# PinHeck.net
KiCad netlist of a schematic drawn in EAGLE
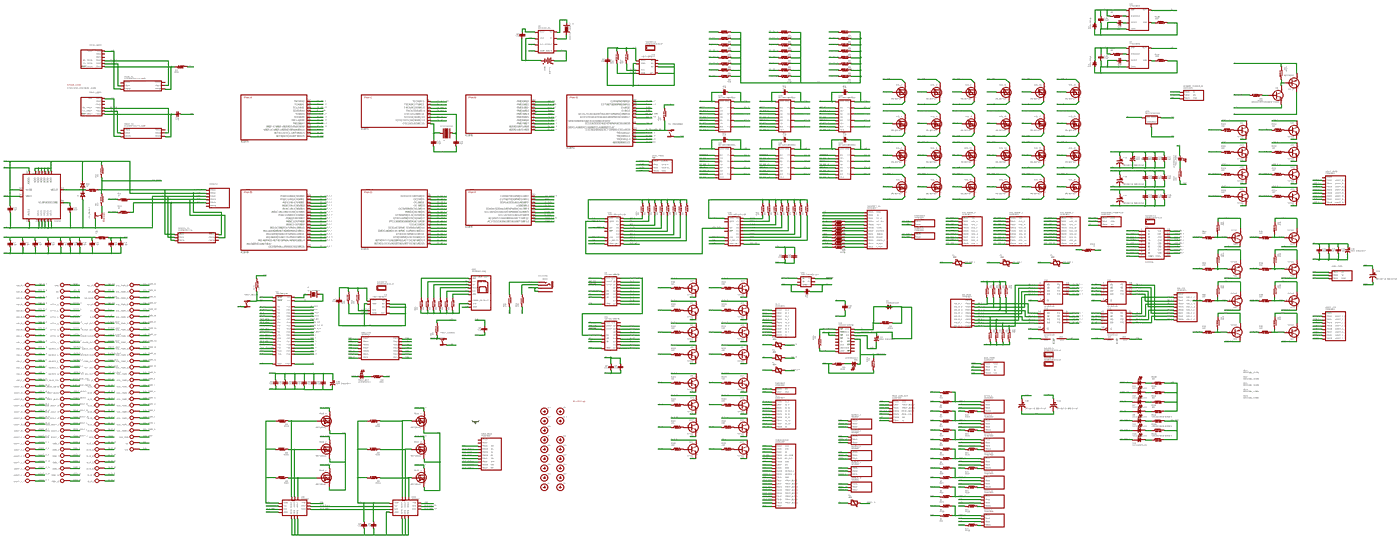
[diagram p0: schematic, sheet 1, overview]
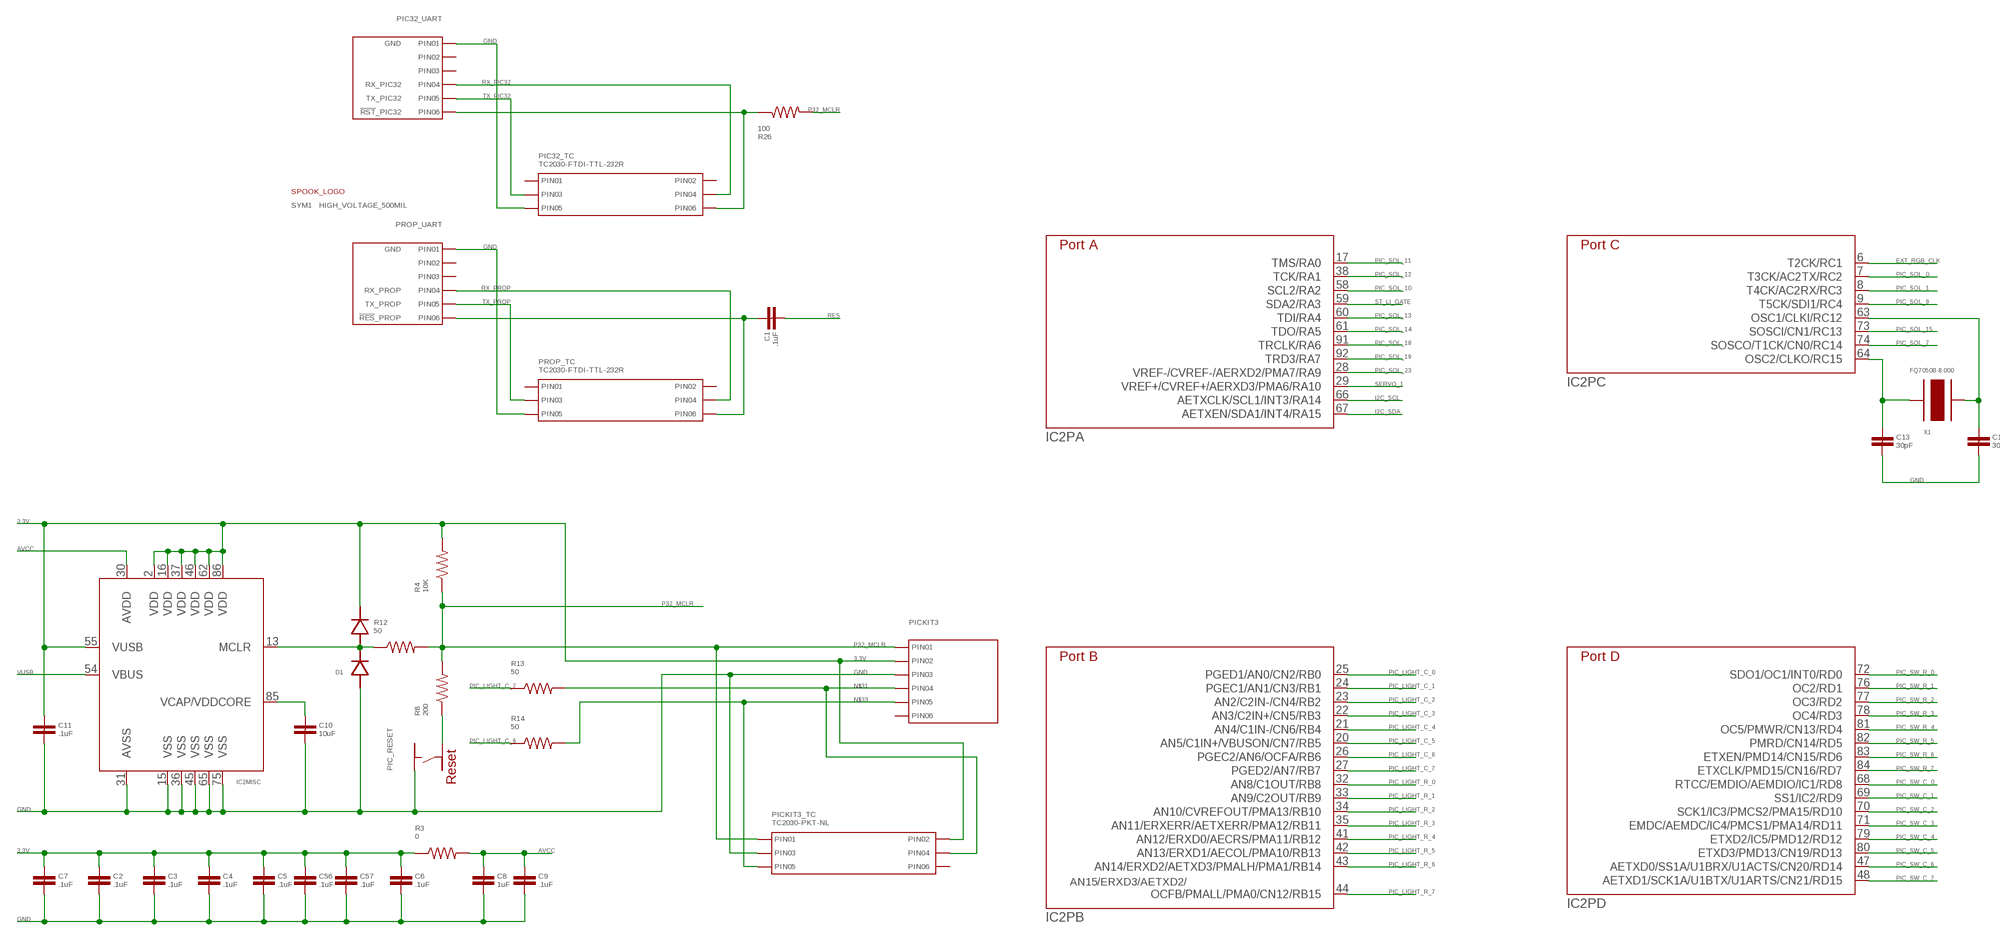
[diagram p1: schematic, sheet 1, part 1 of 7]
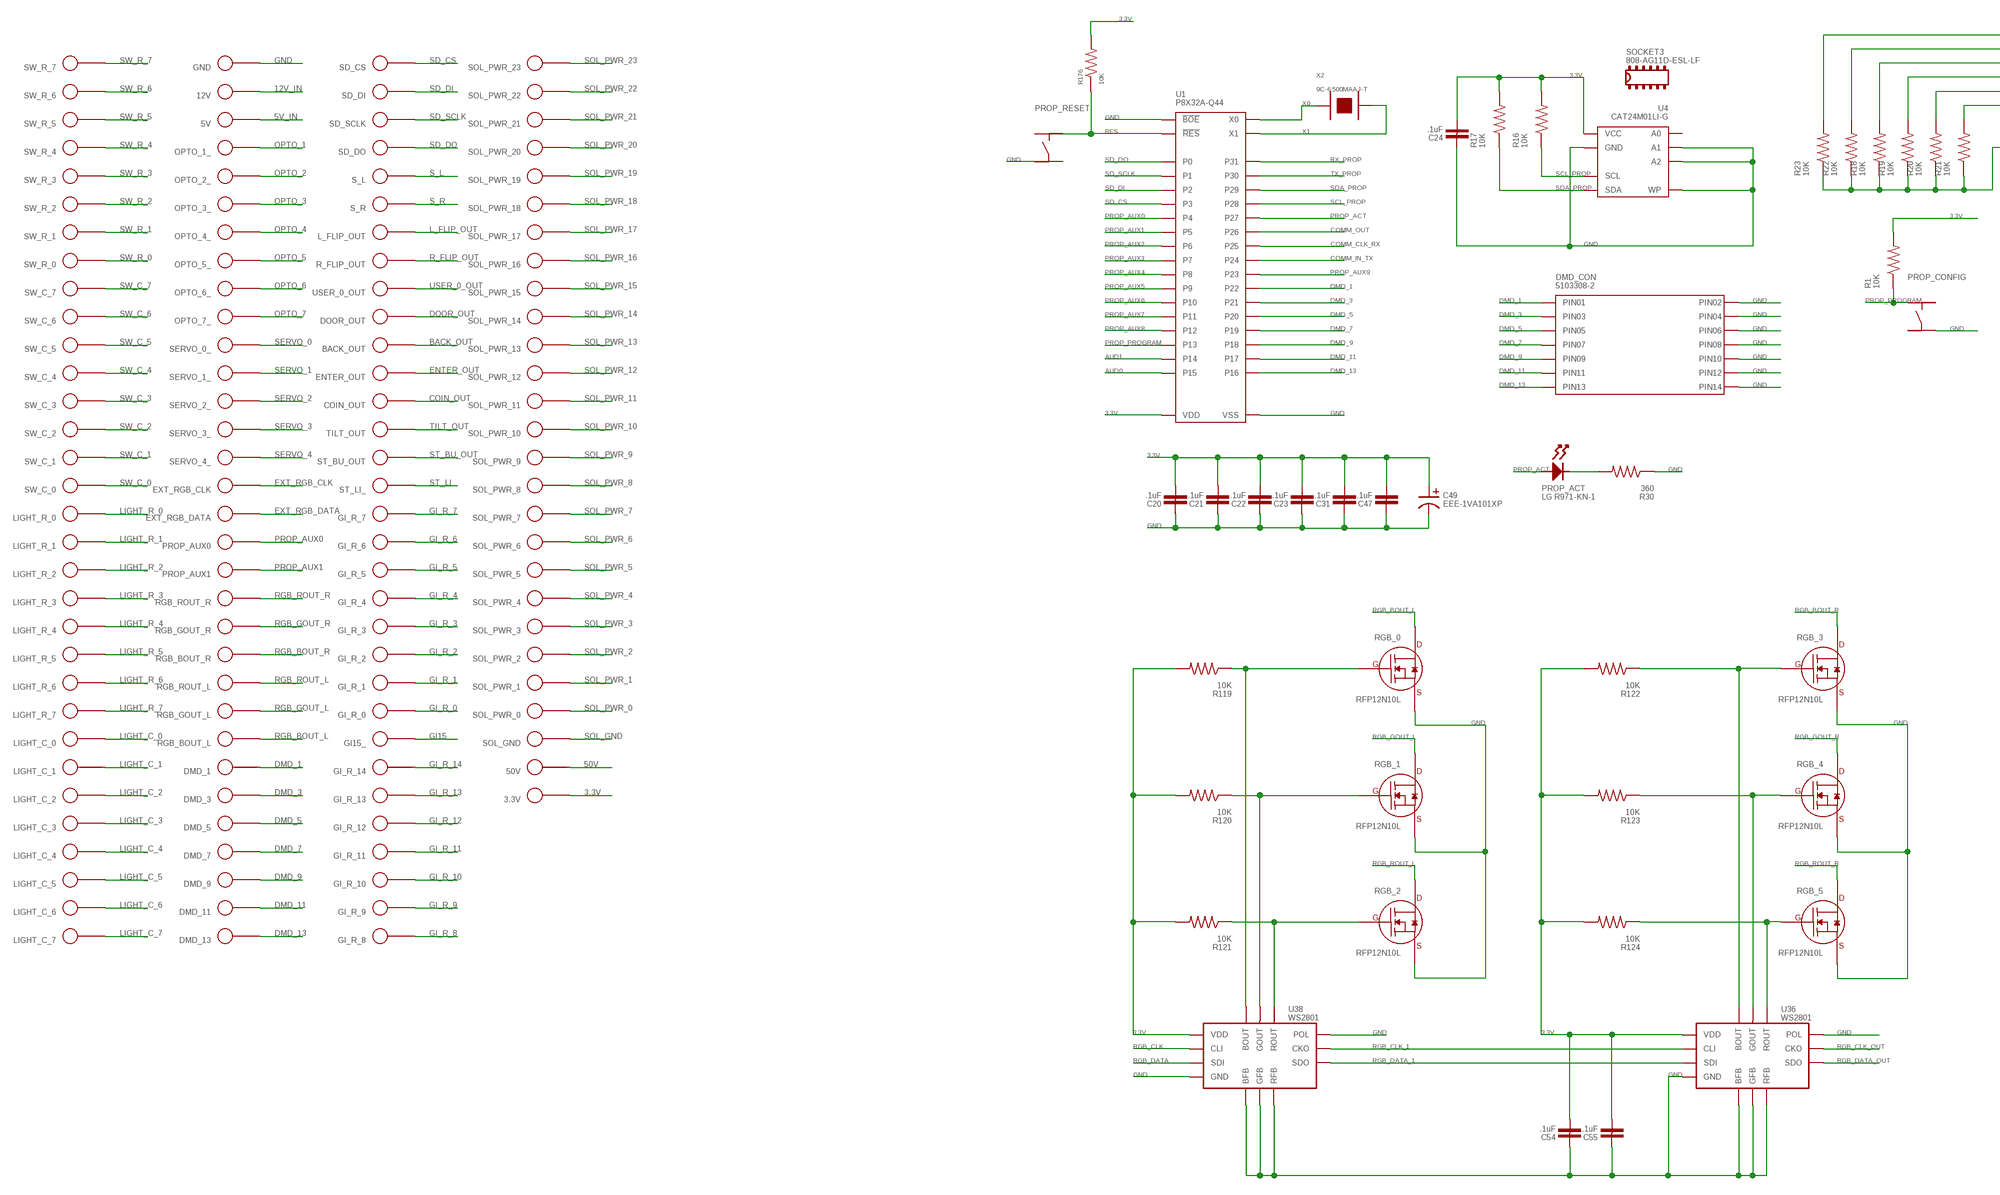
[diagram p2: schematic, sheet 1, part 2 of 7]
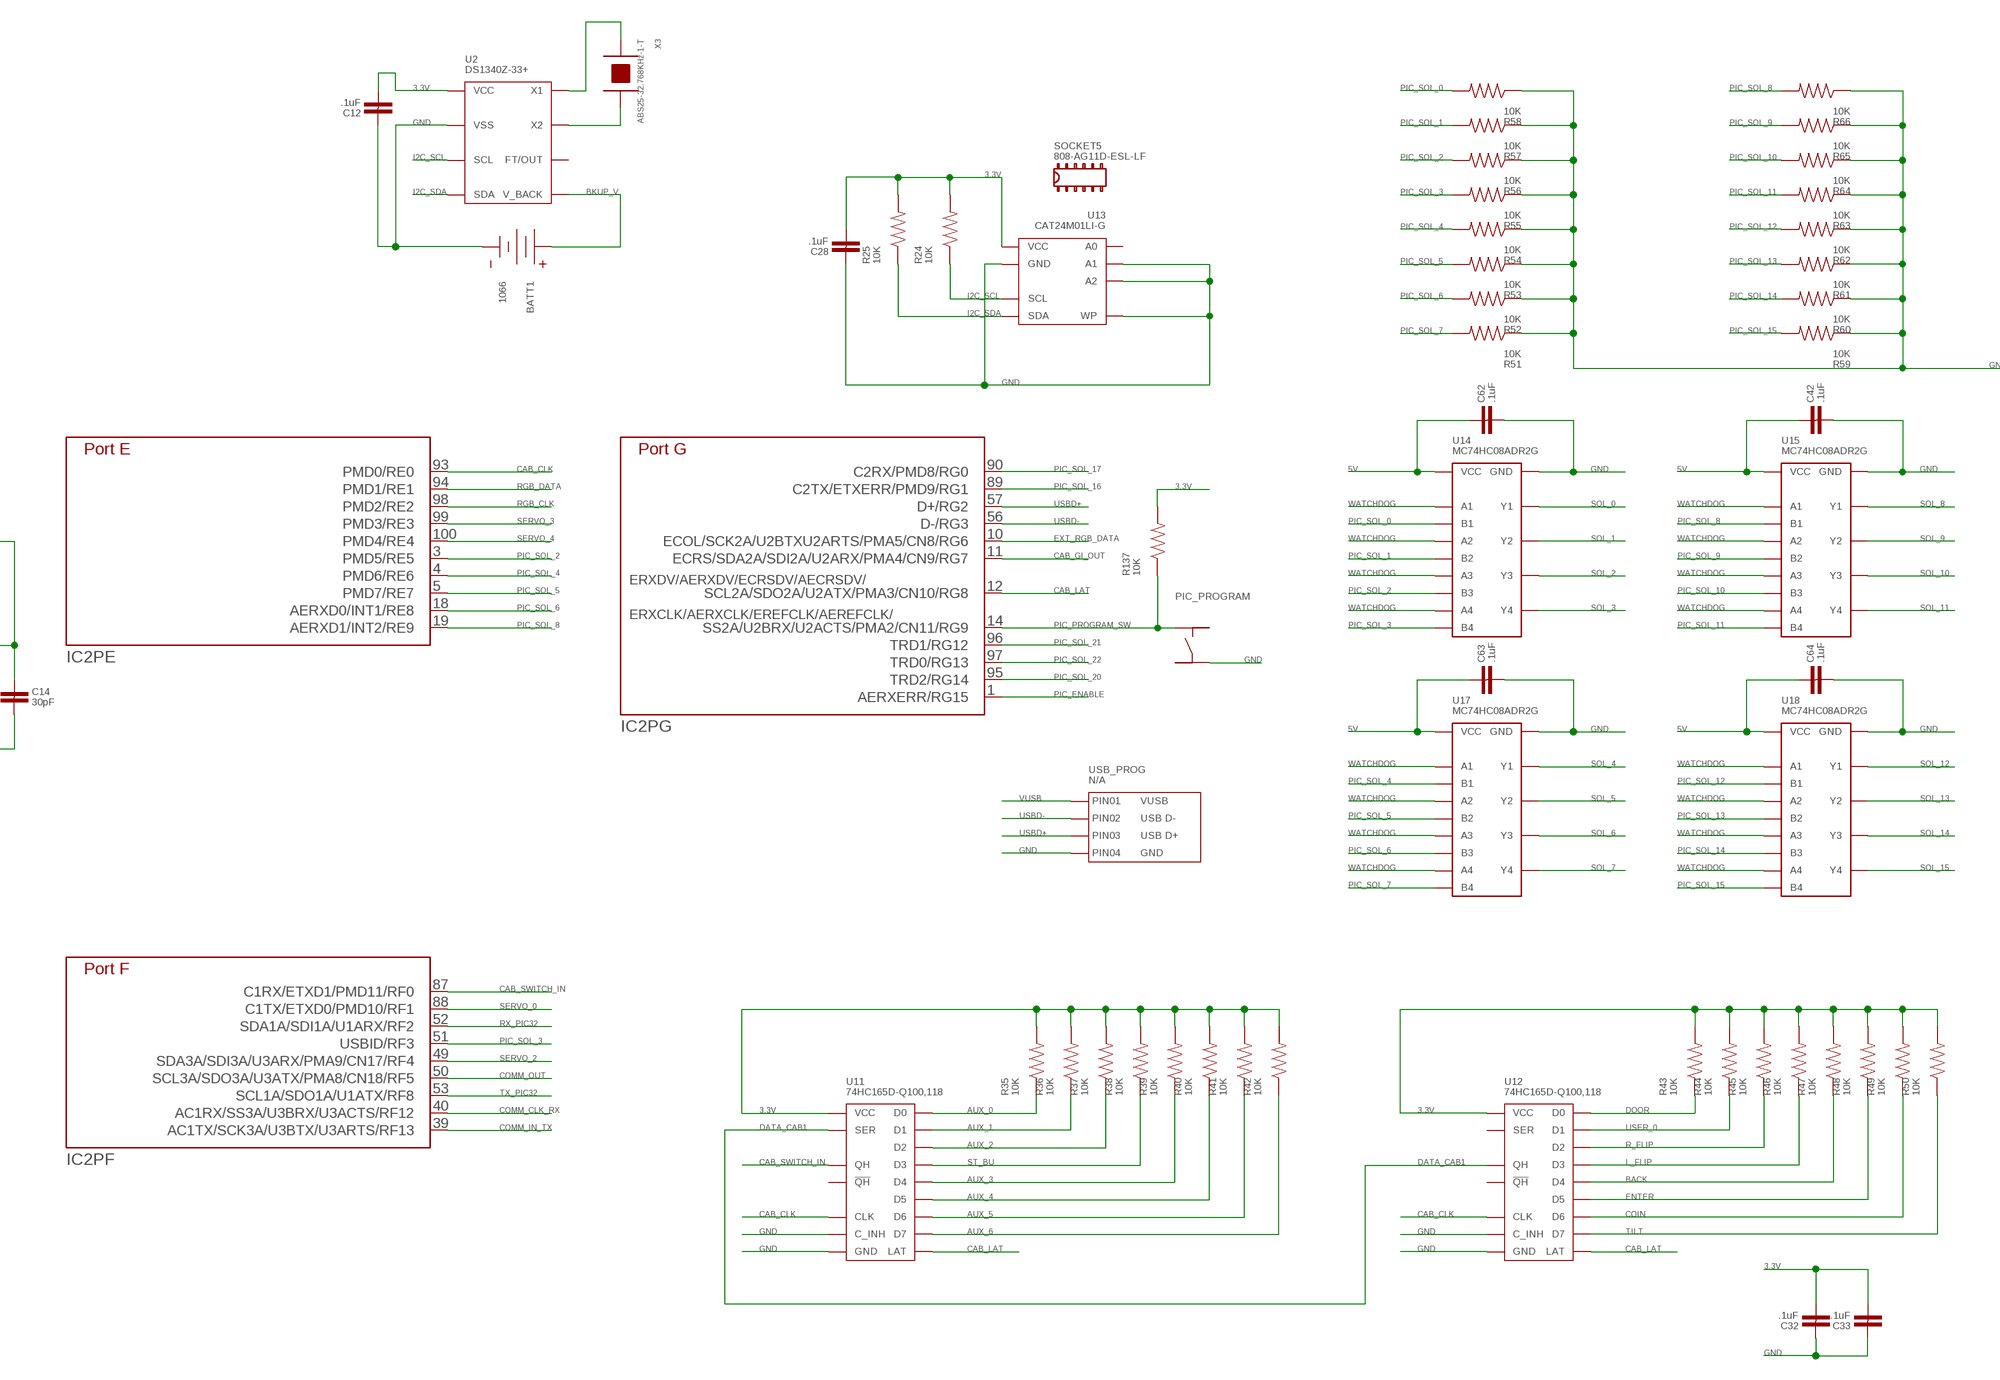
[diagram p3: schematic, sheet 1, part 3 of 7]
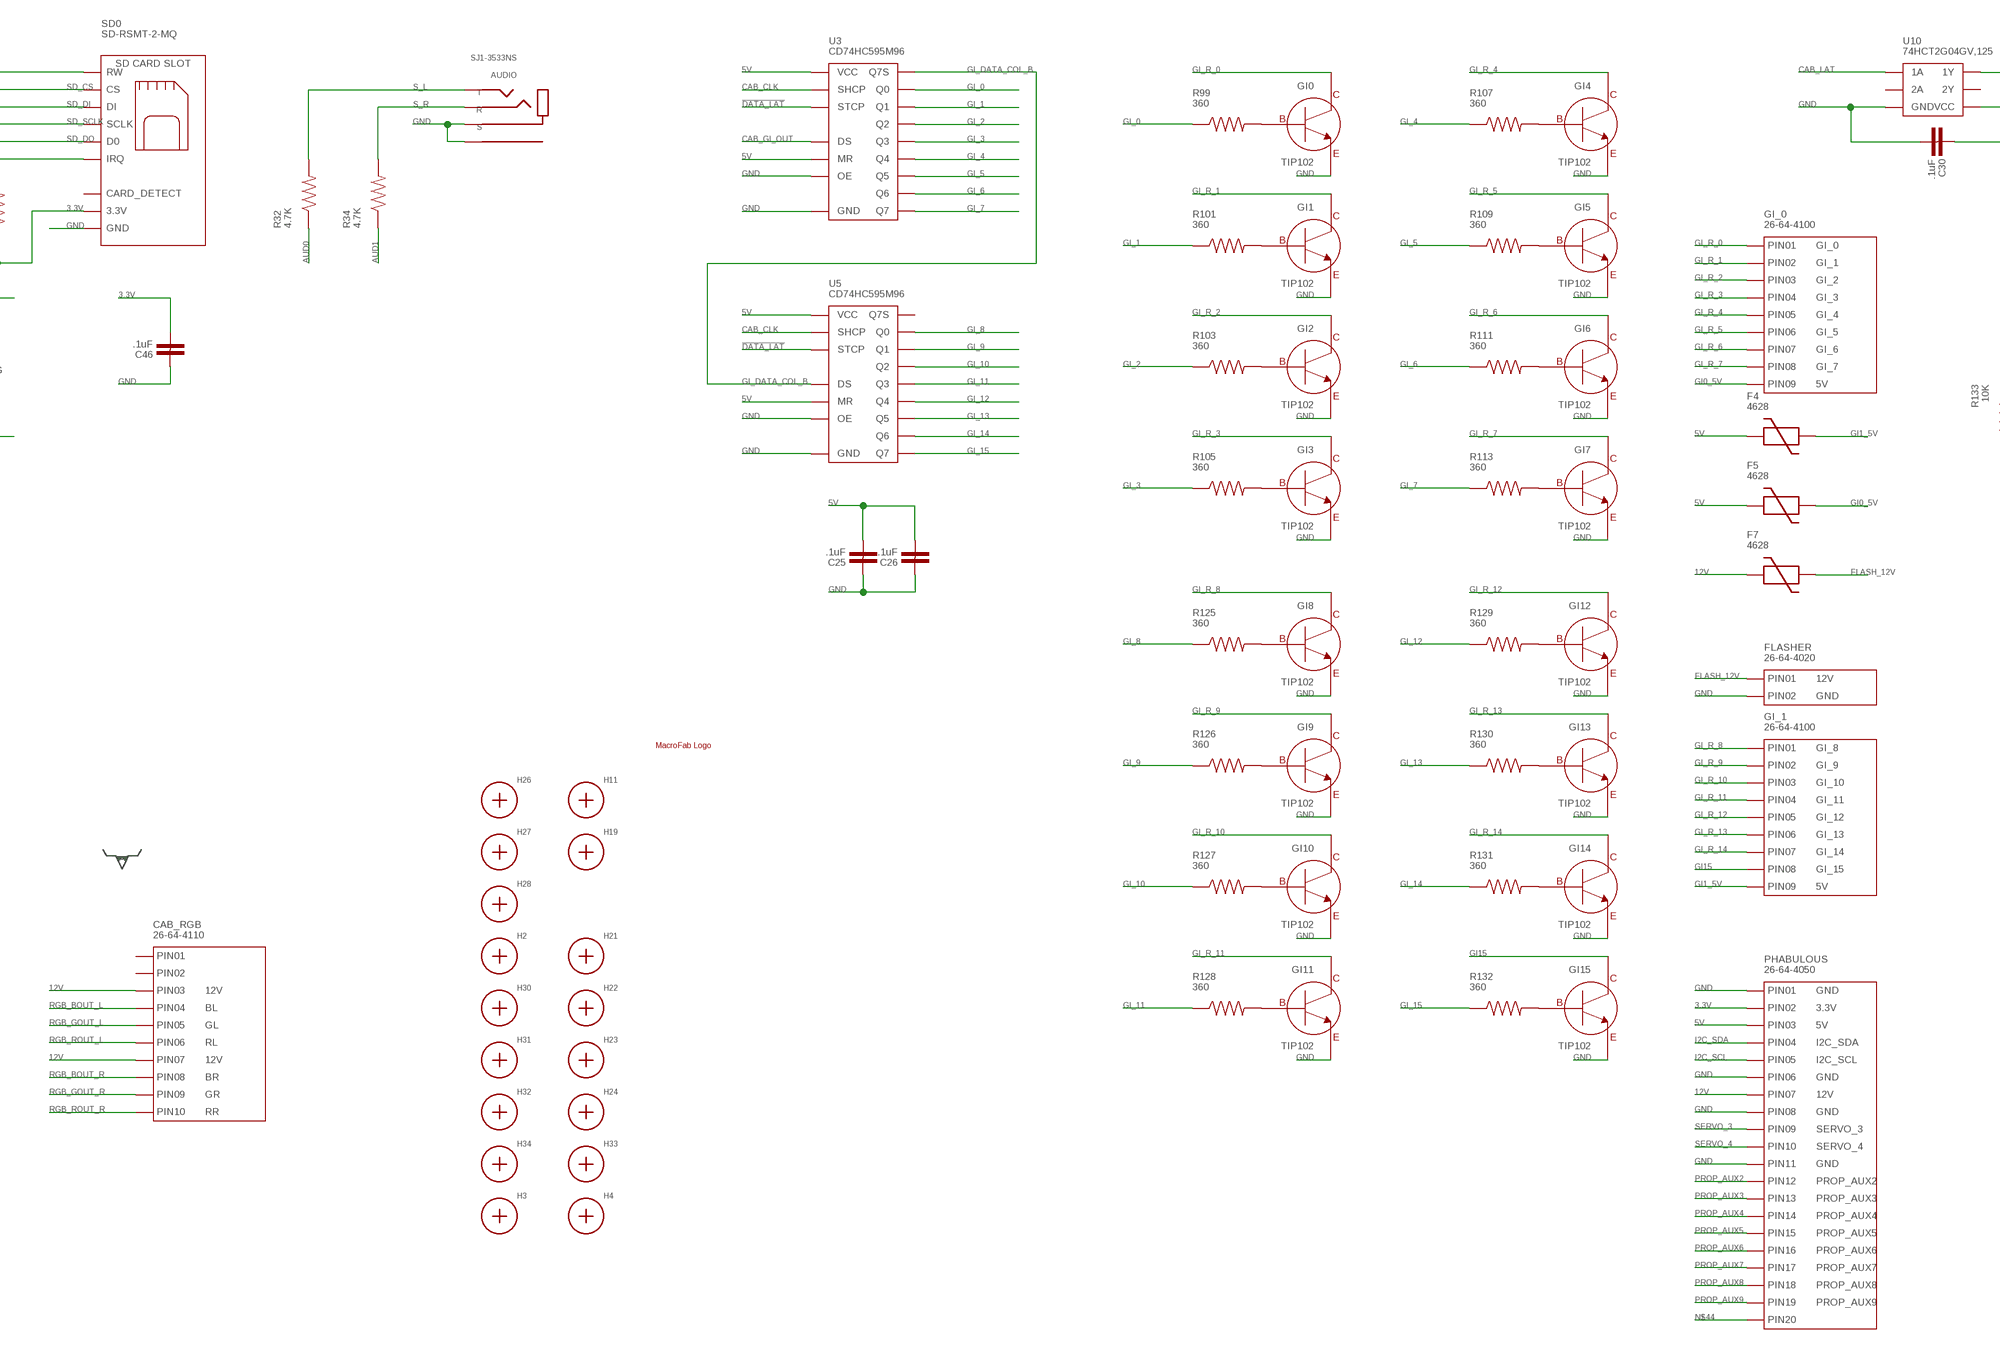
[diagram p4: schematic, sheet 1, part 4 of 7]
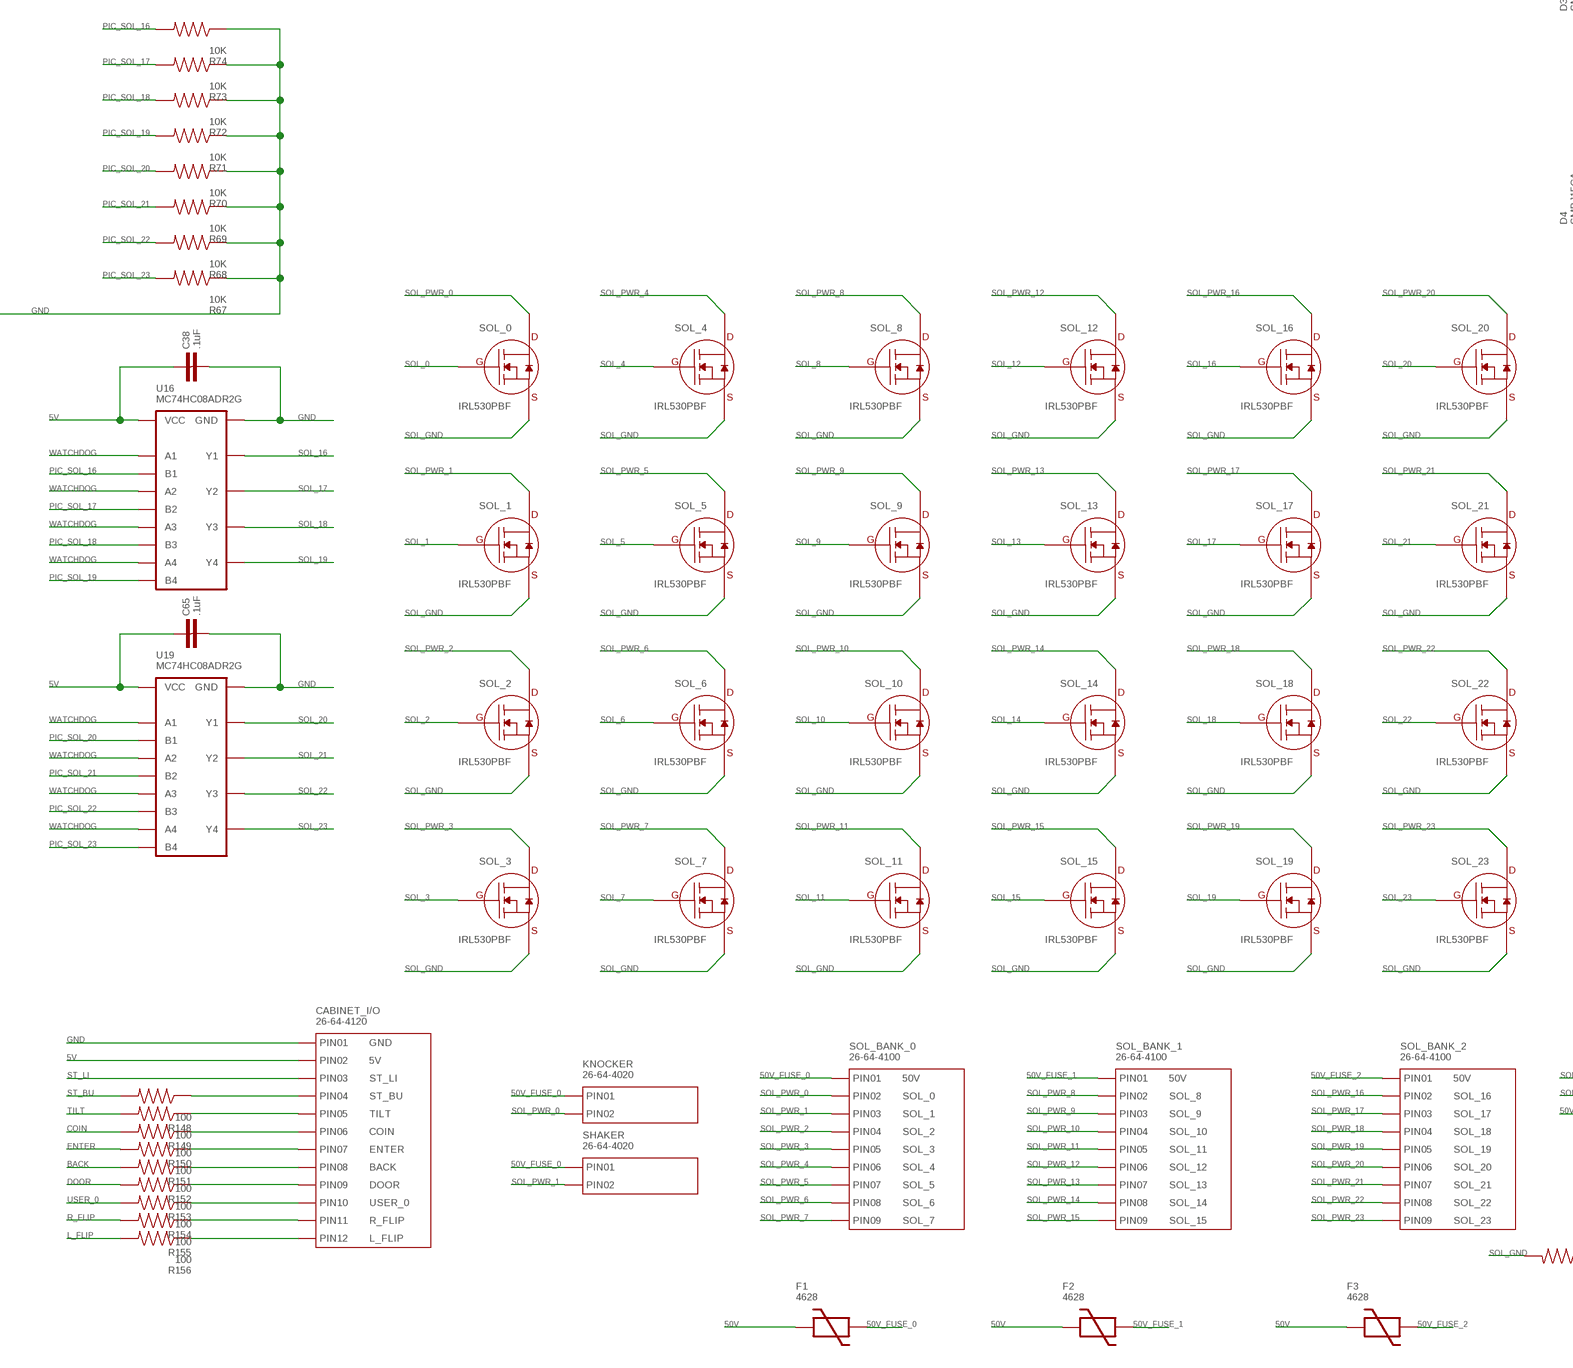
[diagram p5: schematic, sheet 1, part 5 of 7]
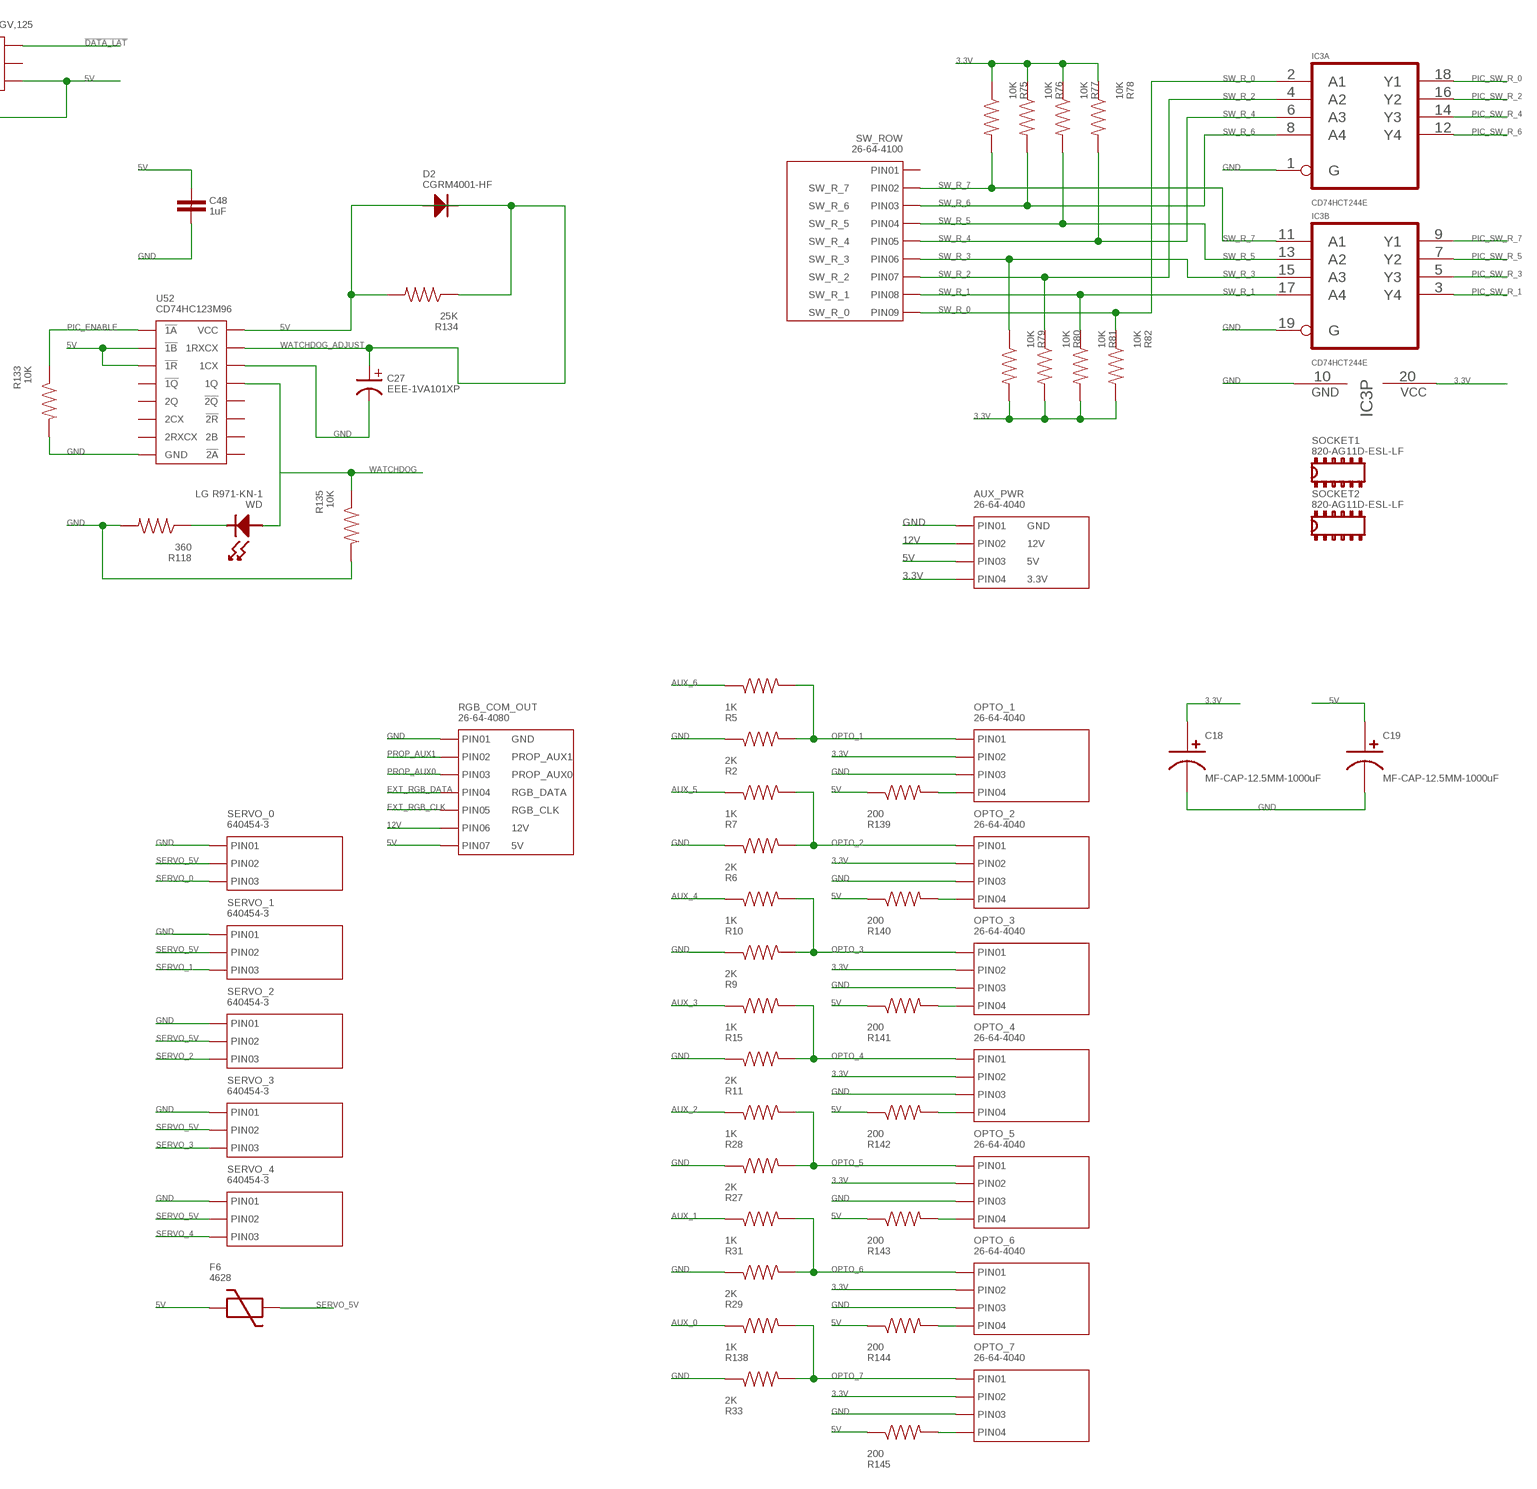
[diagram p6: schematic, sheet 1, part 6 of 7]
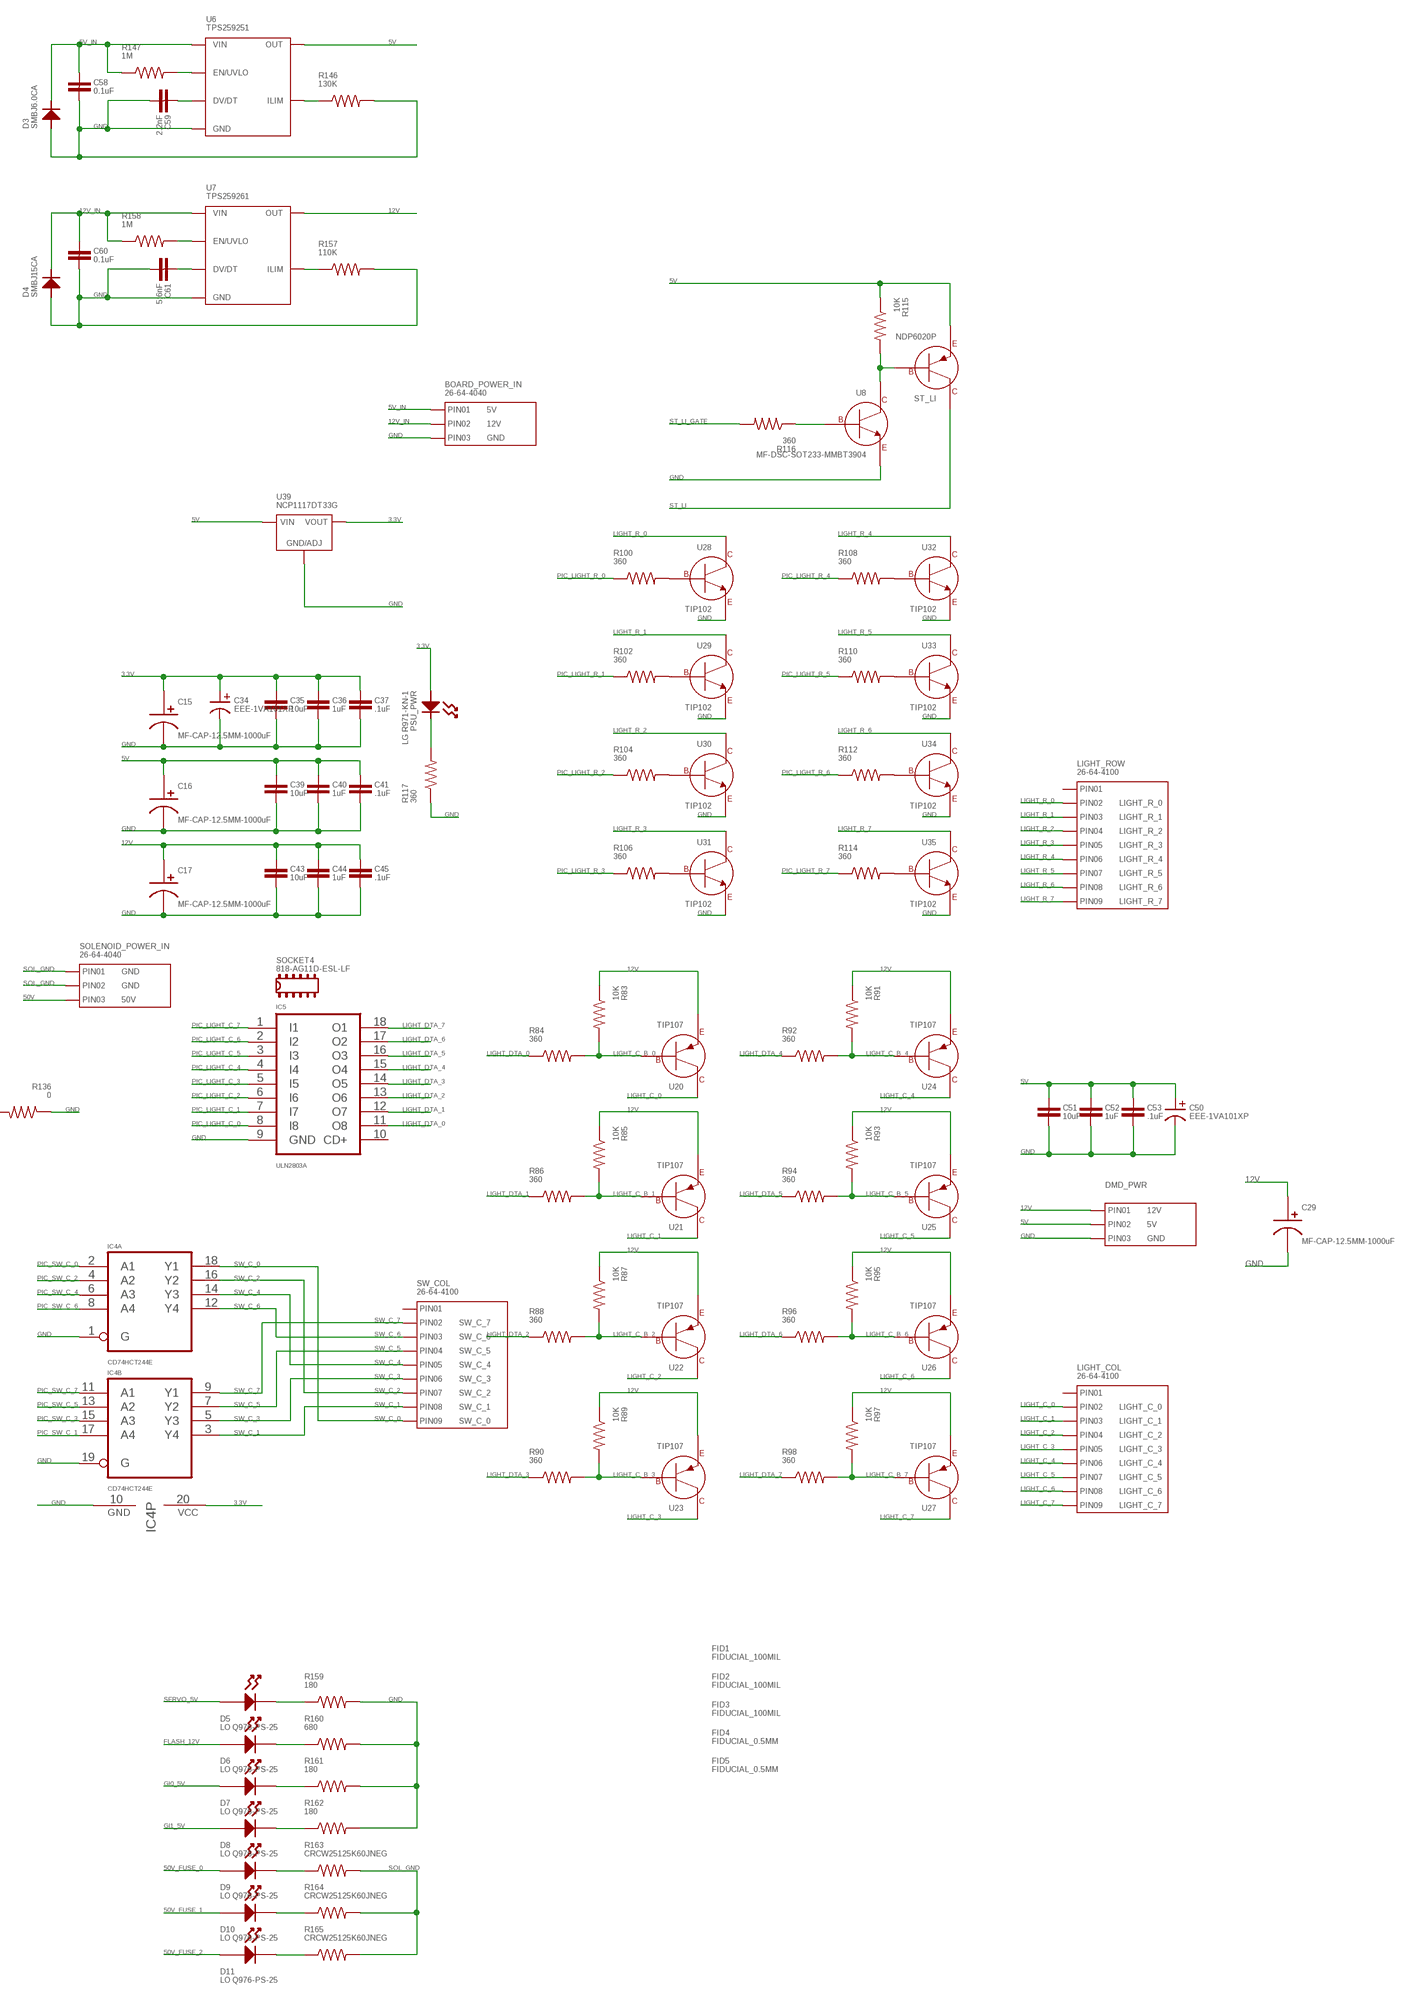
[diagram p7: schematic, sheet 1, part 7 of 7]

(export (version "E")
  (design (tool "Eeschema 10.0.6"))
  (components
    (comp (ref "3.3V")
      (value "TEST_POINT_SINGLE_ROUND_100MIL")
      (footprint "eagle-import:100MIL_TP")
      (libsource (lib "eagle-import") (part "TEST_POINT_SINGLE_ROUND_100MIL"))
    )
    (comp (ref "5V")
      (value "TEST_POINT_SINGLE_ROUND_100MIL")
      (footprint "eagle-import:100MIL_TP")
      (libsource (lib "eagle-import") (part "TEST_POINT_SINGLE_ROUND_100MIL"))
    )
    (comp (ref "12V")
      (value "TEST_POINT_SINGLE_ROUND_100MIL")
      (footprint "eagle-import:100MIL_TP")
      (libsource (lib "eagle-import") (part "TEST_POINT_SINGLE_ROUND_100MIL"))
    )
    (comp (ref "50V")
      (value "TEST_POINT_SINGLE_ROUND_100MIL")
      (footprint "eagle-import:100MIL_TP")
      (libsource (lib "eagle-import") (part "TEST_POINT_SINGLE_ROUND_100MIL"))
    )
    (comp (ref "AUDIO")
      (value "SJ1-3533NS")
      (footprint "eagle-import:SJ1-3533NS")
      (libsource (lib "eagle-import") (part "TRS_SHIELD_JACK_SJ1-3533NS"))
    )
    (comp (ref "AUX_PWR")
      (value "26-64-4040")
      (footprint "eagle-import:26-64-4040")
      (fields
        (field (name "LABEL01") "GND")
        (field (name "LABEL02") "12V")
        (field (name "LABEL03") "5V")
        (field (name "LABEL04") "3.3V")
      )
      (libsource (lib "eagle-import") (part "CON_01X04_26-64-4040"))
    )
    (comp (ref "BACK_OUT")
      (value "TEST_POINT_SINGLE_ROUND_100MIL")
      (footprint "eagle-import:100MIL_TP")
      (libsource (lib "eagle-import") (part "TEST_POINT_SINGLE_ROUND_100MIL"))
    )
    (comp (ref "BATT1")
      (value "1066")
      (footprint "eagle-import:1066")
      (libsource (lib "eagle-import") (part "BATTERY_1066"))
    )
    (comp (ref "BOARD_POWER_IN")
      (value "26-64-4040")
      (footprint "eagle-import:26-64-4040(KEYPIN2)")
      (fields (field (name "LABEL01") "5V") (field (name "LABEL02") "12V") (field (name "LABEL03") "GND"))
      (libsource (lib "eagle-import") (part "CON_01X03_26-64-4040_(KEYPIN2)"))
    )
    (comp (ref "C1")
      (value ".1uF")
      (footprint "eagle-import:0805")
      (libsource (lib "eagle-import") (part "CAPACITOR_NON_POLAR_0805"))
    )
    (comp (ref "C2")
      (value ".1uF")
      (footprint "eagle-import:0805")
      (libsource (lib "eagle-import") (part "CAPACITOR_NON_POLAR_0805"))
    )
    (comp (ref "C3")
      (value ".1uF")
      (footprint "eagle-import:0805")
      (libsource (lib "eagle-import") (part "CAPACITOR_NON_POLAR_0805"))
    )
    (comp (ref "C4")
      (value ".1uF")
      (footprint "eagle-import:0805")
      (libsource (lib "eagle-import") (part "CAPACITOR_NON_POLAR_0805"))
    )
    (comp (ref "C5")
      (value ".1uF")
      (footprint "eagle-import:0805")
      (libsource (lib "eagle-import") (part "CAPACITOR_NON_POLAR_0805"))
    )
    (comp (ref "C6")
      (value ".1uF")
      (footprint "eagle-import:0805")
      (libsource (lib "eagle-import") (part "CAPACITOR_NON_POLAR_0805"))
    )
    (comp (ref "C7")
      (value ".1uF")
      (footprint "eagle-import:0805")
      (libsource (lib "eagle-import") (part "CAPACITOR_NON_POLAR_0805"))
    )
    (comp (ref "C8")
      (value "1uF")
      (footprint "eagle-import:0805")
      (libsource (lib "eagle-import") (part "CAPACITOR_NON_POLAR_0805"))
    )
    (comp (ref "C9")
      (value ".1uF")
      (footprint "eagle-import:0805")
      (libsource (lib "eagle-import") (part "CAPACITOR_NON_POLAR_0805"))
    )
    (comp (ref "C10")
      (value "10uF")
      (footprint "eagle-import:1206")
      (libsource (lib "eagle-import") (part "CAPACITOR_NON_POLAR_1206"))
    )
    (comp (ref "C11")
      (value ".1uF")
      (footprint "eagle-import:0805")
      (libsource (lib "eagle-import") (part "CAPACITOR_NON_POLAR_0805"))
    )
    (comp (ref "C12")
      (value ".1uF")
      (footprint "eagle-import:0805")
      (libsource (lib "eagle-import") (part "CAPACITOR_NON_POLAR_0805"))
    )
    (comp (ref "C13")
      (value "30pF")
      (footprint "eagle-import:0805")
      (libsource (lib "eagle-import") (part "CAPACITOR_NON_POLAR_0805"))
    )
    (comp (ref "C14")
      (value "30pF")
      (footprint "eagle-import:0805")
      (libsource (lib "eagle-import") (part "CAPACITOR_NON_POLAR_0805"))
    )
    (comp (ref "C15")
      (value "MF-CAP-12.5MM-1000uF")
      (footprint "eagle-import:CP12.5MM")
      (libsource (lib "eagle-import") (part "CAPACITOR_P_12.5MM"))
    )
    (comp (ref "C16")
      (value "MF-CAP-12.5MM-1000uF")
      (footprint "eagle-import:CP12.5MM")
      (libsource (lib "eagle-import") (part "CAPACITOR_P_12.5MM"))
    )
    (comp (ref "C17")
      (value "MF-CAP-12.5MM-1000uF")
      (footprint "eagle-import:CP12.5MM")
      (libsource (lib "eagle-import") (part "CAPACITOR_P_12.5MM"))
    )
    (comp (ref "C18")
      (value "MF-CAP-12.5MM-1000uF")
      (footprint "eagle-import:CP12.5MM")
      (libsource (lib "eagle-import") (part "CAPACITOR_P_12.5MM"))
    )
    (comp (ref "C19")
      (value "MF-CAP-12.5MM-1000uF")
      (footprint "eagle-import:CP12.5MM")
      (libsource (lib "eagle-import") (part "CAPACITOR_P_12.5MM"))
    )
    (comp (ref "C20")
      (value ".1uF")
      (footprint "eagle-import:0805")
      (libsource (lib "eagle-import") (part "CAPACITOR_NON_POLAR_0805"))
    )
    (comp (ref "C21")
      (value ".1uF")
      (footprint "eagle-import:0805")
      (libsource (lib "eagle-import") (part "CAPACITOR_NON_POLAR_0805"))
    )
    (comp (ref "C22")
      (value ".1uF")
      (footprint "eagle-import:0805")
      (libsource (lib "eagle-import") (part "CAPACITOR_NON_POLAR_0805"))
    )
    (comp (ref "C23")
      (value ".1uF")
      (footprint "eagle-import:0805")
      (libsource (lib "eagle-import") (part "CAPACITOR_NON_POLAR_0805"))
    )
    (comp (ref "C24")
      (value ".1uF")
      (footprint "eagle-import:0805")
      (libsource (lib "eagle-import") (part "CAPACITOR_NON_POLAR_0805"))
    )
    (comp (ref "C25")
      (value ".1uF")
      (footprint "eagle-import:0805")
      (libsource (lib "eagle-import") (part "CAPACITOR_NON_POLAR_0805"))
    )
    (comp (ref "C26")
      (value ".1uF")
      (footprint "eagle-import:0805")
      (libsource (lib "eagle-import") (part "CAPACITOR_NON_POLAR_0805"))
    )
    (comp (ref "C27")
      (value "EEE-1VA101XP")
      (footprint "eagle-import:6.3MM_CAP_SMD")
      (libsource (lib "eagle-import") (part "CAPACITOR_POLARIZED_6.3MM_SMD"))
    )
    (comp (ref "C28")
      (value ".1uF")
      (footprint "eagle-import:0805")
      (libsource (lib "eagle-import") (part "CAPACITOR_NON_POLAR_0805"))
    )
    (comp (ref "C29")
      (value "MF-CAP-12.5MM-1000uF")
      (footprint "eagle-import:CP6.3MM")
      (libsource (lib "eagle-import") (part "CAPACITOR_P_6.3MM"))
    )
    (comp (ref "C30")
      (value ".1uF")
      (footprint "eagle-import:0805")
      (libsource (lib "eagle-import") (part "CAPACITOR_NON_POLAR_0805"))
    )
    (comp (ref "C31")
      (value ".1uF")
      (footprint "eagle-import:0805")
      (libsource (lib "eagle-import") (part "CAPACITOR_NON_POLAR_0805"))
    )
    (comp (ref "C32")
      (value ".1uF")
      (footprint "eagle-import:0805")
      (libsource (lib "eagle-import") (part "CAPACITOR_NON_POLAR_0805"))
    )
    (comp (ref "C33")
      (value ".1uF")
      (footprint "eagle-import:0805")
      (libsource (lib "eagle-import") (part "CAPACITOR_NON_POLAR_0805"))
    )
    (comp (ref "C34")
      (value "EEE-1VA101XP")
      (footprint "eagle-import:6.3MM_CAP_SMD")
      (libsource (lib "eagle-import") (part "CAPACITOR_POLARIZED_6.3MM_SMD"))
    )
    (comp (ref "C35")
      (value "10uF")
      (footprint "eagle-import:1206")
      (libsource (lib "eagle-import") (part "CAPACITOR_NON_POLAR_1206"))
    )
    (comp (ref "C36")
      (value "1uF")
      (footprint "eagle-import:0805")
      (libsource (lib "eagle-import") (part "CAPACITOR_NON_POLAR_0805"))
    )
    (comp (ref "C37")
      (value ".1uF")
      (footprint "eagle-import:0805")
      (libsource (lib "eagle-import") (part "CAPACITOR_NON_POLAR_0805"))
    )
    (comp (ref "C38")
      (value ".1uF")
      (footprint "eagle-import:0805")
      (libsource (lib "eagle-import") (part "CAPACITOR_NON_POLAR_0805"))
    )
    (comp (ref "C39")
      (value "10uF")
      (footprint "eagle-import:1206")
      (libsource (lib "eagle-import") (part "CAPACITOR_NON_POLAR_1206"))
    )
    (comp (ref "C40")
      (value "1uF")
      (footprint "eagle-import:0805")
      (libsource (lib "eagle-import") (part "CAPACITOR_NON_POLAR_0805"))
    )
    (comp (ref "C41")
      (value ".1uF")
      (footprint "eagle-import:0805")
      (libsource (lib "eagle-import") (part "CAPACITOR_NON_POLAR_0805"))
    )
    (comp (ref "C42")
      (value ".1uF")
      (footprint "eagle-import:0805")
      (libsource (lib "eagle-import") (part "CAPACITOR_NON_POLAR_0805"))
    )
    (comp (ref "C43")
      (value "10uF")
      (footprint "eagle-import:1206")
      (libsource (lib "eagle-import") (part "CAPACITOR_NON_POLAR_1206"))
    )
    (comp (ref "C44")
      (value "1uF")
      (footprint "eagle-import:0805")
      (libsource (lib "eagle-import") (part "CAPACITOR_NON_POLAR_0805"))
    )
    (comp (ref "C45")
      (value ".1uF")
      (footprint "eagle-import:0805")
      (libsource (lib "eagle-import") (part "CAPACITOR_NON_POLAR_0805"))
    )
    (comp (ref "C46")
      (value ".1uF")
      (footprint "eagle-import:0805")
      (libsource (lib "eagle-import") (part "CAPACITOR_NON_POLAR_0805"))
    )
    (comp (ref "C47")
      (value ".1uF")
      (footprint "eagle-import:0805")
      (libsource (lib "eagle-import") (part "CAPACITOR_NON_POLAR_0805"))
    )
    (comp (ref "C48")
      (value "1uF")
      (footprint "eagle-import:0805")
      (libsource (lib "eagle-import") (part "CAPACITOR_NON_POLAR_0805"))
    )
    (comp (ref "C49")
      (value "EEE-1VA101XP")
      (footprint "eagle-import:6.3MM_CAP_SMD")
      (libsource (lib "eagle-import") (part "CAPACITOR_POLARIZED_6.3MM_SMD"))
    )
    (comp (ref "C50")
      (value "EEE-1VA101XP")
      (footprint "eagle-import:6.3MM_CAP_SMD")
      (libsource (lib "eagle-import") (part "CAPACITOR_POLARIZED_6.3MM_SMD"))
    )
    (comp (ref "C51")
      (value "10uF")
      (footprint "eagle-import:1206")
      (libsource (lib "eagle-import") (part "CAPACITOR_NON_POLAR_1206"))
    )
    (comp (ref "C52")
      (value "1uF")
      (footprint "eagle-import:0805")
      (libsource (lib "eagle-import") (part "CAPACITOR_NON_POLAR_0805"))
    )
    (comp (ref "C53")
      (value ".1uF")
      (footprint "eagle-import:0805")
      (libsource (lib "eagle-import") (part "CAPACITOR_NON_POLAR_0805"))
    )
    (comp (ref "C54")
      (value ".1uF")
      (footprint "eagle-import:0805")
      (libsource (lib "eagle-import") (part "CAPACITOR_NON_POLAR_0805"))
    )
    (comp (ref "C55")
      (value ".1uF")
      (footprint "eagle-import:0805")
      (libsource (lib "eagle-import") (part "CAPACITOR_NON_POLAR_0805"))
    )
    (comp (ref "C56")
      (value ".1uF")
      (footprint "eagle-import:0805")
      (libsource (lib "eagle-import") (part "CAPACITOR_NON_POLAR_0805"))
    )
    (comp (ref "C57")
      (value ".1uF")
      (footprint "eagle-import:0805")
      (libsource (lib "eagle-import") (part "CAPACITOR_NON_POLAR_0805"))
    )
    (comp (ref "C58")
      (value "0.1uF")
      (footprint "eagle-import:0805")
      (libsource (lib "eagle-import") (part "CAPACITOR_NON_POLAR_0805"))
    )
    (comp (ref "C59")
      (value "2.2nF")
      (footprint "eagle-import:0805")
      (libsource (lib "eagle-import") (part "CAPACITOR_NON_POLAR_0805"))
    )
    (comp (ref "C60")
      (value "0.1uF")
      (footprint "eagle-import:0805")
      (libsource (lib "eagle-import") (part "CAPACITOR_NON_POLAR_0805"))
    )
    (comp (ref "C61")
      (value "5.6nF")
      (footprint "eagle-import:0805")
      (libsource (lib "eagle-import") (part "CAPACITOR_NON_POLAR_0805"))
    )
    (comp (ref "C62")
      (value ".1uF")
      (footprint "eagle-import:0805")
      (libsource (lib "eagle-import") (part "CAPACITOR_NON_POLAR_0805"))
    )
    (comp (ref "C63")
      (value ".1uF")
      (footprint "eagle-import:0805")
      (libsource (lib "eagle-import") (part "CAPACITOR_NON_POLAR_0805"))
    )
    (comp (ref "C64")
      (value ".1uF")
      (footprint "eagle-import:0805")
      (libsource (lib "eagle-import") (part "CAPACITOR_NON_POLAR_0805"))
    )
    (comp (ref "C65")
      (value ".1uF")
      (footprint "eagle-import:0805")
      (libsource (lib "eagle-import") (part "CAPACITOR_NON_POLAR_0805"))
    )
    (comp (ref "CABINET_I/O")
      (value "26-64-4120")
      (footprint "eagle-import:26-64-4120")
      (fields
        (field (name "LABEL01") "GND")
        (field (name "LABEL02") "5V")
        (field (name "LABEL03") "ST_LI")
        (field (name "LABEL04") "ST_BU")
        (field (name "LABEL05") "TILT")
        (field (name "LABEL06") "COIN")
        (field (name "LABEL07") "ENTER")
        (field (name "LABEL08") "BACK")
        (field (name "LABEL09") "DOOR")
        (field (name "LABEL10") "USER_0")
        (field (name "LABEL11") "R_FLIP")
        (field (name "LABEL12") "L_FLIP")
      )
      (libsource (lib "eagle-import") (part "CON_01X12_26-64-4120"))
    )
    (comp (ref "CAB_RGB")
      (value "26-64-4110")
      (footprint "eagle-import:26-64-4110(KEYPIN3)")
      (fields
        (field (name "LABEL03") "12V")
        (field (name "LABEL04") "BL")
        (field (name "LABEL05") "GL")
        (field (name "LABEL06") "RL")
        (field (name "LABEL07") "12V")
        (field (name "LABEL08") "BR")
        (field (name "LABEL09") "GR")
        (field (name "LABEL10") "RR")
      )
      (libsource (lib "eagle-import") (part "CON_01X10_26-64-4110(KEYPIN3)"))
    )
    (comp (ref "COIN_OUT")
      (value "TEST_POINT_SINGLE_ROUND_100MIL")
      (footprint "eagle-import:100MIL_TP")
      (libsource (lib "eagle-import") (part "TEST_POINT_SINGLE_ROUND_100MIL"))
    )
    (comp (ref "D1")
      (value "BAV99W,115")
      (footprint "eagle-import:SOT-323")
      (libsource (lib "eagle-import") (part "BAV99W"))
    )
    (comp (ref "D2")
      (value "CGRM4001-HF")
      (footprint "eagle-import:SOD-123")
      (libsource (lib "eagle-import") (part "DIODE_SOD-123"))
    )
    (comp (ref "D3")
      (value "SMBJ6.0CA")
      (footprint "eagle-import:SMBJ")
      (libsource (lib "eagle-import") (part "DIODE_SMBJ"))
    )
    (comp (ref "D4")
      (value "SMBJ15CA")
      (footprint "eagle-import:SMBJ")
      (libsource (lib "eagle-import") (part "DIODE_SMBJ"))
    )
    (comp (ref "D5")
      (value "LO Q976-PS-25")
      (footprint "eagle-import:LED0603")
      (libsource (lib "eagle-import") (part "LED_SINGLE_0603"))
    )
    (comp (ref "D6")
      (value "LO Q976-PS-25")
      (footprint "eagle-import:LED0603")
      (libsource (lib "eagle-import") (part "LED_SINGLE_0603"))
    )
    (comp (ref "D7")
      (value "LO Q976-PS-25")
      (footprint "eagle-import:LED0603")
      (libsource (lib "eagle-import") (part "LED_SINGLE_0603"))
    )
    (comp (ref "D8")
      (value "LO Q976-PS-25")
      (footprint "eagle-import:LED0603")
      (libsource (lib "eagle-import") (part "LED_SINGLE_0603"))
    )
    (comp (ref "D9")
      (value "LO Q976-PS-25")
      (footprint "eagle-import:LED0603")
      (libsource (lib "eagle-import") (part "LED_SINGLE_0603"))
    )
    (comp (ref "D10")
      (value "LO Q976-PS-25")
      (footprint "eagle-import:LED0603")
      (libsource (lib "eagle-import") (part "LED_SINGLE_0603"))
    )
    (comp (ref "D11")
      (value "LO Q976-PS-25")
      (footprint "eagle-import:LED0603")
      (libsource (lib "eagle-import") (part "LED_SINGLE_0603"))
    )
    (comp (ref "DMD_1")
      (value "TEST_POINT_SINGLE_ROUND_100MIL")
      (footprint "eagle-import:100MIL_TP")
      (libsource (lib "eagle-import") (part "TEST_POINT_SINGLE_ROUND_100MIL"))
    )
    (comp (ref "DMD_3")
      (value "TEST_POINT_SINGLE_ROUND_100MIL")
      (footprint "eagle-import:100MIL_TP")
      (libsource (lib "eagle-import") (part "TEST_POINT_SINGLE_ROUND_100MIL"))
    )
    (comp (ref "DMD_5")
      (value "TEST_POINT_SINGLE_ROUND_100MIL")
      (footprint "eagle-import:100MIL_TP")
      (libsource (lib "eagle-import") (part "TEST_POINT_SINGLE_ROUND_100MIL"))
    )
    (comp (ref "DMD_7")
      (value "TEST_POINT_SINGLE_ROUND_100MIL")
      (footprint "eagle-import:100MIL_TP")
      (libsource (lib "eagle-import") (part "TEST_POINT_SINGLE_ROUND_100MIL"))
    )
    (comp (ref "DMD_9")
      (value "TEST_POINT_SINGLE_ROUND_100MIL")
      (footprint "eagle-import:100MIL_TP")
      (libsource (lib "eagle-import") (part "TEST_POINT_SINGLE_ROUND_100MIL"))
    )
    (comp (ref "DMD_11")
      (value "TEST_POINT_SINGLE_ROUND_100MIL")
      (footprint "eagle-import:100MIL_TP")
      (libsource (lib "eagle-import") (part "TEST_POINT_SINGLE_ROUND_100MIL"))
    )
    (comp (ref "DMD_13")
      (value "TEST_POINT_SINGLE_ROUND_100MIL")
      (footprint "eagle-import:100MIL_TP")
      (libsource (lib "eagle-import") (part "TEST_POINT_SINGLE_ROUND_100MIL"))
    )
    (comp (ref "DMD_CON")
      (value "5103308-2")
      (footprint "eagle-import:5103308-2")
      (libsource (lib "eagle-import") (part "CON_02X07_5103308-2"))
    )
    (comp (ref "DMD_PWR")
      (value "CON_01X03_26-64-4040_(KEYPIN1)")
      (footprint "eagle-import:26-64-4040(KEYPIN1)")
      (fields (field (name "LABEL01") "12V") (field (name "LABEL02") "5V") (field (name "LABEL03") "GND"))
      (libsource (lib "eagle-import") (part "CON_01X03_26-64-4040_(KEYPIN1)"))
    )
    (comp (ref "DOOR_OUT")
      (value "TEST_POINT_SINGLE_ROUND_100MIL")
      (footprint "eagle-import:100MIL_TP")
      (libsource (lib "eagle-import") (part "TEST_POINT_SINGLE_ROUND_100MIL"))
    )
    (comp (ref "ENTER_OUT")
      (value "TEST_POINT_SINGLE_ROUND_100MIL")
      (footprint "eagle-import:100MIL_TP")
      (libsource (lib "eagle-import") (part "TEST_POINT_SINGLE_ROUND_100MIL"))
    )
    (comp (ref "EXT_RGB_CLK")
      (value "TEST_POINT_SINGLE_ROUND_100MIL")
      (footprint "eagle-import:100MIL_TP")
      (libsource (lib "eagle-import") (part "TEST_POINT_SINGLE_ROUND_100MIL"))
    )
    (comp (ref "EXT_RGB_DATA")
      (value "TEST_POINT_SINGLE_ROUND_100MIL")
      (footprint "eagle-import:100MIL_TP")
      (libsource (lib "eagle-import") (part "TEST_POINT_SINGLE_ROUND_100MIL"))
    )
    (comp (ref "F1")
      (value "4628")
      (footprint "eagle-import:4628")
      (libsource (lib "eagle-import") (part "PTC_FUSE_4628"))
    )
    (comp (ref "F2")
      (value "4628")
      (footprint "eagle-import:4628")
      (libsource (lib "eagle-import") (part "PTC_FUSE_4628"))
    )
    (comp (ref "F3")
      (value "4628")
      (footprint "eagle-import:4628")
      (libsource (lib "eagle-import") (part "PTC_FUSE_4628"))
    )
    (comp (ref "F4")
      (value "4628")
      (footprint "eagle-import:4628")
      (libsource (lib "eagle-import") (part "PTC_FUSE_4628"))
    )
    (comp (ref "F5")
      (value "4628")
      (footprint "eagle-import:4628")
      (libsource (lib "eagle-import") (part "PTC_FUSE_4628"))
    )
    (comp (ref "F6")
      (value "4628")
      (footprint "eagle-import:4628")
      (libsource (lib "eagle-import") (part "PTC_FUSE_4628"))
    )
    (comp (ref "F7")
      (value "4628")
      (footprint "eagle-import:4628")
      (libsource (lib "eagle-import") (part "PTC_FUSE_4628"))
    )
    (comp (ref "FID1")
      (value "FIDUCIAL_100MIL")
      (footprint "eagle-import:FIDUCIAL_100MIL")
      (libsource (lib "eagle-import") (part "FIDUCIAL_100MIL"))
    )
    (comp (ref "FID2")
      (value "FIDUCIAL_100MIL")
      (footprint "eagle-import:FIDUCIAL_100MIL")
      (libsource (lib "eagle-import") (part "FIDUCIAL_100MIL"))
    )
    (comp (ref "FID3")
      (value "FIDUCIAL_100MIL")
      (footprint "eagle-import:FIDUCIAL_100MIL")
      (libsource (lib "eagle-import") (part "FIDUCIAL_100MIL"))
    )
    (comp (ref "FID4")
      (value "FIDUCIAL_0.5MM")
      (footprint "eagle-import:FIDUCIAL_0.5MM")
      (libsource (lib "eagle-import") (part "FIDUCIAL_0.5MM"))
    )
    (comp (ref "FID5")
      (value "FIDUCIAL_0.5MM")
      (footprint "eagle-import:FIDUCIAL_0.5MM")
      (libsource (lib "eagle-import") (part "FIDUCIAL_0.5MM"))
    )
    (comp (ref "FLASHER")
      (value "26-64-4020")
      (footprint "eagle-import:26-64-4020")
      (fields (field (name "LABEL01") "12V") (field (name "LABEL02") "GND"))
      (libsource (lib "eagle-import") (part "CON_01X02_26-64-4020"))
    )
    (comp (ref "GI0")
      (value "TIP102")
      (footprint "eagle-import:TO-220AB")
      (libsource (lib "eagle-import") (part "BJT_NPN_SINGLE_TO-220"))
    )
    (comp (ref "GI1")
      (value "TIP102")
      (footprint "eagle-import:TO-220AB")
      (libsource (lib "eagle-import") (part "BJT_NPN_SINGLE_TO-220"))
    )
    (comp (ref "GI2")
      (value "TIP102")
      (footprint "eagle-import:TO-220AB")
      (libsource (lib "eagle-import") (part "BJT_NPN_SINGLE_TO-220"))
    )
    (comp (ref "GI3")
      (value "TIP102")
      (footprint "eagle-import:TO-220AB")
      (libsource (lib "eagle-import") (part "BJT_NPN_SINGLE_TO-220"))
    )
    (comp (ref "GI4")
      (value "TIP102")
      (footprint "eagle-import:TO-220AB")
      (libsource (lib "eagle-import") (part "BJT_NPN_SINGLE_TO-220"))
    )
    (comp (ref "GI5")
      (value "TIP102")
      (footprint "eagle-import:TO-220AB")
      (libsource (lib "eagle-import") (part "BJT_NPN_SINGLE_TO-220"))
    )
    (comp (ref "GI6")
      (value "TIP102")
      (footprint "eagle-import:TO-220AB")
      (libsource (lib "eagle-import") (part "BJT_NPN_SINGLE_TO-220"))
    )
    (comp (ref "GI7")
      (value "TIP102")
      (footprint "eagle-import:TO-220AB")
      (libsource (lib "eagle-import") (part "BJT_NPN_SINGLE_TO-220"))
    )
    (comp (ref "GI8")
      (value "TIP102")
      (footprint "eagle-import:TO-220AB")
      (libsource (lib "eagle-import") (part "BJT_NPN_SINGLE_TO-220"))
    )
    (comp (ref "GI9")
      (value "TIP102")
      (footprint "eagle-import:TO-220AB")
      (libsource (lib "eagle-import") (part "BJT_NPN_SINGLE_TO-220"))
    )
    (comp (ref "GI10")
      (value "TIP102")
      (footprint "eagle-import:TO-220AB")
      (libsource (lib "eagle-import") (part "BJT_NPN_SINGLE_TO-220"))
    )
    (comp (ref "GI11")
      (value "TIP102")
      (footprint "eagle-import:TO-220AB")
      (libsource (lib "eagle-import") (part "BJT_NPN_SINGLE_TO-220"))
    )
    (comp (ref "GI12")
      (value "TIP102")
      (footprint "eagle-import:TO-220AB")
      (libsource (lib "eagle-import") (part "BJT_NPN_SINGLE_TO-220"))
    )
    (comp (ref "GI13")
      (value "TIP102")
      (footprint "eagle-import:TO-220AB")
      (libsource (lib "eagle-import") (part "BJT_NPN_SINGLE_TO-220"))
    )
    (comp (ref "GI14")
      (value "TIP102")
      (footprint "eagle-import:TO-220AB")
      (libsource (lib "eagle-import") (part "BJT_NPN_SINGLE_TO-220"))
    )
    (comp (ref "GI15")
      (value "TIP102")
      (footprint "eagle-import:TO-220AB")
      (libsource (lib "eagle-import") (part "BJT_NPN_SINGLE_TO-220"))
    )
    (comp (ref "GI15_")
      (value "TEST_POINT_SINGLE_ROUND_100MIL")
      (footprint "eagle-import:100MIL_TP")
      (libsource (lib "eagle-import") (part "TEST_POINT_SINGLE_ROUND_100MIL"))
    )
    (comp (ref "GI_0")
      (value "26-64-4100")
      (footprint "eagle-import:26-64-4100(KEYPIN9)")
      (fields
        (field (name "LABEL01") "GI_0")
        (field (name "LABEL02") "GI_1")
        (field (name "LABEL03") "GI_2")
        (field (name "LABEL04") "GI_3")
        (field (name "LABEL05") "GI_4")
        (field (name "LABEL06") "GI_5")
        (field (name "LABEL07") "GI_6")
        (field (name "LABEL08") "GI_7")
        (field (name "LABEL09") "5V")
      )
      (libsource (lib "eagle-import") (part "CON_01X09_26-64-4100_(KEYPIN9)"))
    )
    (comp (ref "GI_1")
      (value "26-64-4100")
      (footprint "eagle-import:26-64-4100(KEYPIN10)")
      (fields
        (field (name "LABEL01") "GI_8")
        (field (name "LABEL02") "GI_9")
        (field (name "LABEL03") "GI_10")
        (field (name "LABEL04") "GI_11")
        (field (name "LABEL05") "GI_12")
        (field (name "LABEL06") "GI_13")
        (field (name "LABEL07") "GI_14")
        (field (name "LABEL08") "GI_15")
        (field (name "LABEL09") "5V")
      )
      (libsource (lib "eagle-import") (part "CON_01X09_26-64-4100_(KEYPIN10)"))
    )
    (comp (ref "GI_R_0")
      (value "TEST_POINT_SINGLE_ROUND_100MIL")
      (footprint "eagle-import:100MIL_TP")
      (libsource (lib "eagle-import") (part "TEST_POINT_SINGLE_ROUND_100MIL"))
    )
    (comp (ref "GI_R_1")
      (value "TEST_POINT_SINGLE_ROUND_100MIL")
      (footprint "eagle-import:100MIL_TP")
      (libsource (lib "eagle-import") (part "TEST_POINT_SINGLE_ROUND_100MIL"))
    )
    (comp (ref "GI_R_2")
      (value "TEST_POINT_SINGLE_ROUND_100MIL")
      (footprint "eagle-import:100MIL_TP")
      (libsource (lib "eagle-import") (part "TEST_POINT_SINGLE_ROUND_100MIL"))
    )
    (comp (ref "GI_R_3")
      (value "TEST_POINT_SINGLE_ROUND_100MIL")
      (footprint "eagle-import:100MIL_TP")
      (libsource (lib "eagle-import") (part "TEST_POINT_SINGLE_ROUND_100MIL"))
    )
    (comp (ref "GI_R_4")
      (value "TEST_POINT_SINGLE_ROUND_100MIL")
      (footprint "eagle-import:100MIL_TP")
      (libsource (lib "eagle-import") (part "TEST_POINT_SINGLE_ROUND_100MIL"))
    )
    (comp (ref "GI_R_5")
      (value "TEST_POINT_SINGLE_ROUND_100MIL")
      (footprint "eagle-import:100MIL_TP")
      (libsource (lib "eagle-import") (part "TEST_POINT_SINGLE_ROUND_100MIL"))
    )
    (comp (ref "GI_R_6")
      (value "TEST_POINT_SINGLE_ROUND_100MIL")
      (footprint "eagle-import:100MIL_TP")
      (libsource (lib "eagle-import") (part "TEST_POINT_SINGLE_ROUND_100MIL"))
    )
    (comp (ref "GI_R_7")
      (value "TEST_POINT_SINGLE_ROUND_100MIL")
      (footprint "eagle-import:100MIL_TP")
      (libsource (lib "eagle-import") (part "TEST_POINT_SINGLE_ROUND_100MIL"))
    )
    (comp (ref "GI_R_8")
      (value "TEST_POINT_SINGLE_ROUND_100MIL")
      (footprint "eagle-import:100MIL_TP")
      (libsource (lib "eagle-import") (part "TEST_POINT_SINGLE_ROUND_100MIL"))
    )
    (comp (ref "GI_R_9")
      (value "TEST_POINT_SINGLE_ROUND_100MIL")
      (footprint "eagle-import:100MIL_TP")
      (libsource (lib "eagle-import") (part "TEST_POINT_SINGLE_ROUND_100MIL"))
    )
    (comp (ref "GI_R_10")
      (value "TEST_POINT_SINGLE_ROUND_100MIL")
      (footprint "eagle-import:100MIL_TP")
      (libsource (lib "eagle-import") (part "TEST_POINT_SINGLE_ROUND_100MIL"))
    )
    (comp (ref "GI_R_11")
      (value "TEST_POINT_SINGLE_ROUND_100MIL")
      (footprint "eagle-import:100MIL_TP")
      (libsource (lib "eagle-import") (part "TEST_POINT_SINGLE_ROUND_100MIL"))
    )
    (comp (ref "GI_R_12")
      (value "TEST_POINT_SINGLE_ROUND_100MIL")
      (footprint "eagle-import:100MIL_TP")
      (libsource (lib "eagle-import") (part "TEST_POINT_SINGLE_ROUND_100MIL"))
    )
    (comp (ref "GI_R_13")
      (value "TEST_POINT_SINGLE_ROUND_100MIL")
      (footprint "eagle-import:100MIL_TP")
      (libsource (lib "eagle-import") (part "TEST_POINT_SINGLE_ROUND_100MIL"))
    )
    (comp (ref "GI_R_14")
      (value "TEST_POINT_SINGLE_ROUND_100MIL")
      (footprint "eagle-import:100MIL_TP")
      (libsource (lib "eagle-import") (part "TEST_POINT_SINGLE_ROUND_100MIL"))
    )
    (comp (ref "GND")
      (value "TEST_POINT_SINGLE_ROUND_100MIL")
      (footprint "eagle-import:100MIL_TP")
      (libsource (lib "eagle-import") (part "TEST_POINT_SINGLE_ROUND_100MIL"))
    )
    (comp (ref "H2")
      (value "MOUNT_HOLE150MIL")
      (footprint "eagle-import:MOUNT_HOLE_150MIL")
      (libsource (lib "eagle-import") (part "MOUNT_HOLE150MIL"))
    )
    (comp (ref "H3")
      (value "MOUNT_HOLE150MIL")
      (footprint "eagle-import:MOUNT_HOLE_150MIL")
      (libsource (lib "eagle-import") (part "MOUNT_HOLE150MIL"))
    )
    (comp (ref "H4")
      (value "MOUNT_HOLE150MIL")
      (footprint "eagle-import:MOUNT_HOLE_150MIL")
      (libsource (lib "eagle-import") (part "MOUNT_HOLE150MIL"))
    )
    (comp (ref "H11")
      (value "MOUNT_HOLE150MIL")
      (footprint "eagle-import:MOUNT_HOLE_150MIL")
      (libsource (lib "eagle-import") (part "MOUNT_HOLE150MIL"))
    )
    (comp (ref "H19")
      (value "MOUNT_HOLE150MIL")
      (footprint "eagle-import:MOUNT_HOLE_150MIL")
      (libsource (lib "eagle-import") (part "MOUNT_HOLE150MIL"))
    )
    (comp (ref "H21")
      (value "MOUNT_HOLE150MIL")
      (footprint "eagle-import:MOUNT_HOLE_150MIL")
      (libsource (lib "eagle-import") (part "MOUNT_HOLE150MIL"))
    )
    (comp (ref "H22")
      (value "MOUNT_HOLE150MIL")
      (footprint "eagle-import:MOUNT_HOLE_150MIL")
      (libsource (lib "eagle-import") (part "MOUNT_HOLE150MIL"))
    )
    (comp (ref "H23")
      (value "MOUNT_HOLE150MIL")
      (footprint "eagle-import:MOUNT_HOLE_150MIL")
      (libsource (lib "eagle-import") (part "MOUNT_HOLE150MIL"))
    )
    (comp (ref "H24")
      (value "MOUNT_HOLE150MIL")
      (footprint "eagle-import:MOUNT_HOLE_150MIL")
      (libsource (lib "eagle-import") (part "MOUNT_HOLE150MIL"))
    )
    (comp (ref "H26")
      (value "MOUNT_HOLE150MIL")
      (footprint "eagle-import:MOUNT_HOLE_150MIL")
      (libsource (lib "eagle-import") (part "MOUNT_HOLE150MIL"))
    )
    (comp (ref "H27")
      (value "MOUNT_HOLE150MIL")
      (footprint "eagle-import:MOUNT_HOLE_150MIL")
      (libsource (lib "eagle-import") (part "MOUNT_HOLE150MIL"))
    )
    (comp (ref "H28")
      (value "MOUNT_HOLE150MIL")
      (footprint "eagle-import:MOUNT_HOLE_150MIL")
      (libsource (lib "eagle-import") (part "MOUNT_HOLE150MIL"))
    )
    (comp (ref "H30")
      (value "MOUNT_HOLE150MIL")
      (footprint "eagle-import:MOUNT_HOLE_150MIL")
      (libsource (lib "eagle-import") (part "MOUNT_HOLE150MIL"))
    )
    (comp (ref "H31")
      (value "MOUNT_HOLE150MIL")
      (footprint "eagle-import:MOUNT_HOLE_150MIL")
      (libsource (lib "eagle-import") (part "MOUNT_HOLE150MIL"))
    )
    (comp (ref "H32")
      (value "MOUNT_HOLE150MIL")
      (footprint "eagle-import:MOUNT_HOLE_150MIL")
      (libsource (lib "eagle-import") (part "MOUNT_HOLE150MIL"))
    )
    (comp (ref "H33")
      (value "MOUNT_HOLE150MIL")
      (footprint "eagle-import:MOUNT_HOLE_150MIL")
      (libsource (lib "eagle-import") (part "MOUNT_HOLE150MIL"))
    )
    (comp (ref "H34")
      (value "MOUNT_HOLE150MIL")
      (footprint "eagle-import:MOUNT_HOLE_150MIL")
      (libsource (lib "eagle-import") (part "MOUNT_HOLE150MIL"))
    )
    (comp (ref "IC2")
      (value "PIC32MX795F512L-80I/PT")
      (footprint "eagle-import:TQ100-PT")
      (libsource (lib "eagle-import") (part "PIC32MX7X5FL-PT"))
    )
    (comp (ref "IC3")
      (value "CD74HCT244E")
      (footprint "eagle-import:DIL20")
      (libsource (lib "eagle-import") (part "74244NLS"))
    )
    (comp (ref "IC4")
      (value "CD74HCT244E")
      (footprint "eagle-import:DIL20")
      (libsource (lib "eagle-import") (part "74244NLS"))
    )
    (comp (ref "IC5")
      (value "ULN2803A")
      (footprint "eagle-import:DIL18")
      (libsource (lib "eagle-import") (part "ULN2803A"))
    )
    (comp (ref "KNOCKER")
      (value "26-64-4020")
      (footprint "eagle-import:26-64-4020")
      (libsource (lib "eagle-import") (part "CON_01X02_26-64-4020"))
    )
    (comp (ref "LIGHT_COL")
      (value "26-64-4100")
      (footprint "eagle-import:26-64-4100(KEYPIN2)")
      (fields
        (field (name "LABEL02") "LIGHT_C_0")
        (field (name "LABEL03") "LIGHT_C_1")
        (field (name "LABEL04") "LIGHT_C_2")
        (field (name "LABEL05") "LIGHT_C_3")
        (field (name "LABEL06") "LIGHT_C_4")
        (field (name "LABEL07") "LIGHT_C_5")
        (field (name "LABEL08") "LIGHT_C_6")
        (field (name "LABEL09") "LIGHT_C_7")
      )
      (libsource (lib "eagle-import") (part "CON_01X09_26-64-4100_(KEYPIN2)"))
    )
    (comp (ref "LIGHT_C_0")
      (value "TEST_POINT_SINGLE_ROUND_100MIL")
      (footprint "eagle-import:100MIL_TP")
      (libsource (lib "eagle-import") (part "TEST_POINT_SINGLE_ROUND_100MIL"))
    )
    (comp (ref "LIGHT_C_1")
      (value "TEST_POINT_SINGLE_ROUND_100MIL")
      (footprint "eagle-import:100MIL_TP")
      (libsource (lib "eagle-import") (part "TEST_POINT_SINGLE_ROUND_100MIL"))
    )
    (comp (ref "LIGHT_C_2")
      (value "TEST_POINT_SINGLE_ROUND_100MIL")
      (footprint "eagle-import:100MIL_TP")
      (libsource (lib "eagle-import") (part "TEST_POINT_SINGLE_ROUND_100MIL"))
    )
    (comp (ref "LIGHT_C_3")
      (value "TEST_POINT_SINGLE_ROUND_100MIL")
      (footprint "eagle-import:100MIL_TP")
      (libsource (lib "eagle-import") (part "TEST_POINT_SINGLE_ROUND_100MIL"))
    )
    (comp (ref "LIGHT_C_4")
      (value "TEST_POINT_SINGLE_ROUND_100MIL")
      (footprint "eagle-import:100MIL_TP")
      (libsource (lib "eagle-import") (part "TEST_POINT_SINGLE_ROUND_100MIL"))
    )
    (comp (ref "LIGHT_C_5")
      (value "TEST_POINT_SINGLE_ROUND_100MIL")
      (footprint "eagle-import:100MIL_TP")
      (libsource (lib "eagle-import") (part "TEST_POINT_SINGLE_ROUND_100MIL"))
    )
    (comp (ref "LIGHT_C_6")
      (value "TEST_POINT_SINGLE_ROUND_100MIL")
      (footprint "eagle-import:100MIL_TP")
      (libsource (lib "eagle-import") (part "TEST_POINT_SINGLE_ROUND_100MIL"))
    )
    (comp (ref "LIGHT_C_7")
      (value "TEST_POINT_SINGLE_ROUND_100MIL")
      (footprint "eagle-import:100MIL_TP")
      (libsource (lib "eagle-import") (part "TEST_POINT_SINGLE_ROUND_100MIL"))
    )
    (comp (ref "LIGHT_ROW")
      (value "26-64-4100")
      (footprint "eagle-import:26-64-4100(KEYPIN3)")
      (fields
        (field (name "LABEL02") "LIGHT_R_0")
        (field (name "LABEL03") "LIGHT_R_1")
        (field (name "LABEL04") "LIGHT_R_2")
        (field (name "LABEL05") "LIGHT_R_3")
        (field (name "LABEL06") "LIGHT_R_4")
        (field (name "LABEL07") "LIGHT_R_5")
        (field (name "LABEL08") "LIGHT_R_6")
        (field (name "LABEL09") "LIGHT_R_7")
      )
      (libsource (lib "eagle-import") (part "CON_01X09_26-64-4100_(KEYPIN3)"))
    )
    (comp (ref "LIGHT_R_0")
      (value "TEST_POINT_SINGLE_ROUND_100MIL")
      (footprint "eagle-import:100MIL_TP")
      (libsource (lib "eagle-import") (part "TEST_POINT_SINGLE_ROUND_100MIL"))
    )
    (comp (ref "LIGHT_R_1")
      (value "TEST_POINT_SINGLE_ROUND_100MIL")
      (footprint "eagle-import:100MIL_TP")
      (libsource (lib "eagle-import") (part "TEST_POINT_SINGLE_ROUND_100MIL"))
    )
    (comp (ref "LIGHT_R_2")
      (value "TEST_POINT_SINGLE_ROUND_100MIL")
      (footprint "eagle-import:100MIL_TP")
      (libsource (lib "eagle-import") (part "TEST_POINT_SINGLE_ROUND_100MIL"))
    )
    (comp (ref "LIGHT_R_3")
      (value "TEST_POINT_SINGLE_ROUND_100MIL")
      (footprint "eagle-import:100MIL_TP")
      (libsource (lib "eagle-import") (part "TEST_POINT_SINGLE_ROUND_100MIL"))
    )
    (comp (ref "LIGHT_R_4")
      (value "TEST_POINT_SINGLE_ROUND_100MIL")
      (footprint "eagle-import:100MIL_TP")
      (libsource (lib "eagle-import") (part "TEST_POINT_SINGLE_ROUND_100MIL"))
    )
    (comp (ref "LIGHT_R_5")
      (value "TEST_POINT_SINGLE_ROUND_100MIL")
      (footprint "eagle-import:100MIL_TP")
      (libsource (lib "eagle-import") (part "TEST_POINT_SINGLE_ROUND_100MIL"))
    )
    (comp (ref "LIGHT_R_6")
      (value "TEST_POINT_SINGLE_ROUND_100MIL")
      (footprint "eagle-import:100MIL_TP")
      (libsource (lib "eagle-import") (part "TEST_POINT_SINGLE_ROUND_100MIL"))
    )
    (comp (ref "LIGHT_R_7")
      (value "TEST_POINT_SINGLE_ROUND_100MIL")
      (footprint "eagle-import:100MIL_TP")
      (libsource (lib "eagle-import") (part "TEST_POINT_SINGLE_ROUND_100MIL"))
    )
    (comp (ref "LOGO1")
      (value "SPOOKY_LOGOSPOOKY_LOGO")
      (footprint "eagle-import:SPOOKY_LOGO")
      (libsource (lib "eagle-import") (part "SPOOKY_LOGOSPOOKY_LOGO"))
    )
    (comp (ref "L_FLIP_OUT")
      (value "TEST_POINT_SINGLE_ROUND_100MIL")
      (footprint "eagle-import:100MIL_TP")
      (libsource (lib "eagle-import") (part "TEST_POINT_SINGLE_ROUND_100MIL"))
    )
    (comp (ref "OPTO_1")
      (value "26-64-4040")
      (footprint "eagle-import:26-64-4040")
      (libsource (lib "eagle-import") (part "CON_01X04_26-64-4040"))
    )
    (comp (ref "OPTO_1_")
      (value "TEST_POINT_SINGLE_ROUND_100MIL")
      (footprint "eagle-import:100MIL_TP")
      (libsource (lib "eagle-import") (part "TEST_POINT_SINGLE_ROUND_100MIL"))
    )
    (comp (ref "OPTO_2")
      (value "26-64-4040")
      (footprint "eagle-import:26-64-4040")
      (libsource (lib "eagle-import") (part "CON_01X04_26-64-4040"))
    )
    (comp (ref "OPTO_2_")
      (value "TEST_POINT_SINGLE_ROUND_100MIL")
      (footprint "eagle-import:100MIL_TP")
      (libsource (lib "eagle-import") (part "TEST_POINT_SINGLE_ROUND_100MIL"))
    )
    (comp (ref "OPTO_3")
      (value "26-64-4040")
      (footprint "eagle-import:26-64-4040")
      (libsource (lib "eagle-import") (part "CON_01X04_26-64-4040"))
    )
    (comp (ref "OPTO_3_")
      (value "TEST_POINT_SINGLE_ROUND_100MIL")
      (footprint "eagle-import:100MIL_TP")
      (libsource (lib "eagle-import") (part "TEST_POINT_SINGLE_ROUND_100MIL"))
    )
    (comp (ref "OPTO_4")
      (value "26-64-4040")
      (footprint "eagle-import:26-64-4040")
      (libsource (lib "eagle-import") (part "CON_01X04_26-64-4040"))
    )
    (comp (ref "OPTO_4_")
      (value "TEST_POINT_SINGLE_ROUND_100MIL")
      (footprint "eagle-import:100MIL_TP")
      (libsource (lib "eagle-import") (part "TEST_POINT_SINGLE_ROUND_100MIL"))
    )
    (comp (ref "OPTO_5")
      (value "26-64-4040")
      (footprint "eagle-import:26-64-4040")
      (libsource (lib "eagle-import") (part "CON_01X04_26-64-4040"))
    )
    (comp (ref "OPTO_5_")
      (value "TEST_POINT_SINGLE_ROUND_100MIL")
      (footprint "eagle-import:100MIL_TP")
      (libsource (lib "eagle-import") (part "TEST_POINT_SINGLE_ROUND_100MIL"))
    )
    (comp (ref "OPTO_6")
      (value "26-64-4040")
      (footprint "eagle-import:26-64-4040")
      (libsource (lib "eagle-import") (part "CON_01X04_26-64-4040"))
    )
    (comp (ref "OPTO_6_")
      (value "TEST_POINT_SINGLE_ROUND_100MIL")
      (footprint "eagle-import:100MIL_TP")
      (libsource (lib "eagle-import") (part "TEST_POINT_SINGLE_ROUND_100MIL"))
    )
    (comp (ref "OPTO_7")
      (value "26-64-4040")
      (footprint "eagle-import:26-64-4040")
      (libsource (lib "eagle-import") (part "CON_01X04_26-64-4040"))
    )
    (comp (ref "OPTO_7_")
      (value "TEST_POINT_SINGLE_ROUND_100MIL")
      (footprint "eagle-import:100MIL_TP")
      (libsource (lib "eagle-import") (part "TEST_POINT_SINGLE_ROUND_100MIL"))
    )
    (comp (ref "PHABULOUS")
      (value "26-64-4050")
      (footprint "eagle-import:2.54MM_01X20_PIN_HEADER")
      (fields
        (field (name "LABEL01") "GND")
        (field (name "LABEL02") "3.3V")
        (field (name "LABEL03") "5V")
        (field (name "LABEL04") "I2C_SDA")
        (field (name "LABEL05") "I2C_SCL")
        (field (name "LABEL06") "GND")
        (field (name "LABEL07") "12V")
        (field (name "LABEL08") "GND")
        (field (name "LABEL09") "SERVO_3")
        (field (name "LABEL10") "SERVO_4")
        (field (name "LABEL11") "GND")
        (field (name "LABEL12") "PROP_AUX2")
        (field (name "LABEL13") "PROP_AUX3")
        (field (name "LABEL14") "PROP_AUX4")
        (field (name "LABEL15") "PROP_AUX5")
        (field (name "LABEL16") "PROP_AUX6")
        (field (name "LABEL17") "PROP_AUX7")
        (field (name "LABEL18") "PROP_AUX8")
        (field (name "LABEL19") "PROP_AUX9")
      )
      (libsource (lib "eagle-import") (part "CON_01X20_2.54MM_PIN_HEADER"))
    )
    (comp (ref "PIC32_TC")
      (value "TC2030-FTDI-TTL-232R")
      (footprint "eagle-import:TC2030")
      (libsource (lib "eagle-import") (part "CON_02X03_TC2030"))
    )
    (comp (ref "PIC32_UART")
      (value "CON_01X06_2.54MM_PIN_HEADER")
      (footprint "eagle-import:2.54MM_01X06_PIN_HEADER")
      (fields
        (field (name "LABEL01") "GND")
        (field (name "LABEL04") "RX_PIC32")
        (field (name "LABEL05") "TX_PIC32")
        (field (name "LABEL06") "!RST!_PIC32")
      )
      (libsource (lib "eagle-import") (part "CON_01X06_2.54MM_PIN_HEADER"))
    )
    (comp (ref "PICKIT3")
      (value "CON_01X06_2.54MM_PIN_HEADER")
      (footprint "eagle-import:2.54MM_01X06_PIN_HEADER")
      (libsource (lib "eagle-import") (part "CON_01X06_2.54MM_PIN_HEADER"))
    )
    (comp (ref "PICKIT3_TC")
      (value "TC2030-PKT-NL")
      (footprint "eagle-import:TC2030")
      (libsource (lib "eagle-import") (part "CON_02X03_TC2030"))
    )
    (comp (ref "PIC_PROGRAM")
      (value "TACT_6MM")
      (footprint "eagle-import:TACT6MM")
      (libsource (lib "eagle-import") (part "TACT_6MM"))
    )
    (comp (ref "PIC_RESET")
      (value "TACT_6MM")
      (footprint "eagle-import:TACT6MM")
      (libsource (lib "eagle-import") (part "TACT_6MM"))
    )
    (comp (ref "PROP_ACT")
      (value "LG R971-KN-1")
      (footprint "eagle-import:LED_0805")
      (libsource (lib "eagle-import") (part "PP_LED_LED_SINGLE_0805"))
    )
    (comp (ref "PROP_AUX0")
      (value "TEST_POINT_SINGLE_ROUND_100MIL")
      (footprint "eagle-import:100MIL_TP")
      (libsource (lib "eagle-import") (part "TEST_POINT_SINGLE_ROUND_100MIL"))
    )
    (comp (ref "PROP_AUX1")
      (value "TEST_POINT_SINGLE_ROUND_100MIL")
      (footprint "eagle-import:100MIL_TP")
      (libsource (lib "eagle-import") (part "TEST_POINT_SINGLE_ROUND_100MIL"))
    )
    (comp (ref "PROP_CONFIG")
      (value "TACT_6MM")
      (footprint "eagle-import:TACT6MM")
      (libsource (lib "eagle-import") (part "TACT_6MM"))
    )
    (comp (ref "PROP_RESET")
      (value "TACT_6MM")
      (footprint "eagle-import:TACT6MM")
      (libsource (lib "eagle-import") (part "TACT_6MM"))
    )
    (comp (ref "PROP_TC")
      (value "TC2030-FTDI-TTL-232R")
      (footprint "eagle-import:TC2030")
      (libsource (lib "eagle-import") (part "CON_02X03_TC2030"))
    )
    (comp (ref "PROP_UART")
      (value "CON_01X06_2.54MM_PIN_HEADER")
      (footprint "eagle-import:2.54MM_01X06_PIN_HEADER")
      (fields
        (field (name "LABEL01") "GND")
        (field (name "LABEL04") "RX_PROP")
        (field (name "LABEL05") "TX_PROP")
        (field (name "LABEL06") "!RES!_PROP")
      )
      (libsource (lib "eagle-import") (part "CON_01X06_2.54MM_PIN_HEADER"))
    )
    (comp (ref "PSU_PWR")
      (value "LG R971-KN-1")
      (footprint "eagle-import:LED_0805")
      (libsource (lib "eagle-import") (part "PP_LED_LED_SINGLE_0805"))
    )
    (comp (ref "R1")
      (value "10K")
      (footprint "eagle-import:0805")
      (libsource (lib "eagle-import") (part "RESISTOR_0805"))
    )
    (comp (ref "R2")
      (value "2K")
      (footprint "eagle-import:0805")
      (libsource (lib "eagle-import") (part "RESISTOR_0805"))
    )
    (comp (ref "R3")
      (value "0")
      (footprint "eagle-import:0805")
      (libsource (lib "eagle-import") (part "RESISTOR_0805"))
    )
    (comp (ref "R4")
      (value "10K")
      (footprint "eagle-import:0805")
      (libsource (lib "eagle-import") (part "RESISTOR_0805"))
    )
    (comp (ref "R5")
      (value "1K")
      (footprint "eagle-import:0805")
      (libsource (lib "eagle-import") (part "RESISTOR_0805"))
    )
    (comp (ref "R6")
      (value "2K")
      (footprint "eagle-import:0805")
      (libsource (lib "eagle-import") (part "RESISTOR_0805"))
    )
    (comp (ref "R7")
      (value "1K")
      (footprint "eagle-import:0805")
      (libsource (lib "eagle-import") (part "RESISTOR_0805"))
    )
    (comp (ref "R8")
      (value "200")
      (footprint "eagle-import:0805")
      (libsource (lib "eagle-import") (part "RESISTOR_0805"))
    )
    (comp (ref "R9")
      (value "2K")
      (footprint "eagle-import:0805")
      (libsource (lib "eagle-import") (part "RESISTOR_0805"))
    )
    (comp (ref "R10")
      (value "1K")
      (footprint "eagle-import:0805")
      (libsource (lib "eagle-import") (part "RESISTOR_0805"))
    )
    (comp (ref "R11")
      (value "2K")
      (footprint "eagle-import:0805")
      (libsource (lib "eagle-import") (part "RESISTOR_0805"))
    )
    (comp (ref "R12")
      (value "50")
      (footprint "eagle-import:0805")
      (libsource (lib "eagle-import") (part "RESISTOR_0805"))
    )
    (comp (ref "R13")
      (value "50")
      (footprint "eagle-import:0805")
      (libsource (lib "eagle-import") (part "RESISTOR_0805"))
    )
    (comp (ref "R14")
      (value "50")
      (footprint "eagle-import:0805")
      (libsource (lib "eagle-import") (part "RESISTOR_0805"))
    )
    (comp (ref "R15")
      (value "1K")
      (footprint "eagle-import:0805")
      (libsource (lib "eagle-import") (part "RESISTOR_0805"))
    )
    (comp (ref "R16")
      (value "10K")
      (footprint "eagle-import:0805")
      (libsource (lib "eagle-import") (part "RESISTOR_0805"))
    )
    (comp (ref "R17")
      (value "10K")
      (footprint "eagle-import:0805")
      (libsource (lib "eagle-import") (part "RESISTOR_0805"))
    )
    (comp (ref "R18")
      (value "10K")
      (footprint "eagle-import:0805")
      (libsource (lib "eagle-import") (part "RESISTOR_0805"))
    )
    (comp (ref "R19")
      (value "10K")
      (footprint "eagle-import:0805")
      (libsource (lib "eagle-import") (part "RESISTOR_0805"))
    )
    (comp (ref "R20")
      (value "10K")
      (footprint "eagle-import:0805")
      (libsource (lib "eagle-import") (part "RESISTOR_0805"))
    )
    (comp (ref "R21")
      (value "10K")
      (footprint "eagle-import:0805")
      (libsource (lib "eagle-import") (part "RESISTOR_0805"))
    )
    (comp (ref "R22")
      (value "10K")
      (footprint "eagle-import:0805")
      (libsource (lib "eagle-import") (part "RESISTOR_0805"))
    )
    (comp (ref "R23")
      (value "10K")
      (footprint "eagle-import:0805")
      (libsource (lib "eagle-import") (part "RESISTOR_0805"))
    )
    (comp (ref "R24")
      (value "10K")
      (footprint "eagle-import:0805")
      (libsource (lib "eagle-import") (part "RESISTOR_0805"))
    )
    (comp (ref "R25")
      (value "10K")
      (footprint "eagle-import:0805")
      (libsource (lib "eagle-import") (part "RESISTOR_0805"))
    )
    (comp (ref "R26")
      (value "100")
      (footprint "eagle-import:0805")
      (libsource (lib "eagle-import") (part "RESISTOR_0805"))
    )
    (comp (ref "R27")
      (value "2K")
      (footprint "eagle-import:0805")
      (libsource (lib "eagle-import") (part "RESISTOR_0805"))
    )
    (comp (ref "R28")
      (value "1K")
      (footprint "eagle-import:0805")
      (libsource (lib "eagle-import") (part "RESISTOR_0805"))
    )
    (comp (ref "R29")
      (value "2K")
      (footprint "eagle-import:0805")
      (libsource (lib "eagle-import") (part "RESISTOR_0805"))
    )
    (comp (ref "R30")
      (value "360")
      (footprint "eagle-import:0805")
      (libsource (lib "eagle-import") (part "RESISTOR_0805"))
    )
    (comp (ref "R31")
      (value "1K")
      (footprint "eagle-import:0805")
      (libsource (lib "eagle-import") (part "RESISTOR_0805"))
    )
    (comp (ref "R32")
      (value "4.7K")
      (footprint "eagle-import:0805")
      (libsource (lib "eagle-import") (part "RESISTOR_0805"))
    )
    (comp (ref "R33")
      (value "2K")
      (footprint "eagle-import:0805")
      (libsource (lib "eagle-import") (part "RESISTOR_0805"))
    )
    (comp (ref "R34")
      (value "4.7K")
      (footprint "eagle-import:0805")
      (libsource (lib "eagle-import") (part "RESISTOR_0805"))
    )
    (comp (ref "R35")
      (value "10K")
      (footprint "eagle-import:0805")
      (libsource (lib "eagle-import") (part "RESISTOR_0805"))
    )
    (comp (ref "R36")
      (value "10K")
      (footprint "eagle-import:0805")
      (libsource (lib "eagle-import") (part "RESISTOR_0805"))
    )
    (comp (ref "R37")
      (value "10K")
      (footprint "eagle-import:0805")
      (libsource (lib "eagle-import") (part "RESISTOR_0805"))
    )
    (comp (ref "R38")
      (value "10K")
      (footprint "eagle-import:0805")
      (libsource (lib "eagle-import") (part "RESISTOR_0805"))
    )
    (comp (ref "R39")
      (value "10K")
      (footprint "eagle-import:0805")
      (libsource (lib "eagle-import") (part "RESISTOR_0805"))
    )
    (comp (ref "R40")
      (value "10K")
      (footprint "eagle-import:0805")
      (libsource (lib "eagle-import") (part "RESISTOR_0805"))
    )
    (comp (ref "R41")
      (value "10K")
      (footprint "eagle-import:0805")
      (libsource (lib "eagle-import") (part "RESISTOR_0805"))
    )
    (comp (ref "R42")
      (value "10K")
      (footprint "eagle-import:0805")
      (libsource (lib "eagle-import") (part "RESISTOR_0805"))
    )
    (comp (ref "R43")
      (value "10K")
      (footprint "eagle-import:0805")
      (libsource (lib "eagle-import") (part "RESISTOR_0805"))
    )
    (comp (ref "R44")
      (value "10K")
      (footprint "eagle-import:0805")
      (libsource (lib "eagle-import") (part "RESISTOR_0805"))
    )
    (comp (ref "R45")
      (value "10K")
      (footprint "eagle-import:0805")
      (libsource (lib "eagle-import") (part "RESISTOR_0805"))
    )
    (comp (ref "R46")
      (value "10K")
      (footprint "eagle-import:0805")
      (libsource (lib "eagle-import") (part "RESISTOR_0805"))
    )
    (comp (ref "R47")
      (value "10K")
      (footprint "eagle-import:0805")
      (libsource (lib "eagle-import") (part "RESISTOR_0805"))
    )
    (comp (ref "R48")
      (value "10K")
      (footprint "eagle-import:0805")
      (libsource (lib "eagle-import") (part "RESISTOR_0805"))
    )
    (comp (ref "R49")
      (value "10K")
      (footprint "eagle-import:0805")
      (libsource (lib "eagle-import") (part "RESISTOR_0805"))
    )
    (comp (ref "R50")
      (value "10K")
      (footprint "eagle-import:0805")
      (libsource (lib "eagle-import") (part "RESISTOR_0805"))
    )
    (comp (ref "R51")
      (value "10K")
      (footprint "eagle-import:0805")
      (libsource (lib "eagle-import") (part "RESISTOR_0805"))
    )
    (comp (ref "R52")
      (value "10K")
      (footprint "eagle-import:0805")
      (libsource (lib "eagle-import") (part "RESISTOR_0805"))
    )
    (comp (ref "R53")
      (value "10K")
      (footprint "eagle-import:0805")
      (libsource (lib "eagle-import") (part "RESISTOR_0805"))
    )
    (comp (ref "R54")
      (value "10K")
      (footprint "eagle-import:0805")
      (libsource (lib "eagle-import") (part "RESISTOR_0805"))
    )
    (comp (ref "R55")
      (value "10K")
      (footprint "eagle-import:0805")
      (libsource (lib "eagle-import") (part "RESISTOR_0805"))
    )
    (comp (ref "R56")
      (value "10K")
      (footprint "eagle-import:0805")
      (libsource (lib "eagle-import") (part "RESISTOR_0805"))
    )
    (comp (ref "R57")
      (value "10K")
      (footprint "eagle-import:0805")
      (libsource (lib "eagle-import") (part "RESISTOR_0805"))
    )
    (comp (ref "R58")
      (value "10K")
      (footprint "eagle-import:0805")
      (libsource (lib "eagle-import") (part "RESISTOR_0805"))
    )
    (comp (ref "R59")
      (value "10K")
      (footprint "eagle-import:0805")
      (libsource (lib "eagle-import") (part "RESISTOR_0805"))
    )
    (comp (ref "R60")
      (value "10K")
      (footprint "eagle-import:0805")
      (libsource (lib "eagle-import") (part "RESISTOR_0805"))
    )
    (comp (ref "R61")
      (value "10K")
      (footprint "eagle-import:0805")
      (libsource (lib "eagle-import") (part "RESISTOR_0805"))
    )
    (comp (ref "R62")
      (value "10K")
      (footprint "eagle-import:0805")
      (libsource (lib "eagle-import") (part "RESISTOR_0805"))
    )
    (comp (ref "R63")
      (value "10K")
      (footprint "eagle-import:0805")
      (libsource (lib "eagle-import") (part "RESISTOR_0805"))
    )
    (comp (ref "R64")
      (value "10K")
      (footprint "eagle-import:0805")
      (libsource (lib "eagle-import") (part "RESISTOR_0805"))
    )
    (comp (ref "R65")
      (value "10K")
      (footprint "eagle-import:0805")
      (libsource (lib "eagle-import") (part "RESISTOR_0805"))
    )
    (comp (ref "R66")
      (value "10K")
      (footprint "eagle-import:0805")
      (libsource (lib "eagle-import") (part "RESISTOR_0805"))
    )
    (comp (ref "R67")
      (value "10K")
      (footprint "eagle-import:0805")
      (libsource (lib "eagle-import") (part "RESISTOR_0805"))
    )
    (comp (ref "R68")
      (value "10K")
      (footprint "eagle-import:0805")
      (libsource (lib "eagle-import") (part "RESISTOR_0805"))
    )
    (comp (ref "R69")
      (value "10K")
      (footprint "eagle-import:0805")
      (libsource (lib "eagle-import") (part "RESISTOR_0805"))
    )
    (comp (ref "R70")
      (value "10K")
      (footprint "eagle-import:0805")
      (libsource (lib "eagle-import") (part "RESISTOR_0805"))
    )
    (comp (ref "R71")
      (value "10K")
      (footprint "eagle-import:0805")
      (libsource (lib "eagle-import") (part "RESISTOR_0805"))
    )
    (comp (ref "R72")
      (value "10K")
      (footprint "eagle-import:0805")
      (libsource (lib "eagle-import") (part "RESISTOR_0805"))
    )
    (comp (ref "R73")
      (value "10K")
      (footprint "eagle-import:0805")
      (libsource (lib "eagle-import") (part "RESISTOR_0805"))
    )
    (comp (ref "R74")
      (value "10K")
      (footprint "eagle-import:0805")
      (libsource (lib "eagle-import") (part "RESISTOR_0805"))
    )
    (comp (ref "R75")
      (value "10K")
      (footprint "eagle-import:0805")
      (libsource (lib "eagle-import") (part "RESISTOR_0805"))
    )
    (comp (ref "R76")
      (value "10K")
      (footprint "eagle-import:0805")
      (libsource (lib "eagle-import") (part "RESISTOR_0805"))
    )
    (comp (ref "R77")
      (value "10K")
      (footprint "eagle-import:0805")
      (libsource (lib "eagle-import") (part "RESISTOR_0805"))
    )
    (comp (ref "R78")
      (value "10K")
      (footprint "eagle-import:0805")
      (libsource (lib "eagle-import") (part "RESISTOR_0805"))
    )
    (comp (ref "R79")
      (value "10K")
      (footprint "eagle-import:0805")
      (libsource (lib "eagle-import") (part "RESISTOR_0805"))
    )
    (comp (ref "R80")
      (value "10K")
      (footprint "eagle-import:0805")
      (libsource (lib "eagle-import") (part "RESISTOR_0805"))
    )
    (comp (ref "R81")
      (value "10K")
      (footprint "eagle-import:0805")
      (libsource (lib "eagle-import") (part "RESISTOR_0805"))
    )
    (comp (ref "R82")
      (value "10K")
      (footprint "eagle-import:0805")
      (libsource (lib "eagle-import") (part "RESISTOR_0805"))
    )
    (comp (ref "R83")
      (value "10K")
      (footprint "eagle-import:0805")
      (libsource (lib "eagle-import") (part "RESISTOR_0805"))
    )
    (comp (ref "R84")
      (value "360")
      (footprint "eagle-import:0805")
      (libsource (lib "eagle-import") (part "RESISTOR_0805"))
    )
    (comp (ref "R85")
      (value "10K")
      (footprint "eagle-import:0805")
      (libsource (lib "eagle-import") (part "RESISTOR_0805"))
    )
    (comp (ref "R86")
      (value "360")
      (footprint "eagle-import:0805")
      (libsource (lib "eagle-import") (part "RESISTOR_0805"))
    )
    (comp (ref "R87")
      (value "10K")
      (footprint "eagle-import:0805")
      (libsource (lib "eagle-import") (part "RESISTOR_0805"))
    )
    (comp (ref "R88")
      (value "360")
      (footprint "eagle-import:0805")
      (libsource (lib "eagle-import") (part "RESISTOR_0805"))
    )
    (comp (ref "R89")
      (value "10K")
      (footprint "eagle-import:0805")
      (libsource (lib "eagle-import") (part "RESISTOR_0805"))
    )
    (comp (ref "R90")
      (value "360")
      (footprint "eagle-import:0805")
      (libsource (lib "eagle-import") (part "RESISTOR_0805"))
    )
    (comp (ref "R91")
      (value "10K")
      (footprint "eagle-import:0805")
      (libsource (lib "eagle-import") (part "RESISTOR_0805"))
    )
    (comp (ref "R92")
      (value "360")
      (footprint "eagle-import:0805")
      (libsource (lib "eagle-import") (part "RESISTOR_0805"))
    )
    (comp (ref "R93")
      (value "10K")
      (footprint "eagle-import:0805")
      (libsource (lib "eagle-import") (part "RESISTOR_0805"))
    )
    (comp (ref "R94")
      (value "360")
      (footprint "eagle-import:0805")
      (libsource (lib "eagle-import") (part "RESISTOR_0805"))
    )
    (comp (ref "R95")
      (value "10K")
      (footprint "eagle-import:0805")
      (libsource (lib "eagle-import") (part "RESISTOR_0805"))
    )
    (comp (ref "R96")
      (value "360")
      (footprint "eagle-import:0805")
      (libsource (lib "eagle-import") (part "RESISTOR_0805"))
    )
    (comp (ref "R97")
      (value "10K")
      (footprint "eagle-import:0805")
      (libsource (lib "eagle-import") (part "RESISTOR_0805"))
    )
    (comp (ref "R98")
      (value "360")
      (footprint "eagle-import:0805")
      (libsource (lib "eagle-import") (part "RESISTOR_0805"))
    )
    (comp (ref "R99")
      (value "360")
      (footprint "eagle-import:0805")
      (libsource (lib "eagle-import") (part "RESISTOR_0805"))
    )
    (comp (ref "R100")
      (value "360")
      (footprint "eagle-import:0805")
      (libsource (lib "eagle-import") (part "RESISTOR_0805"))
    )
    (comp (ref "R101")
      (value "360")
      (footprint "eagle-import:0805")
      (libsource (lib "eagle-import") (part "RESISTOR_0805"))
    )
    (comp (ref "R102")
      (value "360")
      (footprint "eagle-import:0805")
      (libsource (lib "eagle-import") (part "RESISTOR_0805"))
    )
    (comp (ref "R103")
      (value "360")
      (footprint "eagle-import:0805")
      (libsource (lib "eagle-import") (part "RESISTOR_0805"))
    )
    (comp (ref "R104")
      (value "360")
      (footprint "eagle-import:0805")
      (libsource (lib "eagle-import") (part "RESISTOR_0805"))
    )
    (comp (ref "R105")
      (value "360")
      (footprint "eagle-import:0805")
      (libsource (lib "eagle-import") (part "RESISTOR_0805"))
    )
    (comp (ref "R106")
      (value "360")
      (footprint "eagle-import:0805")
      (libsource (lib "eagle-import") (part "RESISTOR_0805"))
    )
    (comp (ref "R107")
      (value "360")
      (footprint "eagle-import:0805")
      (libsource (lib "eagle-import") (part "RESISTOR_0805"))
    )
    (comp (ref "R108")
      (value "360")
      (footprint "eagle-import:0805")
      (libsource (lib "eagle-import") (part "RESISTOR_0805"))
    )
    (comp (ref "R109")
      (value "360")
      (footprint "eagle-import:0805")
      (libsource (lib "eagle-import") (part "RESISTOR_0805"))
    )
    (comp (ref "R110")
      (value "360")
      (footprint "eagle-import:0805")
      (libsource (lib "eagle-import") (part "RESISTOR_0805"))
    )
    (comp (ref "R111")
      (value "360")
      (footprint "eagle-import:0805")
      (libsource (lib "eagle-import") (part "RESISTOR_0805"))
    )
    (comp (ref "R112")
      (value "360")
      (footprint "eagle-import:0805")
      (libsource (lib "eagle-import") (part "RESISTOR_0805"))
    )
    (comp (ref "R113")
      (value "360")
      (footprint "eagle-import:0805")
      (libsource (lib "eagle-import") (part "RESISTOR_0805"))
    )
    (comp (ref "R114")
      (value "360")
      (footprint "eagle-import:0805")
      (libsource (lib "eagle-import") (part "RESISTOR_0805"))
    )
    (comp (ref "R115")
      (value "10K")
      (footprint "eagle-import:0805")
      (libsource (lib "eagle-import") (part "RESISTOR_0805"))
    )
    (comp (ref "R116")
      (value "360")
      (footprint "eagle-import:0805")
      (libsource (lib "eagle-import") (part "RESISTOR_0805"))
    )
    (comp (ref "R117")
      (value "360")
      (footprint "eagle-import:0805")
      (libsource (lib "eagle-import") (part "RESISTOR_0805"))
    )
    (comp (ref "R118")
      (value "360")
      (footprint "eagle-import:0805")
      (libsource (lib "eagle-import") (part "RESISTOR_0805"))
    )
    (comp (ref "R119")
      (value "10K")
      (footprint "eagle-import:0805")
      (libsource (lib "eagle-import") (part "RESISTOR_0805"))
    )
    (comp (ref "R120")
      (value "10K")
      (footprint "eagle-import:0805")
      (libsource (lib "eagle-import") (part "RESISTOR_0805"))
    )
    (comp (ref "R121")
      (value "10K")
      (footprint "eagle-import:0805")
      (libsource (lib "eagle-import") (part "RESISTOR_0805"))
    )
    (comp (ref "R122")
      (value "10K")
      (footprint "eagle-import:0805")
      (libsource (lib "eagle-import") (part "RESISTOR_0805"))
    )
    (comp (ref "R123")
      (value "10K")
      (footprint "eagle-import:0805")
      (libsource (lib "eagle-import") (part "RESISTOR_0805"))
    )
    (comp (ref "R124")
      (value "10K")
      (footprint "eagle-import:0805")
      (libsource (lib "eagle-import") (part "RESISTOR_0805"))
    )
    (comp (ref "R125")
      (value "360")
      (footprint "eagle-import:0805")
      (libsource (lib "eagle-import") (part "RESISTOR_0805"))
    )
    (comp (ref "R126")
      (value "360")
      (footprint "eagle-import:0805")
      (libsource (lib "eagle-import") (part "RESISTOR_0805"))
    )
    (comp (ref "R127")
      (value "360")
      (footprint "eagle-import:0805")
      (libsource (lib "eagle-import") (part "RESISTOR_0805"))
    )
    (comp (ref "R128")
      (value "360")
      (footprint "eagle-import:0805")
      (libsource (lib "eagle-import") (part "RESISTOR_0805"))
    )
    (comp (ref "R129")
      (value "360")
      (footprint "eagle-import:0805")
      (libsource (lib "eagle-import") (part "RESISTOR_0805"))
    )
    (comp (ref "R130")
      (value "360")
      (footprint "eagle-import:0805")
      (libsource (lib "eagle-import") (part "RESISTOR_0805"))
    )
    (comp (ref "R131")
      (value "360")
      (footprint "eagle-import:0805")
      (libsource (lib "eagle-import") (part "RESISTOR_0805"))
    )
    (comp (ref "R132")
      (value "360")
      (footprint "eagle-import:0805")
      (libsource (lib "eagle-import") (part "RESISTOR_0805"))
    )
    (comp (ref "R133")
      (value "10K")
      (footprint "eagle-import:0805")
      (libsource (lib "eagle-import") (part "RESISTOR_0805"))
    )
    (comp (ref "R134")
      (value "25K")
      (footprint "eagle-import:0805")
      (libsource (lib "eagle-import") (part "RESISTOR_0805"))
    )
    (comp (ref "R135")
      (value "10K")
      (footprint "eagle-import:0805")
      (libsource (lib "eagle-import") (part "RESISTOR_0805"))
    )
    (comp (ref "R136")
      (value "0")
      (footprint "eagle-import:0805")
      (libsource (lib "eagle-import") (part "RESISTOR_0805"))
    )
    (comp (ref "R137")
      (value "10K")
      (footprint "eagle-import:0805")
      (libsource (lib "eagle-import") (part "RESISTOR_0805"))
    )
    (comp (ref "R138")
      (value "1K")
      (footprint "eagle-import:0805")
      (libsource (lib "eagle-import") (part "RESISTOR_0805"))
    )
    (comp (ref "R139")
      (value "200")
      (footprint "eagle-import:0805")
      (libsource (lib "eagle-import") (part "RESISTOR_0805"))
    )
    (comp (ref "R140")
      (value "200")
      (footprint "eagle-import:0805")
      (libsource (lib "eagle-import") (part "RESISTOR_0805"))
    )
    (comp (ref "R141")
      (value "200")
      (footprint "eagle-import:0805")
      (libsource (lib "eagle-import") (part "RESISTOR_0805"))
    )
    (comp (ref "R142")
      (value "200")
      (footprint "eagle-import:0805")
      (libsource (lib "eagle-import") (part "RESISTOR_0805"))
    )
    (comp (ref "R143")
      (value "200")
      (footprint "eagle-import:0805")
      (libsource (lib "eagle-import") (part "RESISTOR_0805"))
    )
    (comp (ref "R144")
      (value "200")
      (footprint "eagle-import:0805")
      (libsource (lib "eagle-import") (part "RESISTOR_0805"))
    )
    (comp (ref "R145")
      (value "200")
      (footprint "eagle-import:0805")
      (libsource (lib "eagle-import") (part "RESISTOR_0805"))
    )
    (comp (ref "R146")
      (value "130K")
      (footprint "eagle-import:0805")
      (libsource (lib "eagle-import") (part "RESISTOR_0805"))
    )
    (comp (ref "R147")
      (value "1M")
      (footprint "eagle-import:0805")
      (libsource (lib "eagle-import") (part "RESISTOR_0805"))
    )
    (comp (ref "R148")
      (value "100")
      (footprint "eagle-import:0805")
      (libsource (lib "eagle-import") (part "RESISTOR_0805"))
    )
    (comp (ref "R149")
      (value "100")
      (footprint "eagle-import:0805")
      (libsource (lib "eagle-import") (part "RESISTOR_0805"))
    )
    (comp (ref "R150")
      (value "100")
      (footprint "eagle-import:0805")
      (libsource (lib "eagle-import") (part "RESISTOR_0805"))
    )
    (comp (ref "R151")
      (value "100")
      (footprint "eagle-import:0805")
      (libsource (lib "eagle-import") (part "RESISTOR_0805"))
    )
    (comp (ref "R152")
      (value "100")
      (footprint "eagle-import:0805")
      (libsource (lib "eagle-import") (part "RESISTOR_0805"))
    )
    (comp (ref "R153")
      (value "100")
      (footprint "eagle-import:0805")
      (libsource (lib "eagle-import") (part "RESISTOR_0805"))
    )
    (comp (ref "R154")
      (value "100")
      (footprint "eagle-import:0805")
      (libsource (lib "eagle-import") (part "RESISTOR_0805"))
    )
    (comp (ref "R155")
      (value "100")
      (footprint "eagle-import:0805")
      (libsource (lib "eagle-import") (part "RESISTOR_0805"))
    )
    (comp (ref "R156")
      (value "100")
      (footprint "eagle-import:0805")
      (libsource (lib "eagle-import") (part "RESISTOR_0805"))
    )
    (comp (ref "R157")
      (value "110K")
      (footprint "eagle-import:0805")
      (libsource (lib "eagle-import") (part "RESISTOR_0805"))
    )
    (comp (ref "R158")
      (value "1M")
      (footprint "eagle-import:0805")
      (libsource (lib "eagle-import") (part "RESISTOR_0805"))
    )
    (comp (ref "R159")
      (value "180")
      (footprint "eagle-import:0805")
      (libsource (lib "eagle-import") (part "RESISTOR_0805"))
    )
    (comp (ref "R160")
      (value "680")
      (footprint "eagle-import:0805")
      (libsource (lib "eagle-import") (part "RESISTOR_0805"))
    )
    (comp (ref "R161")
      (value "180")
      (footprint "eagle-import:0805")
      (libsource (lib "eagle-import") (part "RESISTOR_0805"))
    )
    (comp (ref "R162")
      (value "180")
      (footprint "eagle-import:0805")
      (libsource (lib "eagle-import") (part "RESISTOR_0805"))
    )
    (comp (ref "R163")
      (value "CRCW25125K60JNEG")
      (footprint "eagle-import:2512")
      (libsource (lib "eagle-import") (part "RESISTOR_2512"))
    )
    (comp (ref "R164")
      (value "CRCW25125K60JNEG")
      (footprint "eagle-import:2512")
      (libsource (lib "eagle-import") (part "RESISTOR_2512"))
    )
    (comp (ref "R165")
      (value "CRCW25125K60JNEG")
      (footprint "eagle-import:2512")
      (libsource (lib "eagle-import") (part "RESISTOR_2512"))
    )
    (comp (ref "R176")
      (value "10K")
      (footprint "eagle-import:0805")
      (libsource (lib "eagle-import") (part "RESISTOR_0805"))
    )
    (comp (ref "RGB_0")
      (value "RFP12N10L")
      (footprint "eagle-import:TO-220AB")
      (libsource (lib "eagle-import") (part "MOSFET_N-CHANNEL_SINGLE_TO-220AB"))
    )
    (comp (ref "RGB_1")
      (value "RFP12N10L")
      (footprint "eagle-import:TO-220AB")
      (libsource (lib "eagle-import") (part "MOSFET_N-CHANNEL_SINGLE_TO-220AB"))
    )
    (comp (ref "RGB_2")
      (value "RFP12N10L")
      (footprint "eagle-import:TO-220AB")
      (libsource (lib "eagle-import") (part "MOSFET_N-CHANNEL_SINGLE_TO-220AB"))
    )
    (comp (ref "RGB_3")
      (value "RFP12N10L")
      (footprint "eagle-import:TO-220AB")
      (libsource (lib "eagle-import") (part "MOSFET_N-CHANNEL_SINGLE_TO-220AB"))
    )
    (comp (ref "RGB_4")
      (value "RFP12N10L")
      (footprint "eagle-import:TO-220AB")
      (libsource (lib "eagle-import") (part "MOSFET_N-CHANNEL_SINGLE_TO-220AB"))
    )
    (comp (ref "RGB_5")
      (value "RFP12N10L")
      (footprint "eagle-import:TO-220AB")
      (libsource (lib "eagle-import") (part "MOSFET_N-CHANNEL_SINGLE_TO-220AB"))
    )
    (comp (ref "RGB_BOUT_L")
      (value "TEST_POINT_SINGLE_ROUND_100MIL")
      (footprint "eagle-import:100MIL_TP")
      (libsource (lib "eagle-import") (part "TEST_POINT_SINGLE_ROUND_100MIL"))
    )
    (comp (ref "RGB_BOUT_R")
      (value "TEST_POINT_SINGLE_ROUND_100MIL")
      (footprint "eagle-import:100MIL_TP")
      (libsource (lib "eagle-import") (part "TEST_POINT_SINGLE_ROUND_100MIL"))
    )
    (comp (ref "RGB_COM_OUT")
      (value "26-64-4080")
      (footprint "eagle-import:26-64-4080(KEYPIN2)")
      (fields
        (field (name "LABEL01") "GND")
        (field (name "LABEL02") "PROP_AUX1")
        (field (name "LABEL03") "PROP_AUX0")
        (field (name "LABEL04") "RGB_DATA")
        (field (name "LABEL05") "RGB_CLK")
        (field (name "LABEL06") "12V")
        (field (name "LABEL07") "5V")
      )
      (libsource (lib "eagle-import") (part "CON_01X07_26-64-4080(KEYPIN2)"))
    )
    (comp (ref "RGB_GOUT_L")
      (value "TEST_POINT_SINGLE_ROUND_100MIL")
      (footprint "eagle-import:100MIL_TP")
      (libsource (lib "eagle-import") (part "TEST_POINT_SINGLE_ROUND_100MIL"))
    )
    (comp (ref "RGB_GOUT_R")
      (value "TEST_POINT_SINGLE_ROUND_100MIL")
      (footprint "eagle-import:100MIL_TP")
      (libsource (lib "eagle-import") (part "TEST_POINT_SINGLE_ROUND_100MIL"))
    )
    (comp (ref "RGB_ROUT_L")
      (value "TEST_POINT_SINGLE_ROUND_100MIL")
      (footprint "eagle-import:100MIL_TP")
      (libsource (lib "eagle-import") (part "TEST_POINT_SINGLE_ROUND_100MIL"))
    )
    (comp (ref "RGB_ROUT_R")
      (value "TEST_POINT_SINGLE_ROUND_100MIL")
      (footprint "eagle-import:100MIL_TP")
      (libsource (lib "eagle-import") (part "TEST_POINT_SINGLE_ROUND_100MIL"))
    )
    (comp (ref "R_FLIP_OUT")
      (value "TEST_POINT_SINGLE_ROUND_100MIL")
      (footprint "eagle-import:100MIL_TP")
      (libsource (lib "eagle-import") (part "TEST_POINT_SINGLE_ROUND_100MIL"))
    )
    (comp (ref "SD0")
      (value "SD-RSMT-2-MQ")
      (footprint "eagle-import:SD-RSMT-2-MQ")
      (libsource (lib "eagle-import") (part "SD_CARD_SD-RSMT-2-MQ"))
    )
    (comp (ref "SD_CS")
      (value "TEST_POINT_SINGLE_ROUND_100MIL")
      (footprint "eagle-import:100MIL_TP")
      (libsource (lib "eagle-import") (part "TEST_POINT_SINGLE_ROUND_100MIL"))
    )
    (comp (ref "SD_DI")
      (value "TEST_POINT_SINGLE_ROUND_100MIL")
      (footprint "eagle-import:100MIL_TP")
      (libsource (lib "eagle-import") (part "TEST_POINT_SINGLE_ROUND_100MIL"))
    )
    (comp (ref "SD_DO")
      (value "TEST_POINT_SINGLE_ROUND_100MIL")
      (footprint "eagle-import:100MIL_TP")
      (libsource (lib "eagle-import") (part "TEST_POINT_SINGLE_ROUND_100MIL"))
    )
    (comp (ref "SD_SCLK")
      (value "TEST_POINT_SINGLE_ROUND_100MIL")
      (footprint "eagle-import:100MIL_TP")
      (libsource (lib "eagle-import") (part "TEST_POINT_SINGLE_ROUND_100MIL"))
    )
    (comp (ref "SERVO_0")
      (value "640454-3")
      (footprint "eagle-import:640454-3")
      (libsource (lib "eagle-import") (part "CON_01X03_640454-3"))
    )
    (comp (ref "SERVO_0_")
      (value "TEST_POINT_SINGLE_ROUND_100MIL")
      (footprint "eagle-import:100MIL_TP")
      (libsource (lib "eagle-import") (part "TEST_POINT_SINGLE_ROUND_100MIL"))
    )
    (comp (ref "SERVO_1")
      (value "640454-3")
      (footprint "eagle-import:640454-3")
      (libsource (lib "eagle-import") (part "CON_01X03_640454-3"))
    )
    (comp (ref "SERVO_1_")
      (value "TEST_POINT_SINGLE_ROUND_100MIL")
      (footprint "eagle-import:100MIL_TP")
      (libsource (lib "eagle-import") (part "TEST_POINT_SINGLE_ROUND_100MIL"))
    )
    (comp (ref "SERVO_2")
      (value "640454-3")
      (footprint "eagle-import:640454-3")
      (libsource (lib "eagle-import") (part "CON_01X03_640454-3"))
    )
    (comp (ref "SERVO_2_")
      (value "TEST_POINT_SINGLE_ROUND_100MIL")
      (footprint "eagle-import:100MIL_TP")
      (libsource (lib "eagle-import") (part "TEST_POINT_SINGLE_ROUND_100MIL"))
    )
    (comp (ref "SERVO_3")
      (value "640454-3")
      (footprint "eagle-import:640454-3")
      (libsource (lib "eagle-import") (part "CON_01X03_640454-3"))
    )
    (comp (ref "SERVO_3_")
      (value "TEST_POINT_SINGLE_ROUND_100MIL")
      (footprint "eagle-import:100MIL_TP")
      (libsource (lib "eagle-import") (part "TEST_POINT_SINGLE_ROUND_100MIL"))
    )
    (comp (ref "SERVO_4")
      (value "640454-3")
      (footprint "eagle-import:640454-3")
      (libsource (lib "eagle-import") (part "CON_01X03_640454-3"))
    )
    (comp (ref "SERVO_4_")
      (value "TEST_POINT_SINGLE_ROUND_100MIL")
      (footprint "eagle-import:100MIL_TP")
      (libsource (lib "eagle-import") (part "TEST_POINT_SINGLE_ROUND_100MIL"))
    )
    (comp (ref "SHAKER")
      (value "26-64-4020")
      (footprint "eagle-import:26-64-4020")
      (libsource (lib "eagle-import") (part "CON_01X02_26-64-4020"))
    )
    (comp (ref "SOCKET1")
      (value "820-AG11D-ESL-LF")
      (footprint "eagle-import:20PIN_DIP_SOCKET")
      (libsource (lib "eagle-import") (part "DIP_SOCKET_20PIN"))
    )
    (comp (ref "SOCKET2")
      (value "820-AG11D-ESL-LF")
      (footprint "eagle-import:20PIN_DIP_SOCKET")
      (libsource (lib "eagle-import") (part "DIP_SOCKET_20PIN"))
    )
    (comp (ref "SOCKET3")
      (value "808-AG11D-ESL-LF")
      (footprint "eagle-import:8PIN_DIP_SOCKET")
      (libsource (lib "eagle-import") (part "DIP_SOCKET_8PIN"))
    )
    (comp (ref "SOCKET4")
      (value "818-AG11D-ESL-LF")
      (footprint "eagle-import:18PIN_DIP_SOCKET")
      (libsource (lib "eagle-import") (part "DIP_SOCKET_18PIN"))
    )
    (comp (ref "SOCKET5")
      (value "808-AG11D-ESL-LF")
      (footprint "eagle-import:8PIN_DIP_SOCKET")
      (libsource (lib "eagle-import") (part "DIP_SOCKET_8PIN"))
    )
    (comp (ref "SOLENOID_POWER_IN")
      (value "26-64-4040")
      (footprint "eagle-import:26-64-4040(KEYPIN3)")
      (fields (field (name "LABEL01") "GND") (field (name "LABEL02") "GND") (field (name "LABEL03") "50V"))
      (libsource (lib "eagle-import") (part "CON_01X03_26-64-4040_(KEYPIN3)"))
    )
    (comp (ref "SOL_0")
      (value "IRL530PBF")
      (footprint "eagle-import:TO-220AB")
      (libsource (lib "eagle-import") (part "MOSFET_N-CHANNEL_SINGLE_TO-220AB"))
    )
    (comp (ref "SOL_1")
      (value "IRL530PBF")
      (footprint "eagle-import:TO-220AB")
      (libsource (lib "eagle-import") (part "MOSFET_N-CHANNEL_SINGLE_TO-220AB"))
    )
    (comp (ref "SOL_2")
      (value "IRL530PBF")
      (footprint "eagle-import:TO-220AB")
      (libsource (lib "eagle-import") (part "MOSFET_N-CHANNEL_SINGLE_TO-220AB"))
    )
    (comp (ref "SOL_3")
      (value "IRL530PBF")
      (footprint "eagle-import:TO-220AB")
      (libsource (lib "eagle-import") (part "MOSFET_N-CHANNEL_SINGLE_TO-220AB"))
    )
    (comp (ref "SOL_4")
      (value "IRL530PBF")
      (footprint "eagle-import:TO-220AB")
      (libsource (lib "eagle-import") (part "MOSFET_N-CHANNEL_SINGLE_TO-220AB"))
    )
    (comp (ref "SOL_5")
      (value "IRL530PBF")
      (footprint "eagle-import:TO-220AB")
      (libsource (lib "eagle-import") (part "MOSFET_N-CHANNEL_SINGLE_TO-220AB"))
    )
    (comp (ref "SOL_6")
      (value "IRL530PBF")
      (footprint "eagle-import:TO-220AB")
      (libsource (lib "eagle-import") (part "MOSFET_N-CHANNEL_SINGLE_TO-220AB"))
    )
    (comp (ref "SOL_7")
      (value "IRL530PBF")
      (footprint "eagle-import:TO-220AB")
      (libsource (lib "eagle-import") (part "MOSFET_N-CHANNEL_SINGLE_TO-220AB"))
    )
    (comp (ref "SOL_8")
      (value "IRL530PBF")
      (footprint "eagle-import:TO-220AB")
      (libsource (lib "eagle-import") (part "MOSFET_N-CHANNEL_SINGLE_TO-220AB"))
    )
    (comp (ref "SOL_9")
      (value "IRL530PBF")
      (footprint "eagle-import:TO-220AB")
      (libsource (lib "eagle-import") (part "MOSFET_N-CHANNEL_SINGLE_TO-220AB"))
    )
    (comp (ref "SOL_10")
      (value "IRL530PBF")
      (footprint "eagle-import:TO-220AB")
      (libsource (lib "eagle-import") (part "MOSFET_N-CHANNEL_SINGLE_TO-220AB"))
    )
    (comp (ref "SOL_11")
      (value "IRL530PBF")
      (footprint "eagle-import:TO-220AB")
      (libsource (lib "eagle-import") (part "MOSFET_N-CHANNEL_SINGLE_TO-220AB"))
    )
    (comp (ref "SOL_12")
      (value "IRL530PBF")
      (footprint "eagle-import:TO-220AB")
      (libsource (lib "eagle-import") (part "MOSFET_N-CHANNEL_SINGLE_TO-220AB"))
    )
    (comp (ref "SOL_13")
      (value "IRL530PBF")
      (footprint "eagle-import:TO-220AB")
      (libsource (lib "eagle-import") (part "MOSFET_N-CHANNEL_SINGLE_TO-220AB"))
    )
    (comp (ref "SOL_14")
      (value "IRL530PBF")
      (footprint "eagle-import:TO-220AB")
      (libsource (lib "eagle-import") (part "MOSFET_N-CHANNEL_SINGLE_TO-220AB"))
    )
    (comp (ref "SOL_15")
      (value "IRL530PBF")
      (footprint "eagle-import:TO-220AB")
      (libsource (lib "eagle-import") (part "MOSFET_N-CHANNEL_SINGLE_TO-220AB"))
    )
    (comp (ref "SOL_16")
      (value "IRL530PBF")
      (footprint "eagle-import:TO-220AB")
      (libsource (lib "eagle-import") (part "MOSFET_N-CHANNEL_SINGLE_TO-220AB"))
    )
    (comp (ref "SOL_17")
      (value "IRL530PBF")
      (footprint "eagle-import:TO-220AB")
      (libsource (lib "eagle-import") (part "MOSFET_N-CHANNEL_SINGLE_TO-220AB"))
    )
    (comp (ref "SOL_18")
      (value "IRL530PBF")
      (footprint "eagle-import:TO-220AB")
      (libsource (lib "eagle-import") (part "MOSFET_N-CHANNEL_SINGLE_TO-220AB"))
    )
    (comp (ref "SOL_19")
      (value "IRL530PBF")
      (footprint "eagle-import:TO-220AB")
      (libsource (lib "eagle-import") (part "MOSFET_N-CHANNEL_SINGLE_TO-220AB"))
    )
    (comp (ref "SOL_20")
      (value "IRL530PBF")
      (footprint "eagle-import:TO-220AB")
      (libsource (lib "eagle-import") (part "MOSFET_N-CHANNEL_SINGLE_TO-220AB"))
    )
    (comp (ref "SOL_21")
      (value "IRL530PBF")
      (footprint "eagle-import:TO-220AB")
      (libsource (lib "eagle-import") (part "MOSFET_N-CHANNEL_SINGLE_TO-220AB"))
    )
    (comp (ref "SOL_22")
      (value "IRL530PBF")
      (footprint "eagle-import:TO-220AB")
      (libsource (lib "eagle-import") (part "MOSFET_N-CHANNEL_SINGLE_TO-220AB"))
    )
    (comp (ref "SOL_23")
      (value "IRL530PBF")
      (footprint "eagle-import:TO-220AB")
      (libsource (lib "eagle-import") (part "MOSFET_N-CHANNEL_SINGLE_TO-220AB"))
    )
    (comp (ref "SOL_BANK_0")
      (value "26-64-4100")
      (footprint "eagle-import:26-64-4100(KEYPIN6)")
      (fields
        (field (name "LABEL01") "50V")
        (field (name "LABEL02") "SOL_0")
        (field (name "LABEL03") "SOL_1")
        (field (name "LABEL04") "SOL_2")
        (field (name "LABEL05") "SOL_3")
        (field (name "LABEL06") "SOL_4")
        (field (name "LABEL07") "SOL_5")
        (field (name "LABEL08") "SOL_6")
        (field (name "LABEL09") "SOL_7")
      )
      (libsource (lib "eagle-import") (part "CON_01X09_26-64-4100_(KEYPIN6)"))
    )
    (comp (ref "SOL_BANK_1")
      (value "26-64-4100")
      (footprint "eagle-import:26-64-4100(KEYPIN7)")
      (fields
        (field (name "LABEL01") "50V")
        (field (name "LABEL02") "SOL_8")
        (field (name "LABEL03") "SOL_9")
        (field (name "LABEL04") "SOL_10")
        (field (name "LABEL05") "SOL_11")
        (field (name "LABEL06") "SOL_12")
        (field (name "LABEL07") "SOL_13")
        (field (name "LABEL08") "SOL_14")
        (field (name "LABEL09") "SOL_15")
      )
      (libsource (lib "eagle-import") (part "CON_01X09_26-64-4100_(KEYPIN7)"))
    )
    (comp (ref "SOL_BANK_2")
      (value "26-64-4100")
      (footprint "eagle-import:26-64-4100(KEYPIN8)")
      (fields
        (field (name "LABEL01") "50V")
        (field (name "LABEL02") "SOL_16")
        (field (name "LABEL03") "SOL_17")
        (field (name "LABEL04") "SOL_18")
        (field (name "LABEL05") "SOL_19")
        (field (name "LABEL06") "SOL_20")
        (field (name "LABEL07") "SOL_21")
        (field (name "LABEL08") "SOL_22")
        (field (name "LABEL09") "SOL_23")
      )
      (libsource (lib "eagle-import") (part "CON_01X09_26-64-4100_(KEYPIN8)"))
    )
    (comp (ref "SOL_GND")
      (value "TEST_POINT_SINGLE_ROUND_100MIL")
      (footprint "eagle-import:100MIL_TP")
      (libsource (lib "eagle-import") (part "TEST_POINT_SINGLE_ROUND_100MIL"))
    )
    (comp (ref "SOL_PWR_0")
      (value "TEST_POINT_SINGLE_ROUND_100MIL")
      (footprint "eagle-import:100MIL_TP")
      (libsource (lib "eagle-import") (part "TEST_POINT_SINGLE_ROUND_100MIL"))
    )
    (comp (ref "SOL_PWR_1")
      (value "TEST_POINT_SINGLE_ROUND_100MIL")
      (footprint "eagle-import:100MIL_TP")
      (libsource (lib "eagle-import") (part "TEST_POINT_SINGLE_ROUND_100MIL"))
    )
    (comp (ref "SOL_PWR_2")
      (value "TEST_POINT_SINGLE_ROUND_100MIL")
      (footprint "eagle-import:100MIL_TP")
      (libsource (lib "eagle-import") (part "TEST_POINT_SINGLE_ROUND_100MIL"))
    )
    (comp (ref "SOL_PWR_3")
      (value "TEST_POINT_SINGLE_ROUND_100MIL")
      (footprint "eagle-import:100MIL_TP")
      (libsource (lib "eagle-import") (part "TEST_POINT_SINGLE_ROUND_100MIL"))
    )
    (comp (ref "SOL_PWR_4")
      (value "TEST_POINT_SINGLE_ROUND_100MIL")
      (footprint "eagle-import:100MIL_TP")
      (libsource (lib "eagle-import") (part "TEST_POINT_SINGLE_ROUND_100MIL"))
    )
    (comp (ref "SOL_PWR_5")
      (value "TEST_POINT_SINGLE_ROUND_100MIL")
      (footprint "eagle-import:100MIL_TP")
      (libsource (lib "eagle-import") (part "TEST_POINT_SINGLE_ROUND_100MIL"))
    )
    (comp (ref "SOL_PWR_6")
      (value "TEST_POINT_SINGLE_ROUND_100MIL")
      (footprint "eagle-import:100MIL_TP")
      (libsource (lib "eagle-import") (part "TEST_POINT_SINGLE_ROUND_100MIL"))
    )
    (comp (ref "SOL_PWR_7")
      (value "TEST_POINT_SINGLE_ROUND_100MIL")
      (footprint "eagle-import:100MIL_TP")
      (libsource (lib "eagle-import") (part "TEST_POINT_SINGLE_ROUND_100MIL"))
    )
    (comp (ref "SOL_PWR_8")
      (value "TEST_POINT_SINGLE_ROUND_100MIL")
      (footprint "eagle-import:100MIL_TP")
      (libsource (lib "eagle-import") (part "TEST_POINT_SINGLE_ROUND_100MIL"))
    )
    (comp (ref "SOL_PWR_9")
      (value "TEST_POINT_SINGLE_ROUND_100MIL")
      (footprint "eagle-import:100MIL_TP")
      (libsource (lib "eagle-import") (part "TEST_POINT_SINGLE_ROUND_100MIL"))
    )
    (comp (ref "SOL_PWR_10")
      (value "TEST_POINT_SINGLE_ROUND_100MIL")
      (footprint "eagle-import:100MIL_TP")
      (libsource (lib "eagle-import") (part "TEST_POINT_SINGLE_ROUND_100MIL"))
    )
    (comp (ref "SOL_PWR_11")
      (value "TEST_POINT_SINGLE_ROUND_100MIL")
      (footprint "eagle-import:100MIL_TP")
      (libsource (lib "eagle-import") (part "TEST_POINT_SINGLE_ROUND_100MIL"))
    )
    (comp (ref "SOL_PWR_12")
      (value "TEST_POINT_SINGLE_ROUND_100MIL")
      (footprint "eagle-import:100MIL_TP")
      (libsource (lib "eagle-import") (part "TEST_POINT_SINGLE_ROUND_100MIL"))
    )
    (comp (ref "SOL_PWR_13")
      (value "TEST_POINT_SINGLE_ROUND_100MIL")
      (footprint "eagle-import:100MIL_TP")
      (libsource (lib "eagle-import") (part "TEST_POINT_SINGLE_ROUND_100MIL"))
    )
    (comp (ref "SOL_PWR_14")
      (value "TEST_POINT_SINGLE_ROUND_100MIL")
      (footprint "eagle-import:100MIL_TP")
      (libsource (lib "eagle-import") (part "TEST_POINT_SINGLE_ROUND_100MIL"))
    )
    (comp (ref "SOL_PWR_15")
      (value "TEST_POINT_SINGLE_ROUND_100MIL")
      (footprint "eagle-import:100MIL_TP")
      (libsource (lib "eagle-import") (part "TEST_POINT_SINGLE_ROUND_100MIL"))
    )
    (comp (ref "SOL_PWR_16")
      (value "TEST_POINT_SINGLE_ROUND_100MIL")
      (footprint "eagle-import:100MIL_TP")
      (libsource (lib "eagle-import") (part "TEST_POINT_SINGLE_ROUND_100MIL"))
    )
    (comp (ref "SOL_PWR_17")
      (value "TEST_POINT_SINGLE_ROUND_100MIL")
      (footprint "eagle-import:100MIL_TP")
      (libsource (lib "eagle-import") (part "TEST_POINT_SINGLE_ROUND_100MIL"))
    )
    (comp (ref "SOL_PWR_18")
      (value "TEST_POINT_SINGLE_ROUND_100MIL")
      (footprint "eagle-import:100MIL_TP")
      (libsource (lib "eagle-import") (part "TEST_POINT_SINGLE_ROUND_100MIL"))
    )
    (comp (ref "SOL_PWR_19")
      (value "TEST_POINT_SINGLE_ROUND_100MIL")
      (footprint "eagle-import:100MIL_TP")
      (libsource (lib "eagle-import") (part "TEST_POINT_SINGLE_ROUND_100MIL"))
    )
    (comp (ref "SOL_PWR_20")
      (value "TEST_POINT_SINGLE_ROUND_100MIL")
      (footprint "eagle-import:100MIL_TP")
      (libsource (lib "eagle-import") (part "TEST_POINT_SINGLE_ROUND_100MIL"))
    )
    (comp (ref "SOL_PWR_21")
      (value "TEST_POINT_SINGLE_ROUND_100MIL")
      (footprint "eagle-import:100MIL_TP")
      (libsource (lib "eagle-import") (part "TEST_POINT_SINGLE_ROUND_100MIL"))
    )
    (comp (ref "SOL_PWR_22")
      (value "TEST_POINT_SINGLE_ROUND_100MIL")
      (footprint "eagle-import:100MIL_TP")
      (libsource (lib "eagle-import") (part "TEST_POINT_SINGLE_ROUND_100MIL"))
    )
    (comp (ref "SOL_PWR_23")
      (value "TEST_POINT_SINGLE_ROUND_100MIL")
      (footprint "eagle-import:100MIL_TP")
      (libsource (lib "eagle-import") (part "TEST_POINT_SINGLE_ROUND_100MIL"))
    )
    (comp (ref "ST_BU_OUT")
      (value "TEST_POINT_SINGLE_ROUND_100MIL")
      (footprint "eagle-import:100MIL_TP")
      (libsource (lib "eagle-import") (part "TEST_POINT_SINGLE_ROUND_100MIL"))
    )
    (comp (ref "ST_LI")
      (value "NDP6020P")
      (footprint "eagle-import:TO-220AB")
      (libsource (lib "eagle-import") (part "BJT_PNP_SINGLE_TO-220"))
    )
    (comp (ref "ST_LI_")
      (value "TEST_POINT_SINGLE_ROUND_100MIL")
      (footprint "eagle-import:100MIL_TP")
      (libsource (lib "eagle-import") (part "TEST_POINT_SINGLE_ROUND_100MIL"))
    )
    (comp (ref "SW_COL")
      (value "26-64-4100")
      (footprint "eagle-import:26-64-4100(KEYPIN5)")
      (fields
        (field (name "LABEL02") "SW_C_7")
        (field (name "LABEL03") "SW_C_6")
        (field (name "LABEL04") "SW_C_5")
        (field (name "LABEL05") "SW_C_4")
        (field (name "LABEL06") "SW_C_3")
        (field (name "LABEL07") "SW_C_2")
        (field (name "LABEL08") "SW_C_1")
        (field (name "LABEL09") "SW_C_0")
      )
      (libsource (lib "eagle-import") (part "CON_01X09_26-64-4100_(KEYPIN5)"))
    )
    (comp (ref "SW_C_0")
      (value "TEST_POINT_SINGLE_ROUND_100MIL")
      (footprint "eagle-import:100MIL_TP")
      (libsource (lib "eagle-import") (part "TEST_POINT_SINGLE_ROUND_100MIL"))
    )
    (comp (ref "SW_C_1")
      (value "TEST_POINT_SINGLE_ROUND_100MIL")
      (footprint "eagle-import:100MIL_TP")
      (libsource (lib "eagle-import") (part "TEST_POINT_SINGLE_ROUND_100MIL"))
    )
    (comp (ref "SW_C_2")
      (value "TEST_POINT_SINGLE_ROUND_100MIL")
      (footprint "eagle-import:100MIL_TP")
      (libsource (lib "eagle-import") (part "TEST_POINT_SINGLE_ROUND_100MIL"))
    )
    (comp (ref "SW_C_3")
      (value "TEST_POINT_SINGLE_ROUND_100MIL")
      (footprint "eagle-import:100MIL_TP")
      (libsource (lib "eagle-import") (part "TEST_POINT_SINGLE_ROUND_100MIL"))
    )
    (comp (ref "SW_C_4")
      (value "TEST_POINT_SINGLE_ROUND_100MIL")
      (footprint "eagle-import:100MIL_TP")
      (libsource (lib "eagle-import") (part "TEST_POINT_SINGLE_ROUND_100MIL"))
    )
    (comp (ref "SW_C_5")
      (value "TEST_POINT_SINGLE_ROUND_100MIL")
      (footprint "eagle-import:100MIL_TP")
      (libsource (lib "eagle-import") (part "TEST_POINT_SINGLE_ROUND_100MIL"))
    )
    (comp (ref "SW_C_6")
      (value "TEST_POINT_SINGLE_ROUND_100MIL")
      (footprint "eagle-import:100MIL_TP")
      (libsource (lib "eagle-import") (part "TEST_POINT_SINGLE_ROUND_100MIL"))
    )
    (comp (ref "SW_C_7")
      (value "TEST_POINT_SINGLE_ROUND_100MIL")
      (footprint "eagle-import:100MIL_TP")
      (libsource (lib "eagle-import") (part "TEST_POINT_SINGLE_ROUND_100MIL"))
    )
    (comp (ref "SW_ROW")
      (value "26-64-4100")
      (footprint "eagle-import:26-64-4100(KEYPIN4)")
      (fields
        (field (name "LABEL02") "SW_R_7")
        (field (name "LABEL03") "SW_R_6")
        (field (name "LABEL04") "SW_R_5")
        (field (name "LABEL05") "SW_R_4")
        (field (name "LABEL06") "SW_R_3")
        (field (name "LABEL07") "SW_R_2")
        (field (name "LABEL08") "SW_R_1")
        (field (name "LABEL09") "SW_R_0")
      )
      (libsource (lib "eagle-import") (part "CON_01X09_26-64-4100_(KEYPIN4)"))
    )
    (comp (ref "SW_R_0")
      (value "TEST_POINT_SINGLE_ROUND_100MIL")
      (footprint "eagle-import:100MIL_TP")
      (libsource (lib "eagle-import") (part "TEST_POINT_SINGLE_ROUND_100MIL"))
    )
    (comp (ref "SW_R_1")
      (value "TEST_POINT_SINGLE_ROUND_100MIL")
      (footprint "eagle-import:100MIL_TP")
      (libsource (lib "eagle-import") (part "TEST_POINT_SINGLE_ROUND_100MIL"))
    )
    (comp (ref "SW_R_2")
      (value "TEST_POINT_SINGLE_ROUND_100MIL")
      (footprint "eagle-import:100MIL_TP")
      (libsource (lib "eagle-import") (part "TEST_POINT_SINGLE_ROUND_100MIL"))
    )
    (comp (ref "SW_R_3")
      (value "TEST_POINT_SINGLE_ROUND_100MIL")
      (footprint "eagle-import:100MIL_TP")
      (libsource (lib "eagle-import") (part "TEST_POINT_SINGLE_ROUND_100MIL"))
    )
    (comp (ref "SW_R_4")
      (value "TEST_POINT_SINGLE_ROUND_100MIL")
      (footprint "eagle-import:100MIL_TP")
      (libsource (lib "eagle-import") (part "TEST_POINT_SINGLE_ROUND_100MIL"))
    )
    (comp (ref "SW_R_5")
      (value "TEST_POINT_SINGLE_ROUND_100MIL")
      (footprint "eagle-import:100MIL_TP")
      (libsource (lib "eagle-import") (part "TEST_POINT_SINGLE_ROUND_100MIL"))
    )
    (comp (ref "SW_R_6")
      (value "TEST_POINT_SINGLE_ROUND_100MIL")
      (footprint "eagle-import:100MIL_TP")
      (libsource (lib "eagle-import") (part "TEST_POINT_SINGLE_ROUND_100MIL"))
    )
    (comp (ref "SW_R_7")
      (value "TEST_POINT_SINGLE_ROUND_100MIL")
      (footprint "eagle-import:100MIL_TP")
      (libsource (lib "eagle-import") (part "TEST_POINT_SINGLE_ROUND_100MIL"))
    )
    (comp (ref "SYM1")
      (value "HIGH_VOLTAGE_500MIL")
      (footprint "eagle-import:HIGH_VOLTAGE_500MIL")
      (libsource (lib "eagle-import") (part "PCB_SYMBOL_HIGH_VOLTAGE_500MIL"))
    )
    (comp (ref "S_L")
      (value "TEST_POINT_SINGLE_ROUND_100MIL")
      (footprint "eagle-import:100MIL_TP")
      (libsource (lib "eagle-import") (part "TEST_POINT_SINGLE_ROUND_100MIL"))
    )
    (comp (ref "S_R")
      (value "TEST_POINT_SINGLE_ROUND_100MIL")
      (footprint "eagle-import:100MIL_TP")
      (libsource (lib "eagle-import") (part "TEST_POINT_SINGLE_ROUND_100MIL"))
    )
    (comp (ref "TILT_OUT")
      (value "TEST_POINT_SINGLE_ROUND_100MIL")
      (footprint "eagle-import:100MIL_TP")
      (libsource (lib "eagle-import") (part "TEST_POINT_SINGLE_ROUND_100MIL"))
    )
    (comp (ref "U$1")
      (value "LHE_LOGOLHE_LOGO")
      (footprint "eagle-import:LHE_LOGO")
      (libsource (lib "eagle-import") (part "LHE_LOGOLHE_LOGO"))
    )
    (comp (ref "U$2")
      (value "MF_LOGOLOGO_TEXT")
      (footprint "eagle-import:MF_LOGO_TEXT")
      (libsource (lib "eagle-import") (part "MF_LOGOLOGO_TEXT"))
    )
    (comp (ref "U1")
      (value "P8X32A-Q44")
      (footprint "eagle-import:P8X32A_LQFP-44")
      (libsource (lib "eagle-import") (part "P8X32A-Q44"))
    )
    (comp (ref "U2")
      (value "DS1340Z-33+")
      (footprint "eagle-import:DS1340Z_SOIC-8")
      (libsource (lib "eagle-import") (part "DS1340Z-33+"))
    )
    (comp (ref "U3")
      (value "CD74HC595M96")
      (footprint "eagle-import:CD74HC595_SOIC-16")
      (libsource (lib "eagle-import") (part "CD74HC595M96"))
    )
    (comp (ref "U4")
      (value "CAT24M01LI-G")
      (footprint "eagle-import:DIP-8")
      (libsource (lib "eagle-import") (part "EEPROM_I2CDIP-8"))
    )
    (comp (ref "U5")
      (value "CD74HC595M96")
      (footprint "eagle-import:CD74HC595_SOIC-16")
      (libsource (lib "eagle-import") (part "CD74HC595M96"))
    )
    (comp (ref "U6")
      (value "TPS259251")
      (footprint "eagle-import:TPS2592(50_51_60_61)_VSON-10")
      (libsource (lib "eagle-import") (part "TPS2592(50/51/60/61)_VSON-10"))
    )
    (comp (ref "U7")
      (value "TPS259261")
      (footprint "eagle-import:TPS2592(50_51_60_61)_VSON-10")
      (libsource (lib "eagle-import") (part "TPS2592(50/51/60/61)_VSON-10"))
    )
    (comp (ref "U8")
      (value "MF-DSC-SOT233-MMBT3904")
      (footprint "eagle-import:SOT-23-3")
      (libsource (lib "eagle-import") (part "NPN_BJT_SOT-23-3"))
    )
    (comp (ref "U10")
      (value "74HCT2G04GV,125")
      (footprint "eagle-import:74HCT2G04_TTSOP-6")
      (libsource (lib "eagle-import") (part "74HCT2G04GV,125"))
    )
    (comp (ref "U11")
      (value "74HC165D-Q100,118")
      (footprint "eagle-import:CD74HC165_SOIC-16")
      (libsource (lib "eagle-import") (part "CD74HC165M96"))
    )
    (comp (ref "U12")
      (value "74HC165D-Q100,118")
      (footprint "eagle-import:CD74HC165_SOIC-16")
      (libsource (lib "eagle-import") (part "CD74HC165M96"))
    )
    (comp (ref "U13")
      (value "CAT24M01LI-G")
      (footprint "eagle-import:DIP-8")
      (libsource (lib "eagle-import") (part "EEPROM_I2CDIP-8"))
    )
    (comp (ref "U14")
      (value "MC74HC08ADR2G")
      (footprint "eagle-import:MC74HC08_SOIC-14")
      (libsource (lib "eagle-import") (part "MC74HC08AD"))
    )
    (comp (ref "U15")
      (value "MC74HC08ADR2G")
      (footprint "eagle-import:MC74HC08_SOIC-14")
      (libsource (lib "eagle-import") (part "MC74HC08AD"))
    )
    (comp (ref "U16")
      (value "MC74HC08ADR2G")
      (footprint "eagle-import:MC74HC08_SOIC-14")
      (libsource (lib "eagle-import") (part "MC74HC08AD"))
    )
    (comp (ref "U17")
      (value "MC74HC08ADR2G")
      (footprint "eagle-import:MC74HC08_SOIC-14")
      (libsource (lib "eagle-import") (part "MC74HC08AD"))
    )
    (comp (ref "U18")
      (value "MC74HC08ADR2G")
      (footprint "eagle-import:MC74HC08_SOIC-14")
      (libsource (lib "eagle-import") (part "MC74HC08AD"))
    )
    (comp (ref "U19")
      (value "MC74HC08ADR2G")
      (footprint "eagle-import:MC74HC08_SOIC-14")
      (libsource (lib "eagle-import") (part "MC74HC08AD"))
    )
    (comp (ref "U20")
      (value "TIP107")
      (footprint "eagle-import:TO-220AB")
      (libsource (lib "eagle-import") (part "BJT_PNP_SINGLE_TO-220"))
    )
    (comp (ref "U21")
      (value "TIP107")
      (footprint "eagle-import:TO-220AB")
      (libsource (lib "eagle-import") (part "BJT_PNP_SINGLE_TO-220"))
    )
    (comp (ref "U22")
      (value "TIP107")
      (footprint "eagle-import:TO-220AB")
      (libsource (lib "eagle-import") (part "BJT_PNP_SINGLE_TO-220"))
    )
    (comp (ref "U23")
      (value "TIP107")
      (footprint "eagle-import:TO-220AB")
      (libsource (lib "eagle-import") (part "BJT_PNP_SINGLE_TO-220"))
    )
    (comp (ref "U24")
      (value "TIP107")
      (footprint "eagle-import:TO-220AB")
      (libsource (lib "eagle-import") (part "BJT_PNP_SINGLE_TO-220"))
    )
    (comp (ref "U25")
      (value "TIP107")
      (footprint "eagle-import:TO-220AB")
      (libsource (lib "eagle-import") (part "BJT_PNP_SINGLE_TO-220"))
    )
    (comp (ref "U26")
      (value "TIP107")
      (footprint "eagle-import:TO-220AB")
      (libsource (lib "eagle-import") (part "BJT_PNP_SINGLE_TO-220"))
    )
    (comp (ref "U27")
      (value "TIP107")
      (footprint "eagle-import:TO-220AB")
      (libsource (lib "eagle-import") (part "BJT_PNP_SINGLE_TO-220"))
    )
    (comp (ref "U28")
      (value "TIP102")
      (footprint "eagle-import:TO-220AB")
      (libsource (lib "eagle-import") (part "BJT_NPN_SINGLE_TO-220"))
    )
    (comp (ref "U29")
      (value "TIP102")
      (footprint "eagle-import:TO-220AB")
      (libsource (lib "eagle-import") (part "BJT_NPN_SINGLE_TO-220"))
    )
    (comp (ref "U30")
      (value "TIP102")
      (footprint "eagle-import:TO-220AB")
      (libsource (lib "eagle-import") (part "BJT_NPN_SINGLE_TO-220"))
    )
    (comp (ref "U31")
      (value "TIP102")
      (footprint "eagle-import:TO-220AB")
      (libsource (lib "eagle-import") (part "BJT_NPN_SINGLE_TO-220"))
    )
    (comp (ref "U32")
      (value "TIP102")
      (footprint "eagle-import:TO-220AB")
      (libsource (lib "eagle-import") (part "BJT_NPN_SINGLE_TO-220"))
    )
    (comp (ref "U33")
      (value "TIP102")
      (footprint "eagle-import:TO-220AB")
      (libsource (lib "eagle-import") (part "BJT_NPN_SINGLE_TO-220"))
    )
    (comp (ref "U34")
      (value "TIP102")
      (footprint "eagle-import:TO-220AB")
      (libsource (lib "eagle-import") (part "BJT_NPN_SINGLE_TO-220"))
    )
    (comp (ref "U35")
      (value "TIP102")
      (footprint "eagle-import:TO-220AB")
      (libsource (lib "eagle-import") (part "BJT_NPN_SINGLE_TO-220"))
    )
    (comp (ref "U36")
      (value "WS2801")
      (footprint "eagle-import:WS2801_SOP-14")
      (libsource (lib "eagle-import") (part "WS2801SO"))
    )
    (comp (ref "U38")
      (value "WS2801")
      (footprint "eagle-import:WS2801_SOP-14")
      (libsource (lib "eagle-import") (part "WS2801SO"))
    )
    (comp (ref "U39")
      (value "NCP1117DT33G")
      (footprint "eagle-import:NCP1117DT_DPAK-3")
      (libsource (lib "eagle-import") (part "LINEAR_VOTLAGE_REGULATORS_NCP1117DT"))
    )
    (comp (ref "U52")
      (value "CD74HC123M96")
      (footprint "eagle-import:CD74HC123_SOIC-16")
      (libsource (lib "eagle-import") (part "CD74HC123M96"))
    )
    (comp (ref "USB_PROG")
      (value "N/A")
      (footprint "eagle-import:2.54MM_01X04_PIN_HEADER")
      (fields
        (field (name "LABEL01") "VUSB")
        (field (name "LABEL02") "USB D-")
        (field (name "LABEL03") "USB D+")
        (field (name "LABEL04") "GND")
      )
      (libsource (lib "eagle-import") (part "CON_01X04_2.54MM_PIN_HEADER"))
    )
    (comp (ref "USER_0_OUT")
      (value "TEST_POINT_SINGLE_ROUND_100MIL")
      (footprint "eagle-import:100MIL_TP")
      (libsource (lib "eagle-import") (part "TEST_POINT_SINGLE_ROUND_100MIL"))
    )
    (comp (ref "WD")
      (value "LG R971-KN-1")
      (footprint "eagle-import:LED_0805")
      (libsource (lib "eagle-import") (part "PP_LED_LED_SINGLE_0805"))
    )
    (comp (ref "X1")
      (value "FQ7050B-8.000")
      (footprint "eagle-import:FQ7050B")
      (libsource (lib "eagle-import") (part "XTAL-FQ7050B"))
    )
    (comp (ref "X2")
      (value "9C-6.500MAAJ-T")
      (footprint "eagle-import:HC-49_US_SM")
      (libsource (lib "eagle-import") (part "CRYSTAL_HC-49"))
    )
    (comp (ref "X3")
      (value "ABS25-32.768KHz-1-T")
      (footprint "eagle-import:8MM_X_3.8MM")
      (libsource (lib "eagle-import") (part "CRYSTAL_8MM_X_3.8MM"))
    )
  )
  (nets
    (net (code "1") (name "/3.3V") (class "Default")
      (node (ref "3.3V") (pin "P$1") (pinfunction "P$1_P$1") (pintype "bidirectional"))
      (node (ref "AUX_PWR") (pin "4") (pinfunction "4_4") (pintype "passive"))
      (node (ref "C11") (pin "1") (pinfunction "1_1") (pintype "passive"))
      (node (ref "C12") (pin "2") (pinfunction "2_2") (pintype "passive"))
      (node (ref "C15") (pin "P$1") (pinfunction "P$1_P$1") (pintype "passive"))
      (node (ref "C18") (pin "P$1") (pinfunction "P$1_P$1") (pintype "passive"))
      (node (ref "C2") (pin "1") (pinfunction "1_1") (pintype "passive"))
      (node (ref "C20") (pin "2") (pinfunction "2_2") (pintype "passive"))
      (node (ref "C21") (pin "2") (pinfunction "2_2") (pintype "passive"))
      (node (ref "C22") (pin "2") (pinfunction "2_2") (pintype "passive"))
      (node (ref "C23") (pin "2") (pinfunction "2_2") (pintype "passive"))
      (node (ref "C24") (pin "2") (pinfunction "2_2") (pintype "passive"))
      (node (ref "C28") (pin "2") (pinfunction "2_2") (pintype "passive"))
      (node (ref "C3") (pin "1") (pinfunction "1_1") (pintype "passive"))
      (node (ref "C31") (pin "2") (pinfunction "2_2") (pintype "passive"))
      (node (ref "C32") (pin "2") (pinfunction "2_2") (pintype "passive"))
      (node (ref "C33") (pin "2") (pinfunction "2_2") (pintype "passive"))
      (node (ref "C34") (pin "POS") (pinfunction "POS_POS") (pintype "bidirectional"))
      (node (ref "C35") (pin "1") (pinfunction "1_1") (pintype "passive"))
      (node (ref "C36") (pin "1") (pinfunction "1_1") (pintype "passive"))
      (node (ref "C37") (pin "1") (pinfunction "1_1") (pintype "passive"))
      (node (ref "C4") (pin "1") (pinfunction "1_1") (pintype "passive"))
      (node (ref "C46") (pin "2") (pinfunction "2_2") (pintype "passive"))
      (node (ref "C47") (pin "2") (pinfunction "2_2") (pintype "passive"))
      (node (ref "C49") (pin "POS") (pinfunction "POS_POS") (pintype "bidirectional"))
      (node (ref "C5") (pin "1") (pinfunction "1_1") (pintype "passive"))
      (node (ref "C54") (pin "2") (pinfunction "2_2") (pintype "passive"))
      (node (ref "C55") (pin "2") (pinfunction "2_2") (pintype "passive"))
      (node (ref "C56") (pin "1") (pinfunction "1_1") (pintype "passive"))
      (node (ref "C57") (pin "1") (pinfunction "1_1") (pintype "passive"))
      (node (ref "C6") (pin "1") (pinfunction "1_1") (pintype "passive"))
      (node (ref "C7") (pin "1") (pinfunction "1_1") (pintype "passive"))
      (node (ref "D1") (pin "2") (pinfunction "AN_2") (pintype "bidirectional"))
      (node (ref "IC2") (pin "16") (pinfunction "VDD_16") (pintype "bidirectional"))
      (node (ref "IC2") (pin "2") (pinfunction "VDD_2") (pintype "bidirectional"))
      (node (ref "IC2") (pin "37") (pinfunction "VDD_37") (pintype "bidirectional"))
      (node (ref "IC2") (pin "46") (pinfunction "VDD_46") (pintype "bidirectional"))
      (node (ref "IC2") (pin "55") (pinfunction "VUSB_55") (pintype "bidirectional"))
      (node (ref "IC2") (pin "62") (pinfunction "VDD_62") (pintype "bidirectional"))
      (node (ref "IC2") (pin "86") (pinfunction "VDD_86") (pintype "bidirectional"))
      (node (ref "IC3") (pin "20") (pinfunction "VCC_20") (pintype "power_in"))
      (node (ref "IC4") (pin "20") (pinfunction "VCC_20") (pintype "power_in"))
      (node (ref "OPTO_1") (pin "2") (pinfunction "2_2") (pintype "passive"))
      (node (ref "OPTO_2") (pin "2") (pinfunction "2_2") (pintype "passive"))
      (node (ref "OPTO_3") (pin "2") (pinfunction "2_2") (pintype "passive"))
      (node (ref "OPTO_4") (pin "2") (pinfunction "2_2") (pintype "passive"))
      (node (ref "OPTO_5") (pin "2") (pinfunction "2_2") (pintype "passive"))
      (node (ref "OPTO_6") (pin "2") (pinfunction "2_2") (pintype "passive"))
      (node (ref "OPTO_7") (pin "2") (pinfunction "2_2") (pintype "passive"))
      (node (ref "PHABULOUS") (pin "2") (pinfunction "2_2") (pintype "bidirectional"))
      (node (ref "PICKIT3") (pin "2") (pinfunction "2_2") (pintype "passive"))
      (node (ref "PICKIT3_TC") (pin "P$2") (pinfunction "PIN2_P$2") (pintype "bidirectional"))
      (node (ref "PSU_PWR") (pin "ANODE") (pinfunction "ANODE_ANODE") (pintype "bidirectional"))
      (node (ref "R1") (pin "2") (pinfunction "2_2") (pintype "passive"))
      (node (ref "R119") (pin "2") (pinfunction "2_2") (pintype "passive"))
      (node (ref "R120") (pin "2") (pinfunction "2_2") (pintype "passive"))
      (node (ref "R121") (pin "2") (pinfunction "2_2") (pintype "passive"))
      (node (ref "R122") (pin "2") (pinfunction "2_2") (pintype "passive"))
      (node (ref "R123") (pin "2") (pinfunction "2_2") (pintype "passive"))
      (node (ref "R124") (pin "2") (pinfunction "2_2") (pintype "passive"))
      (node (ref "R137") (pin "2") (pinfunction "2_2") (pintype "passive"))
      (node (ref "R16") (pin "2") (pinfunction "2_2") (pintype "passive"))
      (node (ref "R17") (pin "2") (pinfunction "2_2") (pintype "passive"))
      (node (ref "R176") (pin "2") (pinfunction "2_2") (pintype "passive"))
      (node (ref "R18") (pin "1") (pinfunction "1_1") (pintype "passive"))
      (node (ref "R19") (pin "1") (pinfunction "1_1") (pintype "passive"))
      (node (ref "R20") (pin "1") (pinfunction "1_1") (pintype "passive"))
      (node (ref "R21") (pin "1") (pinfunction "1_1") (pintype "passive"))
      (node (ref "R22") (pin "1") (pinfunction "1_1") (pintype "passive"))
      (node (ref "R23") (pin "1") (pinfunction "1_1") (pintype "passive"))
      (node (ref "R24") (pin "2") (pinfunction "2_2") (pintype "passive"))
      (node (ref "R25") (pin "2") (pinfunction "2_2") (pintype "passive"))
      (node (ref "R3") (pin "1") (pinfunction "1_1") (pintype "passive"))
      (node (ref "R35") (pin "2") (pinfunction "2_2") (pintype "passive"))
      (node (ref "R36") (pin "2") (pinfunction "2_2") (pintype "passive"))
      (node (ref "R37") (pin "2") (pinfunction "2_2") (pintype "passive"))
      (node (ref "R38") (pin "2") (pinfunction "2_2") (pintype "passive"))
      (node (ref "R39") (pin "2") (pinfunction "2_2") (pintype "passive"))
      (node (ref "R4") (pin "2") (pinfunction "2_2") (pintype "passive"))
      (node (ref "R40") (pin "2") (pinfunction "2_2") (pintype "passive"))
      (node (ref "R41") (pin "2") (pinfunction "2_2") (pintype "passive"))
      (node (ref "R42") (pin "2") (pinfunction "2_2") (pintype "passive"))
      (node (ref "R43") (pin "2") (pinfunction "2_2") (pintype "passive"))
      (node (ref "R44") (pin "2") (pinfunction "2_2") (pintype "passive"))
      (node (ref "R45") (pin "2") (pinfunction "2_2") (pintype "passive"))
      (node (ref "R46") (pin "2") (pinfunction "2_2") (pintype "passive"))
      (node (ref "R47") (pin "2") (pinfunction "2_2") (pintype "passive"))
      (node (ref "R48") (pin "2") (pinfunction "2_2") (pintype "passive"))
      (node (ref "R49") (pin "2") (pinfunction "2_2") (pintype "passive"))
      (node (ref "R50") (pin "2") (pinfunction "2_2") (pintype "passive"))
      (node (ref "R75") (pin "1") (pinfunction "1_1") (pintype "passive"))
      (node (ref "R76") (pin "1") (pinfunction "1_1") (pintype "passive"))
      (node (ref "R77") (pin "1") (pinfunction "1_1") (pintype "passive"))
      (node (ref "R78") (pin "1") (pinfunction "1_1") (pintype "passive"))
      (node (ref "R79") (pin "2") (pinfunction "2_2") (pintype "passive"))
      (node (ref "R80") (pin "2") (pinfunction "2_2") (pintype "passive"))
      (node (ref "R81") (pin "2") (pinfunction "2_2") (pintype "passive"))
      (node (ref "R82") (pin "2") (pinfunction "2_2") (pintype "passive"))
      (node (ref "SD0") (pin "4") (pinfunction "3.3V_4") (pintype "bidirectional"))
      (node (ref "U1") (pin "18") (pinfunction "VDD_18") (pintype "bidirectional"))
      (node (ref "U1") (pin "30") (pinfunction "VDD_30") (pintype "bidirectional"))
      (node (ref "U1") (pin "40") (pinfunction "VDD_40") (pintype "bidirectional"))
      (node (ref "U1") (pin "8") (pinfunction "VDD_8") (pintype "bidirectional"))
      (node (ref "U11") (pin "16") (pinfunction "VCC_16") (pintype "bidirectional"))
      (node (ref "U12") (pin "16") (pinfunction "VCC_16") (pintype "bidirectional"))
      (node (ref "U13") (pin "8") (pinfunction "VCC_8") (pintype "bidirectional"))
      (node (ref "U2") (pin "8") (pinfunction "VCC_8") (pintype "bidirectional"))
      (node (ref "U36") (pin "14") (pinfunction "VDD_14") (pintype "bidirectional"))
      (node (ref "U38") (pin "14") (pinfunction "VDD_14") (pintype "bidirectional"))
      (node (ref "U39") (pin "TAB") (pinfunction "OUT_TAB") (pintype "bidirectional"))
      (node (ref "U4") (pin "8") (pinfunction "VCC_8") (pintype "bidirectional"))
    )
    (net (code "2") (name "/5V") (class "Default")
      (node (ref "AUX_PWR") (pin "3") (pinfunction "3_3") (pintype "passive"))
      (node (ref "C16") (pin "P$1") (pinfunction "P$1_P$1") (pintype "passive"))
      (node (ref "C19") (pin "P$1") (pinfunction "P$1_P$1") (pintype "passive"))
      (node (ref "C25") (pin "2") (pinfunction "2_2") (pintype "passive"))
      (node (ref "C26") (pin "2") (pinfunction "2_2") (pintype "passive"))
      (node (ref "C30") (pin "1") (pinfunction "1_1") (pintype "passive"))
      (node (ref "C38") (pin "1") (pinfunction "1_1") (pintype "passive"))
      (node (ref "C39") (pin "1") (pinfunction "1_1") (pintype "passive"))
      (node (ref "C40") (pin "1") (pinfunction "1_1") (pintype "passive"))
      (node (ref "C41") (pin "1") (pinfunction "1_1") (pintype "passive"))
      (node (ref "C42") (pin "1") (pinfunction "1_1") (pintype "passive"))
      (node (ref "C48") (pin "1") (pinfunction "1_1") (pintype "passive"))
      (node (ref "C50") (pin "POS") (pinfunction "POS_POS") (pintype "bidirectional"))
      (node (ref "C51") (pin "1") (pinfunction "1_1") (pintype "passive"))
      (node (ref "C52") (pin "1") (pinfunction "1_1") (pintype "passive"))
      (node (ref "C53") (pin "1") (pinfunction "1_1") (pintype "passive"))
      (node (ref "C62") (pin "1") (pinfunction "1_1") (pintype "passive"))
      (node (ref "C63") (pin "1") (pinfunction "1_1") (pintype "passive"))
      (node (ref "C64") (pin "1") (pinfunction "1_1") (pintype "passive"))
      (node (ref "C65") (pin "1") (pinfunction "1_1") (pintype "passive"))
      (node (ref "CABINET_I/O") (pin "P$2") (pinfunction "2_P$2") (pintype "bidirectional"))
      (node (ref "D2") (pin "1") (pinfunction "CATHODE_1") (pintype "bidirectional"))
      (node (ref "DMD_PWR") (pin "3") (pinfunction "PIN2_3") (pintype "bidirectional"))
      (node (ref "F4") (pin "P$1") (pinfunction "P$1_P$1") (pintype "bidirectional"))
      (node (ref "F5") (pin "P$1") (pinfunction "P$1_P$1") (pintype "bidirectional"))
      (node (ref "F6") (pin "P$1") (pinfunction "P$1_P$1") (pintype "bidirectional"))
      (node (ref "PHABULOUS") (pin "3") (pinfunction "3_3") (pintype "bidirectional"))
      (node (ref "R115") (pin "1") (pinfunction "1_1") (pintype "passive"))
      (node (ref "R134") (pin "2") (pinfunction "2_2") (pintype "passive"))
      (node (ref "R139") (pin "1") (pinfunction "1_1") (pintype "passive"))
      (node (ref "R140") (pin "1") (pinfunction "1_1") (pintype "passive"))
      (node (ref "R141") (pin "1") (pinfunction "1_1") (pintype "passive"))
      (node (ref "R142") (pin "1") (pinfunction "1_1") (pintype "passive"))
      (node (ref "R143") (pin "1") (pinfunction "1_1") (pintype "passive"))
      (node (ref "R144") (pin "1") (pinfunction "1_1") (pintype "passive"))
      (node (ref "R145") (pin "1") (pinfunction "1_1") (pintype "passive"))
      (node (ref "RGB_COM_OUT") (pin "P$7") (pinfunction "7_P$7") (pintype "bidirectional"))
      (node (ref "ST_LI") (pin "S") (pinfunction "EMITTER_S") (pintype "bidirectional"))
      (node (ref "U10") (pin "5") (pinfunction "VCC_5") (pintype "bidirectional"))
      (node (ref "U14") (pin "14") (pinfunction "VCC_14") (pintype "bidirectional"))
      (node (ref "U15") (pin "14") (pinfunction "VCC_14") (pintype "bidirectional"))
      (node (ref "U16") (pin "14") (pinfunction "VCC_14") (pintype "bidirectional"))
      (node (ref "U17") (pin "14") (pinfunction "VCC_14") (pintype "bidirectional"))
      (node (ref "U18") (pin "14") (pinfunction "VCC_14") (pintype "bidirectional"))
      (node (ref "U19") (pin "14") (pinfunction "VCC_14") (pintype "bidirectional"))
      (node (ref "U3") (pin "10") (pinfunction "MR_10") (pintype "bidirectional"))
      (node (ref "U3") (pin "16") (pinfunction "VCC_16") (pintype "bidirectional"))
      (node (ref "U39") (pin "3") (pinfunction "IN_3") (pintype "bidirectional"))
      (node (ref "U5") (pin "10") (pinfunction "MR_10") (pintype "bidirectional"))
      (node (ref "U5") (pin "16") (pinfunction "VCC_16") (pintype "bidirectional"))
      (node (ref "U52") (pin "16") (pinfunction "VCC_16") (pintype "bidirectional"))
      (node (ref "U52") (pin "2") (pinfunction "~{1B}_2") (pintype "bidirectional"))
      (node (ref "U52") (pin "3") (pinfunction "~{1R}_3") (pintype "bidirectional"))
      (node (ref "U6") (pin "P$6") (pinfunction "OUT_P$6") (pintype "bidirectional"))
      (node (ref "U6") (pin "P$7") (pinfunction "OUT_P$7") (pintype "bidirectional"))
      (node (ref "U6") (pin "P$8") (pinfunction "OUT_P$8") (pintype "bidirectional"))
    )
    (net (code "3") (name "/5V_IN") (class "Default")
      (node (ref "5V") (pin "P$1") (pinfunction "P$1_P$1") (pintype "bidirectional"))
      (node (ref "BOARD_POWER_IN") (pin "1") (pinfunction "PIN1_1") (pintype "bidirectional"))
      (node (ref "C58") (pin "1") (pinfunction "1_1") (pintype "passive"))
      (node (ref "D3") (pin "CATH") (pinfunction "CATHODE_CATH") (pintype "bidirectional"))
      (node (ref "R147") (pin "1") (pinfunction "1_1") (pintype "passive"))
      (node (ref "U6") (pin "P$3") (pinfunction "VIN_P$3") (pintype "bidirectional"))
      (node (ref "U6") (pin "P$4") (pinfunction "VIN_P$4") (pintype "bidirectional"))
      (node (ref "U6") (pin "P$5") (pinfunction "VIN_P$5") (pintype "bidirectional"))
    )
    (net (code "4") (name "/12V") (class "Default")
      (node (ref "AUX_PWR") (pin "2") (pinfunction "2_2") (pintype "passive"))
      (node (ref "C17") (pin "P$1") (pinfunction "P$1_P$1") (pintype "passive"))
      (node (ref "C29") (pin "P$1") (pinfunction "P$1_P$1") (pintype "passive"))
      (node (ref "C43") (pin "1") (pinfunction "1_1") (pintype "passive"))
      (node (ref "C44") (pin "1") (pinfunction "1_1") (pintype "passive"))
      (node (ref "C45") (pin "1") (pinfunction "1_1") (pintype "passive"))
      (node (ref "CAB_RGB") (pin "P$3") (pinfunction "3_P$3") (pintype "bidirectional"))
      (node (ref "CAB_RGB") (pin "P$7") (pinfunction "7_P$7") (pintype "bidirectional"))
      (node (ref "DMD_PWR") (pin "2") (pinfunction "PIN1_2") (pintype "bidirectional"))
      (node (ref "F7") (pin "P$1") (pinfunction "P$1_P$1") (pintype "bidirectional"))
      (node (ref "PHABULOUS") (pin "7") (pinfunction "7_7") (pintype "bidirectional"))
      (node (ref "R83") (pin "1") (pinfunction "1_1") (pintype "passive"))
      (node (ref "R85") (pin "1") (pinfunction "1_1") (pintype "passive"))
      (node (ref "R87") (pin "1") (pinfunction "1_1") (pintype "passive"))
      (node (ref "R89") (pin "1") (pinfunction "1_1") (pintype "passive"))
      (node (ref "R91") (pin "1") (pinfunction "1_1") (pintype "passive"))
      (node (ref "R93") (pin "1") (pinfunction "1_1") (pintype "passive"))
      (node (ref "R95") (pin "1") (pinfunction "1_1") (pintype "passive"))
      (node (ref "R97") (pin "1") (pinfunction "1_1") (pintype "passive"))
      (node (ref "RGB_COM_OUT") (pin "P$6") (pinfunction "6_P$6") (pintype "bidirectional"))
      (node (ref "U20") (pin "S") (pinfunction "EMITTER_S") (pintype "bidirectional"))
      (node (ref "U21") (pin "S") (pinfunction "EMITTER_S") (pintype "bidirectional"))
      (node (ref "U22") (pin "S") (pinfunction "EMITTER_S") (pintype "bidirectional"))
      (node (ref "U23") (pin "S") (pinfunction "EMITTER_S") (pintype "bidirectional"))
      (node (ref "U24") (pin "S") (pinfunction "EMITTER_S") (pintype "bidirectional"))
      (node (ref "U25") (pin "S") (pinfunction "EMITTER_S") (pintype "bidirectional"))
      (node (ref "U26") (pin "S") (pinfunction "EMITTER_S") (pintype "bidirectional"))
      (node (ref "U27") (pin "S") (pinfunction "EMITTER_S") (pintype "bidirectional"))
      (node (ref "U7") (pin "P$6") (pinfunction "OUT_P$6") (pintype "bidirectional"))
      (node (ref "U7") (pin "P$7") (pinfunction "OUT_P$7") (pintype "bidirectional"))
      (node (ref "U7") (pin "P$8") (pinfunction "OUT_P$8") (pintype "bidirectional"))
    )
    (net (code "5") (name "/12V_IN") (class "Default")
      (node (ref "12V") (pin "P$1") (pinfunction "P$1_P$1") (pintype "bidirectional"))
      (node (ref "BOARD_POWER_IN") (pin "3") (pinfunction "PIN2_3") (pintype "bidirectional"))
      (node (ref "C60") (pin "1") (pinfunction "1_1") (pintype "passive"))
      (node (ref "D4") (pin "CATH") (pinfunction "CATHODE_CATH") (pintype "bidirectional"))
      (node (ref "R158") (pin "1") (pinfunction "1_1") (pintype "passive"))
      (node (ref "U7") (pin "P$3") (pinfunction "VIN_P$3") (pintype "bidirectional"))
      (node (ref "U7") (pin "P$4") (pinfunction "VIN_P$4") (pintype "bidirectional"))
      (node (ref "U7") (pin "P$5") (pinfunction "VIN_P$5") (pintype "bidirectional"))
    )
    (net (code "6") (name "/50V") (class "Default")
      (node (ref "50V") (pin "P$1") (pinfunction "P$1_P$1") (pintype "bidirectional"))
      (node (ref "F1") (pin "P$1") (pinfunction "P$1_P$1") (pintype "bidirectional"))
      (node (ref "F2") (pin "P$1") (pinfunction "P$1_P$1") (pintype "bidirectional"))
      (node (ref "F3") (pin "P$1") (pinfunction "P$1_P$1") (pintype "bidirectional"))
      (node (ref "SOLENOID_POWER_IN") (pin "4") (pinfunction "PIN3_4") (pintype "bidirectional"))
    )
    (net (code "7") (name "/50V_FUSE_0") (class "Default")
      (node (ref "D9") (pin "ANODE") (pinfunction "ANODE_ANODE") (pintype "power_in"))
      (node (ref "F1") (pin "P$2") (pinfunction "P$2_P$2") (pintype "bidirectional"))
      (node (ref "KNOCKER") (pin "P$1") (pinfunction "PIN1_P$1") (pintype "bidirectional"))
      (node (ref "SHAKER") (pin "P$1") (pinfunction "PIN1_P$1") (pintype "bidirectional"))
      (node (ref "SOL_BANK_0") (pin "P$1") (pinfunction "PIN1_P$1") (pintype "bidirectional"))
    )
    (net (code "8") (name "/50V_FUSE_1") (class "Default")
      (node (ref "D10") (pin "ANODE") (pinfunction "ANODE_ANODE") (pintype "power_in"))
      (node (ref "F2") (pin "P$2") (pinfunction "P$2_P$2") (pintype "bidirectional"))
      (node (ref "SOL_BANK_1") (pin "P$1") (pinfunction "PIN1_P$1") (pintype "bidirectional"))
    )
    (net (code "9") (name "/50V_FUSE_2") (class "Default")
      (node (ref "D11") (pin "ANODE") (pinfunction "ANODE_ANODE") (pintype "power_in"))
      (node (ref "F3") (pin "P$2") (pinfunction "P$2_P$2") (pintype "bidirectional"))
      (node (ref "SOL_BANK_2") (pin "P$1") (pinfunction "PIN1_P$1") (pintype "bidirectional"))
    )
    (net (code "10") (name "/AUD0") (class "Default")
      (node (ref "R32") (pin "1") (pinfunction "1_1") (pintype "passive"))
      (node (ref "U1") (pin "16") (pinfunction "P15_16") (pintype "bidirectional"))
    )
    (net (code "11") (name "/AUD1") (class "Default")
      (node (ref "R34") (pin "1") (pinfunction "1_1") (pintype "passive"))
      (node (ref "U1") (pin "15") (pinfunction "P14_15") (pintype "bidirectional"))
    )
    (net (code "12") (name "/AUX_0") (class "Default")
      (node (ref "R138") (pin "1") (pinfunction "1_1") (pintype "passive"))
      (node (ref "R35") (pin "1") (pinfunction "1_1") (pintype "passive"))
      (node (ref "U11") (pin "11") (pinfunction "D0_11") (pintype "bidirectional"))
    )
    (net (code "13") (name "/AUX_1") (class "Default")
      (node (ref "R31") (pin "1") (pinfunction "1_1") (pintype "passive"))
      (node (ref "R36") (pin "1") (pinfunction "1_1") (pintype "passive"))
      (node (ref "U11") (pin "12") (pinfunction "D1_12") (pintype "bidirectional"))
    )
    (net (code "14") (name "/AUX_2") (class "Default")
      (node (ref "R28") (pin "1") (pinfunction "1_1") (pintype "passive"))
      (node (ref "R37") (pin "1") (pinfunction "1_1") (pintype "passive"))
      (node (ref "U11") (pin "13") (pinfunction "D2_13") (pintype "bidirectional"))
    )
    (net (code "15") (name "/AUX_3") (class "Default")
      (node (ref "R15") (pin "1") (pinfunction "1_1") (pintype "passive"))
      (node (ref "R39") (pin "1") (pinfunction "1_1") (pintype "passive"))
      (node (ref "U11") (pin "3") (pinfunction "D4_3") (pintype "bidirectional"))
    )
    (net (code "16") (name "/AUX_4") (class "Default")
      (node (ref "R10") (pin "1") (pinfunction "1_1") (pintype "passive"))
      (node (ref "R40") (pin "1") (pinfunction "1_1") (pintype "passive"))
      (node (ref "U11") (pin "4") (pinfunction "D5_4") (pintype "bidirectional"))
    )
    (net (code "17") (name "/AUX_5") (class "Default")
      (node (ref "R41") (pin "1") (pinfunction "1_1") (pintype "passive"))
      (node (ref "R7") (pin "1") (pinfunction "1_1") (pintype "passive"))
      (node (ref "U11") (pin "5") (pinfunction "D6_5") (pintype "bidirectional"))
    )
    (net (code "18") (name "/AUX_6") (class "Default")
      (node (ref "R42") (pin "1") (pinfunction "1_1") (pintype "passive"))
      (node (ref "R5") (pin "1") (pinfunction "1_1") (pintype "passive"))
      (node (ref "U11") (pin "6") (pinfunction "D7_6") (pintype "bidirectional"))
    )
    (net (code "19") (name "/AVCC") (class "Default")
      (node (ref "C8") (pin "1") (pinfunction "1_1") (pintype "passive"))
      (node (ref "C9") (pin "1") (pinfunction "1_1") (pintype "passive"))
      (node (ref "IC2") (pin "30") (pinfunction "AVDD_30") (pintype "bidirectional"))
      (node (ref "R3") (pin "2") (pinfunction "2_2") (pintype "passive"))
    )
    (net (code "20") (name "/BACK") (class "Default")
      (node (ref "R152") (pin "2") (pinfunction "2_2") (pintype "passive"))
      (node (ref "R47") (pin "1") (pinfunction "1_1") (pintype "passive"))
      (node (ref "U12") (pin "3") (pinfunction "D4_3") (pintype "bidirectional"))
    )
    (net (code "21") (name "/BACK_OUT") (class "Default")
      (node (ref "BACK_OUT") (pin "P$1") (pinfunction "P$1_P$1") (pintype "bidirectional"))
      (node (ref "CABINET_I/O") (pin "P$8") (pinfunction "8_P$8") (pintype "bidirectional"))
      (node (ref "R152") (pin "1") (pinfunction "1_1") (pintype "passive"))
    )
    (net (code "22") (name "/BKUP_V") (class "Default")
      (node (ref "BATT1") (pin "POS") (pinfunction "+_POS") (pintype "bidirectional"))
      (node (ref "U2") (pin "3") (pinfunction "V_BACK_3") (pintype "bidirectional"))
    )
    (net (code "23") (name "/CAB_CLK") (class "Default")
      (node (ref "IC2") (pin "93") (pinfunction "PMD0/RE0_93") (pintype "bidirectional"))
      (node (ref "U11") (pin "2") (pinfunction "CLK_2") (pintype "bidirectional"))
      (node (ref "U12") (pin "2") (pinfunction "CLK_2") (pintype "bidirectional"))
      (node (ref "U3") (pin "11") (pinfunction "SHCP_11") (pintype "bidirectional"))
      (node (ref "U5") (pin "11") (pinfunction "SHCP_11") (pintype "bidirectional"))
    )
    (net (code "24") (name "/CAB_GI_OUT") (class "Default")
      (node (ref "IC2") (pin "11") (pinfunction "ECRS/SDA2A/SDI2A/U2ARX/PMA4/CN9/RG7_11") (pintype "bidirectional"))
      (node (ref "U3") (pin "14") (pinfunction "DS_14") (pintype "bidirectional"))
    )
    (net (code "25") (name "/CAB_LAT") (class "Default")
      (node (ref "IC2") (pin "12") (pinfunction "SCL2A/SDO2A/U2ATX/PMA3/CN10/RG8_12") (pintype "bidirectional"))
      (node (ref "U10") (pin "1") (pinfunction "1A_1") (pintype "bidirectional"))
      (node (ref "U11") (pin "1") (pinfunction "LAT_1") (pintype "bidirectional"))
      (node (ref "U12") (pin "1") (pinfunction "LAT_1") (pintype "bidirectional"))
    )
    (net (code "26") (name "/CAB_SWITCH_IN") (class "Default")
      (node (ref "IC2") (pin "87") (pinfunction "C1RX/ETXD1/PMD11/RF0_87") (pintype "bidirectional"))
      (node (ref "U11") (pin "9") (pinfunction "QH_9") (pintype "bidirectional"))
    )
    (net (code "27") (name "/COIN") (class "Default")
      (node (ref "R150") (pin "2") (pinfunction "2_2") (pintype "passive"))
      (node (ref "R49") (pin "1") (pinfunction "1_1") (pintype "passive"))
      (node (ref "U12") (pin "5") (pinfunction "D6_5") (pintype "bidirectional"))
    )
    (net (code "28") (name "/COIN_OUT") (class "Default")
      (node (ref "CABINET_I/O") (pin "P$6") (pinfunction "6_P$6") (pintype "bidirectional"))
      (node (ref "COIN_OUT") (pin "P$1") (pinfunction "P$1_P$1") (pintype "bidirectional"))
      (node (ref "R150") (pin "1") (pinfunction "1_1") (pintype "passive"))
    )
    (net (code "29") (name "/COMM_CLK_RX") (class "Default")
      (node (ref "IC2") (pin "40") (pinfunction "AC1RX/SS3A/U3BRX/U3ACTS/RF12_40") (pintype "bidirectional"))
      (node (ref "U1") (pin "32") (pinfunction "P25_32") (pintype "bidirectional"))
    )
    (net (code "30") (name "/COMM_IN_TX") (class "Default")
      (node (ref "IC2") (pin "39") (pinfunction "AC1TX/SCK3A/U3BTX/U3ARTS/RF13_39") (pintype "bidirectional"))
      (node (ref "U1") (pin "31") (pinfunction "P24_31") (pintype "bidirectional"))
    )
    (net (code "31") (name "/COMM_OUT") (class "Default")
      (node (ref "IC2") (pin "50") (pinfunction "SCL3A/SDO3A/U3ATX/PMA8/CN18/RF5_50") (pintype "bidirectional"))
      (node (ref "U1") (pin "33") (pinfunction "P26_33") (pintype "bidirectional"))
    )
    (net (code "32") (name "/DATA_CAB1") (class "Default")
      (node (ref "U11") (pin "10") (pinfunction "SER_10") (pintype "bidirectional"))
      (node (ref "U12") (pin "9") (pinfunction "QH_9") (pintype "bidirectional"))
    )
    (net (code "33") (name "/DMD_1") (class "Default")
      (node (ref "DMD_1") (pin "P$1") (pinfunction "P$1_P$1") (pintype "bidirectional"))
      (node (ref "DMD_CON") (pin "1") (pinfunction "PIN1_1") (pintype "bidirectional"))
      (node (ref "U1") (pin "25") (pinfunction "P22_25") (pintype "bidirectional"))
    )
    (net (code "34") (name "/DMD_3") (class "Default")
      (node (ref "DMD_3") (pin "P$1") (pinfunction "P$1_P$1") (pintype "bidirectional"))
      (node (ref "DMD_CON") (pin "3") (pinfunction "PIN3_3") (pintype "bidirectional"))
      (node (ref "U1") (pin "24") (pinfunction "P21_24") (pintype "bidirectional"))
    )
    (net (code "35") (name "/DMD_5") (class "Default")
      (node (ref "DMD_5") (pin "P$1") (pinfunction "P$1_P$1") (pintype "bidirectional"))
      (node (ref "DMD_CON") (pin "5") (pinfunction "PIN5_5") (pintype "bidirectional"))
      (node (ref "U1") (pin "23") (pinfunction "P20_23") (pintype "bidirectional"))
    )
    (net (code "36") (name "/DMD_7") (class "Default")
      (node (ref "DMD_7") (pin "P$1") (pinfunction "P$1_P$1") (pintype "bidirectional"))
      (node (ref "DMD_CON") (pin "7") (pinfunction "PIN7_7") (pintype "bidirectional"))
      (node (ref "U1") (pin "22") (pinfunction "P19_22") (pintype "bidirectional"))
    )
    (net (code "37") (name "/DMD_9") (class "Default")
      (node (ref "DMD_9") (pin "P$1") (pinfunction "P$1_P$1") (pintype "bidirectional"))
      (node (ref "DMD_CON") (pin "9") (pinfunction "PIN9_9") (pintype "bidirectional"))
      (node (ref "U1") (pin "21") (pinfunction "P18_21") (pintype "bidirectional"))
    )
    (net (code "38") (name "/DMD_11") (class "Default")
      (node (ref "DMD_11") (pin "P$1") (pinfunction "P$1_P$1") (pintype "bidirectional"))
      (node (ref "DMD_CON") (pin "11") (pinfunction "PIN11_11") (pintype "bidirectional"))
      (node (ref "U1") (pin "20") (pinfunction "P17_20") (pintype "bidirectional"))
    )
    (net (code "39") (name "/DMD_13") (class "Default")
      (node (ref "DMD_13") (pin "P$1") (pinfunction "P$1_P$1") (pintype "bidirectional"))
      (node (ref "DMD_CON") (pin "13") (pinfunction "PIN13_13") (pintype "bidirectional"))
      (node (ref "U1") (pin "19") (pinfunction "P16_19") (pintype "bidirectional"))
    )
    (net (code "40") (name "/DOOR") (class "Default")
      (node (ref "R153") (pin "2") (pinfunction "2_2") (pintype "passive"))
      (node (ref "R43") (pin "1") (pinfunction "1_1") (pintype "passive"))
      (node (ref "U12") (pin "11") (pinfunction "D0_11") (pintype "bidirectional"))
    )
    (net (code "41") (name "/DOOR_OUT") (class "Default")
      (node (ref "CABINET_I/O") (pin "P$9") (pinfunction "9_P$9") (pintype "bidirectional"))
      (node (ref "DOOR_OUT") (pin "P$1") (pinfunction "P$1_P$1") (pintype "bidirectional"))
      (node (ref "R153") (pin "1") (pinfunction "1_1") (pintype "passive"))
    )
    (net (code "42") (name "/ENTER") (class "Default")
      (node (ref "R151") (pin "2") (pinfunction "2_2") (pintype "passive"))
      (node (ref "R48") (pin "1") (pinfunction "1_1") (pintype "passive"))
      (node (ref "U12") (pin "4") (pinfunction "D5_4") (pintype "bidirectional"))
    )
    (net (code "43") (name "/ENTER_OUT") (class "Default")
      (node (ref "CABINET_I/O") (pin "P$7") (pinfunction "7_P$7") (pintype "bidirectional"))
      (node (ref "ENTER_OUT") (pin "P$1") (pinfunction "P$1_P$1") (pintype "bidirectional"))
      (node (ref "R151") (pin "1") (pinfunction "1_1") (pintype "passive"))
    )
    (net (code "44") (name "/EXT_RGB_CLK") (class "Default")
      (node (ref "EXT_RGB_CLK") (pin "P$1") (pinfunction "P$1_P$1") (pintype "bidirectional"))
      (node (ref "IC2") (pin "6") (pinfunction "T2CK/RC1_6") (pintype "bidirectional"))
      (node (ref "RGB_COM_OUT") (pin "P$5") (pinfunction "5_P$5") (pintype "bidirectional"))
    )
    (net (code "45") (name "/EXT_RGB_DATA") (class "Default")
      (node (ref "EXT_RGB_DATA") (pin "P$1") (pinfunction "P$1_P$1") (pintype "bidirectional"))
      (node (ref "IC2") (pin "10") (pinfunction "ECOL/SCK2A/U2BTXU2ARTS/PMA5/CN8/RG6_10") (pintype "bidirectional"))
      (node (ref "RGB_COM_OUT") (pin "P$4") (pinfunction "4_P$4") (pintype "bidirectional"))
    )
    (net (code "46") (name "/FLASH_12V") (class "Default")
      (node (ref "D6") (pin "ANODE") (pinfunction "ANODE_ANODE") (pintype "power_in"))
      (node (ref "F7") (pin "P$2") (pinfunction "P$2_P$2") (pintype "bidirectional"))
      (node (ref "FLASHER") (pin "P$1") (pinfunction "PIN1_P$1") (pintype "bidirectional"))
    )
    (net (code "47") (name "/GI0_5V") (class "Default")
      (node (ref "D7") (pin "ANODE") (pinfunction "ANODE_ANODE") (pintype "power_in"))
      (node (ref "F5") (pin "P$2") (pinfunction "P$2_P$2") (pintype "bidirectional"))
      (node (ref "GI_0") (pin "P$10") (pinfunction "PIN9_P$10") (pintype "bidirectional"))
    )
    (net (code "48") (name "/GI1_5V") (class "Default")
      (node (ref "D8") (pin "ANODE") (pinfunction "ANODE_ANODE") (pintype "power_in"))
      (node (ref "F4") (pin "P$2") (pinfunction "P$2_P$2") (pintype "bidirectional"))
      (node (ref "GI_1") (pin "P$9") (pinfunction "PIN9_P$9") (pintype "bidirectional"))
    )
    (net (code "49") (name "/GI15") (class "Default")
      (node (ref "GI15") (pin "D") (pinfunction "COLLECTOR_D") (pintype "bidirectional"))
      (node (ref "GI15_") (pin "P$1") (pinfunction "P$1_P$1") (pintype "bidirectional"))
      (node (ref "GI_1") (pin "P$8") (pinfunction "PIN8_P$8") (pintype "bidirectional"))
    )
    (net (code "50") (name "/GI_0") (class "Default")
      (node (ref "R99") (pin "1") (pinfunction "1_1") (pintype "passive"))
      (node (ref "U3") (pin "15") (pinfunction "Q0_15") (pintype "bidirectional"))
    )
    (net (code "51") (name "/GI_1") (class "Default")
      (node (ref "R101") (pin "1") (pinfunction "1_1") (pintype "passive"))
      (node (ref "U3") (pin "1") (pinfunction "Q1_1") (pintype "bidirectional"))
    )
    (net (code "52") (name "/GI_2") (class "Default")
      (node (ref "R103") (pin "1") (pinfunction "1_1") (pintype "passive"))
      (node (ref "U3") (pin "2") (pinfunction "Q2_2") (pintype "bidirectional"))
    )
    (net (code "53") (name "/GI_3") (class "Default")
      (node (ref "R105") (pin "1") (pinfunction "1_1") (pintype "passive"))
      (node (ref "U3") (pin "3") (pinfunction "Q3_3") (pintype "bidirectional"))
    )
    (net (code "54") (name "/GI_4") (class "Default")
      (node (ref "R107") (pin "1") (pinfunction "1_1") (pintype "passive"))
      (node (ref "U3") (pin "4") (pinfunction "Q4_4") (pintype "bidirectional"))
    )
    (net (code "55") (name "/GI_5") (class "Default")
      (node (ref "R109") (pin "1") (pinfunction "1_1") (pintype "passive"))
      (node (ref "U3") (pin "5") (pinfunction "Q5_5") (pintype "bidirectional"))
    )
    (net (code "56") (name "/GI_6") (class "Default")
      (node (ref "R111") (pin "1") (pinfunction "1_1") (pintype "passive"))
      (node (ref "U3") (pin "6") (pinfunction "Q6_6") (pintype "bidirectional"))
    )
    (net (code "57") (name "/GI_7") (class "Default")
      (node (ref "R113") (pin "1") (pinfunction "1_1") (pintype "passive"))
      (node (ref "U3") (pin "7") (pinfunction "Q7_7") (pintype "bidirectional"))
    )
    (net (code "58") (name "/GI_8") (class "Default")
      (node (ref "R125") (pin "1") (pinfunction "1_1") (pintype "passive"))
      (node (ref "U5") (pin "15") (pinfunction "Q0_15") (pintype "bidirectional"))
    )
    (net (code "59") (name "/GI_9") (class "Default")
      (node (ref "R126") (pin "1") (pinfunction "1_1") (pintype "passive"))
      (node (ref "U5") (pin "1") (pinfunction "Q1_1") (pintype "bidirectional"))
    )
    (net (code "60") (name "/GI_10") (class "Default")
      (node (ref "R127") (pin "1") (pinfunction "1_1") (pintype "passive"))
      (node (ref "U5") (pin "2") (pinfunction "Q2_2") (pintype "bidirectional"))
    )
    (net (code "61") (name "/GI_11") (class "Default")
      (node (ref "R128") (pin "1") (pinfunction "1_1") (pintype "passive"))
      (node (ref "U5") (pin "3") (pinfunction "Q3_3") (pintype "bidirectional"))
    )
    (net (code "62") (name "/GI_12") (class "Default")
      (node (ref "R129") (pin "1") (pinfunction "1_1") (pintype "passive"))
      (node (ref "U5") (pin "4") (pinfunction "Q4_4") (pintype "bidirectional"))
    )
    (net (code "63") (name "/GI_13") (class "Default")
      (node (ref "R130") (pin "1") (pinfunction "1_1") (pintype "passive"))
      (node (ref "U5") (pin "5") (pinfunction "Q5_5") (pintype "bidirectional"))
    )
    (net (code "64") (name "/GI_14") (class "Default")
      (node (ref "R131") (pin "1") (pinfunction "1_1") (pintype "passive"))
      (node (ref "U5") (pin "6") (pinfunction "Q6_6") (pintype "bidirectional"))
    )
    (net (code "65") (name "/GI_15") (class "Default")
      (node (ref "R132") (pin "1") (pinfunction "1_1") (pintype "passive"))
      (node (ref "U5") (pin "7") (pinfunction "Q7_7") (pintype "bidirectional"))
    )
    (net (code "66") (name "/GI_DATA_COL_B") (class "Default")
      (node (ref "U3") (pin "9") (pinfunction "Q7S_9") (pintype "bidirectional"))
      (node (ref "U5") (pin "14") (pinfunction "DS_14") (pintype "bidirectional"))
    )
    (net (code "67") (name "/GI_R_0") (class "Default")
      (node (ref "GI0") (pin "D") (pinfunction "COLLECTOR_D") (pintype "bidirectional"))
      (node (ref "GI_0") (pin "P$1") (pinfunction "PIN1_P$1") (pintype "bidirectional"))
      (node (ref "GI_R_0") (pin "P$1") (pinfunction "P$1_P$1") (pintype "bidirectional"))
    )
    (net (code "68") (name "/GI_R_1") (class "Default")
      (node (ref "GI1") (pin "D") (pinfunction "COLLECTOR_D") (pintype "bidirectional"))
      (node (ref "GI_0") (pin "P$2") (pinfunction "PIN2_P$2") (pintype "bidirectional"))
      (node (ref "GI_R_1") (pin "P$1") (pinfunction "P$1_P$1") (pintype "bidirectional"))
    )
    (net (code "69") (name "/GI_R_2") (class "Default")
      (node (ref "GI2") (pin "D") (pinfunction "COLLECTOR_D") (pintype "bidirectional"))
      (node (ref "GI_0") (pin "P$3") (pinfunction "PIN3_P$3") (pintype "bidirectional"))
      (node (ref "GI_R_2") (pin "P$1") (pinfunction "P$1_P$1") (pintype "bidirectional"))
    )
    (net (code "70") (name "/GI_R_3") (class "Default")
      (node (ref "GI3") (pin "D") (pinfunction "COLLECTOR_D") (pintype "bidirectional"))
      (node (ref "GI_0") (pin "P$4") (pinfunction "PIN4_P$4") (pintype "bidirectional"))
      (node (ref "GI_R_3") (pin "P$1") (pinfunction "P$1_P$1") (pintype "bidirectional"))
    )
    (net (code "71") (name "/GI_R_4") (class "Default")
      (node (ref "GI4") (pin "D") (pinfunction "COLLECTOR_D") (pintype "bidirectional"))
      (node (ref "GI_0") (pin "P$5") (pinfunction "PIN5_P$5") (pintype "bidirectional"))
      (node (ref "GI_R_4") (pin "P$1") (pinfunction "P$1_P$1") (pintype "bidirectional"))
    )
    (net (code "72") (name "/GI_R_5") (class "Default")
      (node (ref "GI5") (pin "D") (pinfunction "COLLECTOR_D") (pintype "bidirectional"))
      (node (ref "GI_0") (pin "P$6") (pinfunction "PIN6_P$6") (pintype "bidirectional"))
      (node (ref "GI_R_5") (pin "P$1") (pinfunction "P$1_P$1") (pintype "bidirectional"))
    )
    (net (code "73") (name "/GI_R_6") (class "Default")
      (node (ref "GI6") (pin "D") (pinfunction "COLLECTOR_D") (pintype "bidirectional"))
      (node (ref "GI_0") (pin "P$7") (pinfunction "PIN7_P$7") (pintype "bidirectional"))
      (node (ref "GI_R_6") (pin "P$1") (pinfunction "P$1_P$1") (pintype "bidirectional"))
    )
    (net (code "74") (name "/GI_R_7") (class "Default")
      (node (ref "GI7") (pin "D") (pinfunction "COLLECTOR_D") (pintype "bidirectional"))
      (node (ref "GI_0") (pin "P$8") (pinfunction "PIN8_P$8") (pintype "bidirectional"))
      (node (ref "GI_R_7") (pin "P$1") (pinfunction "P$1_P$1") (pintype "bidirectional"))
    )
    (net (code "75") (name "/GI_R_8") (class "Default")
      (node (ref "GI8") (pin "D") (pinfunction "COLLECTOR_D") (pintype "bidirectional"))
      (node (ref "GI_1") (pin "P$1") (pinfunction "PIN1_P$1") (pintype "bidirectional"))
      (node (ref "GI_R_8") (pin "P$1") (pinfunction "P$1_P$1") (pintype "bidirectional"))
    )
    (net (code "76") (name "/GI_R_9") (class "Default")
      (node (ref "GI9") (pin "D") (pinfunction "COLLECTOR_D") (pintype "bidirectional"))
      (node (ref "GI_1") (pin "P$2") (pinfunction "PIN2_P$2") (pintype "bidirectional"))
      (node (ref "GI_R_9") (pin "P$1") (pinfunction "P$1_P$1") (pintype "bidirectional"))
    )
    (net (code "77") (name "/GI_R_10") (class "Default")
      (node (ref "GI10") (pin "D") (pinfunction "COLLECTOR_D") (pintype "bidirectional"))
      (node (ref "GI_1") (pin "P$3") (pinfunction "PIN3_P$3") (pintype "bidirectional"))
      (node (ref "GI_R_10") (pin "P$1") (pinfunction "P$1_P$1") (pintype "bidirectional"))
    )
    (net (code "78") (name "/GI_R_11") (class "Default")
      (node (ref "GI11") (pin "D") (pinfunction "COLLECTOR_D") (pintype "bidirectional"))
      (node (ref "GI_1") (pin "P$4") (pinfunction "PIN4_P$4") (pintype "bidirectional"))
      (node (ref "GI_R_11") (pin "P$1") (pinfunction "P$1_P$1") (pintype "bidirectional"))
    )
    (net (code "79") (name "/GI_R_12") (class "Default")
      (node (ref "GI12") (pin "D") (pinfunction "COLLECTOR_D") (pintype "bidirectional"))
      (node (ref "GI_1") (pin "P$5") (pinfunction "PIN5_P$5") (pintype "bidirectional"))
      (node (ref "GI_R_12") (pin "P$1") (pinfunction "P$1_P$1") (pintype "bidirectional"))
    )
    (net (code "80") (name "/GI_R_13") (class "Default")
      (node (ref "GI13") (pin "D") (pinfunction "COLLECTOR_D") (pintype "bidirectional"))
      (node (ref "GI_1") (pin "P$6") (pinfunction "PIN6_P$6") (pintype "bidirectional"))
      (node (ref "GI_R_13") (pin "P$1") (pinfunction "P$1_P$1") (pintype "bidirectional"))
    )
    (net (code "81") (name "/GI_R_14") (class "Default")
      (node (ref "GI14") (pin "D") (pinfunction "COLLECTOR_D") (pintype "bidirectional"))
      (node (ref "GI_1") (pin "P$7") (pinfunction "PIN7_P$7") (pintype "bidirectional"))
      (node (ref "GI_R_14") (pin "P$1") (pinfunction "P$1_P$1") (pintype "bidirectional"))
    )
    (net (code "82") (name "/GND") (class "Default")
      (node (ref "AUDIO") (pin "1_A") (pinfunction "S_1_A") (pintype "bidirectional"))
      (node (ref "AUDIO") (pin "1_B") (pinfunction "S_1_B") (pintype "bidirectional"))
      (node (ref "AUDIO") (pin "S1") (pinfunction "SHIELD_S1") (pintype "bidirectional"))
      (node (ref "AUDIO") (pin "S2") (pinfunction "SHIELD_S2") (pintype "bidirectional"))
      (node (ref "AUDIO") (pin "S3") (pinfunction "SHIELD_S3") (pintype "bidirectional"))
      (node (ref "AUDIO") (pin "S4") (pinfunction "SHIELD_S4") (pintype "bidirectional"))
      (node (ref "AUDIO") (pin "S5") (pinfunction "SHIELD_S5") (pintype "bidirectional"))
      (node (ref "AUDIO") (pin "S6") (pinfunction "SHIELD_S6") (pintype "bidirectional"))
      (node (ref "AUX_PWR") (pin "1") (pinfunction "1_1") (pintype "passive"))
      (node (ref "BATT1") (pin "NEG") (pinfunction "-_NEG") (pintype "bidirectional"))
      (node (ref "BOARD_POWER_IN") (pin "4") (pinfunction "PIN3_4") (pintype "bidirectional"))
      (node (ref "C10") (pin "2") (pinfunction "2_2") (pintype "passive"))
      (node (ref "C11") (pin "2") (pinfunction "2_2") (pintype "passive"))
      (node (ref "C12") (pin "1") (pinfunction "1_1") (pintype "passive"))
      (node (ref "C13") (pin "2") (pinfunction "2_2") (pintype "passive"))
      (node (ref "C14") (pin "2") (pinfunction "2_2") (pintype "passive"))
      (node (ref "C15") (pin "P$2") (pinfunction "P$2_P$2") (pintype "passive"))
      (node (ref "C16") (pin "P$2") (pinfunction "P$2_P$2") (pintype "passive"))
      (node (ref "C17") (pin "P$2") (pinfunction "P$2_P$2") (pintype "passive"))
      (node (ref "C18") (pin "P$2") (pinfunction "P$2_P$2") (pintype "passive"))
      (node (ref "C19") (pin "P$2") (pinfunction "P$2_P$2") (pintype "passive"))
      (node (ref "C2") (pin "2") (pinfunction "2_2") (pintype "passive"))
      (node (ref "C20") (pin "1") (pinfunction "1_1") (pintype "passive"))
      (node (ref "C21") (pin "1") (pinfunction "1_1") (pintype "passive"))
      (node (ref "C22") (pin "1") (pinfunction "1_1") (pintype "passive"))
      (node (ref "C23") (pin "1") (pinfunction "1_1") (pintype "passive"))
      (node (ref "C24") (pin "1") (pinfunction "1_1") (pintype "passive"))
      (node (ref "C25") (pin "1") (pinfunction "1_1") (pintype "passive"))
      (node (ref "C26") (pin "1") (pinfunction "1_1") (pintype "passive"))
      (node (ref "C27") (pin "NEG") (pinfunction "NEG_NEG") (pintype "bidirectional"))
      (node (ref "C28") (pin "1") (pinfunction "1_1") (pintype "passive"))
      (node (ref "C29") (pin "P$2") (pinfunction "P$2_P$2") (pintype "passive"))
      (node (ref "C3") (pin "2") (pinfunction "2_2") (pintype "passive"))
      (node (ref "C30") (pin "2") (pinfunction "2_2") (pintype "passive"))
      (node (ref "C31") (pin "1") (pinfunction "1_1") (pintype "passive"))
      (node (ref "C32") (pin "1") (pinfunction "1_1") (pintype "passive"))
      (node (ref "C33") (pin "1") (pinfunction "1_1") (pintype "passive"))
      (node (ref "C34") (pin "NEG") (pinfunction "NEG_NEG") (pintype "bidirectional"))
      (node (ref "C35") (pin "2") (pinfunction "2_2") (pintype "passive"))
      (node (ref "C36") (pin "2") (pinfunction "2_2") (pintype "passive"))
      (node (ref "C37") (pin "2") (pinfunction "2_2") (pintype "passive"))
      (node (ref "C38") (pin "2") (pinfunction "2_2") (pintype "passive"))
      (node (ref "C39") (pin "2") (pinfunction "2_2") (pintype "passive"))
      (node (ref "C4") (pin "2") (pinfunction "2_2") (pintype "passive"))
      (node (ref "C40") (pin "2") (pinfunction "2_2") (pintype "passive"))
      (node (ref "C41") (pin "2") (pinfunction "2_2") (pintype "passive"))
      (node (ref "C42") (pin "2") (pinfunction "2_2") (pintype "passive"))
      (node (ref "C43") (pin "2") (pinfunction "2_2") (pintype "passive"))
      (node (ref "C44") (pin "2") (pinfunction "2_2") (pintype "passive"))
      (node (ref "C45") (pin "2") (pinfunction "2_2") (pintype "passive"))
      (node (ref "C46") (pin "1") (pinfunction "1_1") (pintype "passive"))
      (node (ref "C47") (pin "1") (pinfunction "1_1") (pintype "passive"))
      (node (ref "C48") (pin "2") (pinfunction "2_2") (pintype "passive"))
      (node (ref "C49") (pin "NEG") (pinfunction "NEG_NEG") (pintype "bidirectional"))
      (node (ref "C5") (pin "2") (pinfunction "2_2") (pintype "passive"))
      (node (ref "C50") (pin "NEG") (pinfunction "NEG_NEG") (pintype "bidirectional"))
      (node (ref "C51") (pin "2") (pinfunction "2_2") (pintype "passive"))
      (node (ref "C52") (pin "2") (pinfunction "2_2") (pintype "passive"))
      (node (ref "C53") (pin "2") (pinfunction "2_2") (pintype "passive"))
      (node (ref "C54") (pin "1") (pinfunction "1_1") (pintype "passive"))
      (node (ref "C55") (pin "1") (pinfunction "1_1") (pintype "passive"))
      (node (ref "C56") (pin "2") (pinfunction "2_2") (pintype "passive"))
      (node (ref "C57") (pin "2") (pinfunction "2_2") (pintype "passive"))
      (node (ref "C58") (pin "2") (pinfunction "2_2") (pintype "passive"))
      (node (ref "C59") (pin "2") (pinfunction "2_2") (pintype "passive"))
      (node (ref "C6") (pin "2") (pinfunction "2_2") (pintype "passive"))
      (node (ref "C60") (pin "2") (pinfunction "2_2") (pintype "passive"))
      (node (ref "C61") (pin "2") (pinfunction "2_2") (pintype "passive"))
      (node (ref "C62") (pin "2") (pinfunction "2_2") (pintype "passive"))
      (node (ref "C63") (pin "2") (pinfunction "2_2") (pintype "passive"))
      (node (ref "C64") (pin "2") (pinfunction "2_2") (pintype "passive"))
      (node (ref "C65") (pin "2") (pinfunction "2_2") (pintype "passive"))
      (node (ref "C7") (pin "2") (pinfunction "2_2") (pintype "passive"))
      (node (ref "C8") (pin "2") (pinfunction "2_2") (pintype "passive"))
      (node (ref "C9") (pin "2") (pinfunction "2_2") (pintype "passive"))
      (node (ref "CABINET_I/O") (pin "P$1") (pinfunction "1_P$1") (pintype "bidirectional"))
      (node (ref "D1") (pin "1") (pinfunction "CAT_1") (pintype "bidirectional"))
      (node (ref "D3") (pin "ANODE") (pinfunction "ANODE_ANODE") (pintype "bidirectional"))
      (node (ref "D4") (pin "ANODE") (pinfunction "ANODE_ANODE") (pintype "bidirectional"))
      (node (ref "DMD_CON") (pin "10") (pinfunction "PIN10_10") (pintype "bidirectional"))
      (node (ref "DMD_CON") (pin "12") (pinfunction "PIN12_12") (pintype "bidirectional"))
      (node (ref "DMD_CON") (pin "14") (pinfunction "PIN14_14") (pintype "bidirectional"))
      (node (ref "DMD_CON") (pin "2") (pinfunction "PIN2_2") (pintype "bidirectional"))
      (node (ref "DMD_CON") (pin "4") (pinfunction "PIN4_4") (pintype "bidirectional"))
      (node (ref "DMD_CON") (pin "6") (pinfunction "PIN6_6") (pintype "bidirectional"))
      (node (ref "DMD_CON") (pin "8") (pinfunction "PIN8_8") (pintype "bidirectional"))
      (node (ref "DMD_PWR") (pin "4") (pinfunction "PIN3_4") (pintype "bidirectional"))
      (node (ref "FLASHER") (pin "P$2") (pinfunction "PIN2_P$2") (pintype "bidirectional"))
      (node (ref "GI0") (pin "S") (pinfunction "EMITTER_S") (pintype "bidirectional"))
      (node (ref "GI1") (pin "S") (pinfunction "EMITTER_S") (pintype "bidirectional"))
      (node (ref "GI10") (pin "S") (pinfunction "EMITTER_S") (pintype "bidirectional"))
      (node (ref "GI11") (pin "S") (pinfunction "EMITTER_S") (pintype "bidirectional"))
      (node (ref "GI12") (pin "S") (pinfunction "EMITTER_S") (pintype "bidirectional"))
      (node (ref "GI13") (pin "S") (pinfunction "EMITTER_S") (pintype "bidirectional"))
      (node (ref "GI14") (pin "S") (pinfunction "EMITTER_S") (pintype "bidirectional"))
      (node (ref "GI15") (pin "S") (pinfunction "EMITTER_S") (pintype "bidirectional"))
      (node (ref "GI2") (pin "S") (pinfunction "EMITTER_S") (pintype "bidirectional"))
      (node (ref "GI3") (pin "S") (pinfunction "EMITTER_S") (pintype "bidirectional"))
      (node (ref "GI4") (pin "S") (pinfunction "EMITTER_S") (pintype "bidirectional"))
      (node (ref "GI5") (pin "S") (pinfunction "EMITTER_S") (pintype "bidirectional"))
      (node (ref "GI6") (pin "S") (pinfunction "EMITTER_S") (pintype "bidirectional"))
      (node (ref "GI7") (pin "S") (pinfunction "EMITTER_S") (pintype "bidirectional"))
      (node (ref "GI8") (pin "S") (pinfunction "EMITTER_S") (pintype "bidirectional"))
      (node (ref "GI9") (pin "S") (pinfunction "EMITTER_S") (pintype "bidirectional"))
      (node (ref "GND") (pin "P$1") (pinfunction "P$1_P$1") (pintype "bidirectional"))
      (node (ref "IC2") (pin "15") (pinfunction "VSS_15") (pintype "bidirectional"))
      (node (ref "IC2") (pin "31") (pinfunction "AVSS_31") (pintype "bidirectional"))
      (node (ref "IC2") (pin "36") (pinfunction "VSS_36") (pintype "bidirectional"))
      (node (ref "IC2") (pin "45") (pinfunction "VSS_45") (pintype "bidirectional"))
      (node (ref "IC2") (pin "65") (pinfunction "VSS_65") (pintype "bidirectional"))
      (node (ref "IC2") (pin "75") (pinfunction "VSS_75") (pintype "bidirectional"))
      (node (ref "IC3") (pin "1") (pinfunction "G_1") (pintype "input"))
      (node (ref "IC3") (pin "10") (pinfunction "GND_10") (pintype "power_in"))
      (node (ref "IC3") (pin "19") (pinfunction "G_19") (pintype "input"))
      (node (ref "IC4") (pin "1") (pinfunction "G_1") (pintype "input"))
      (node (ref "IC4") (pin "10") (pinfunction "GND_10") (pintype "power_in"))
      (node (ref "IC4") (pin "19") (pinfunction "G_19") (pintype "input"))
      (node (ref "IC5") (pin "9") (pinfunction "GND_9") (pintype "power_in"))
      (node (ref "OPTO_1") (pin "3") (pinfunction "3_3") (pintype "passive"))
      (node (ref "OPTO_2") (pin "3") (pinfunction "3_3") (pintype "passive"))
      (node (ref "OPTO_3") (pin "3") (pinfunction "3_3") (pintype "passive"))
      (node (ref "OPTO_4") (pin "3") (pinfunction "3_3") (pintype "passive"))
      (node (ref "OPTO_5") (pin "3") (pinfunction "3_3") (pintype "passive"))
      (node (ref "OPTO_6") (pin "3") (pinfunction "3_3") (pintype "passive"))
      (node (ref "OPTO_7") (pin "3") (pinfunction "3_3") (pintype "passive"))
      (node (ref "PHABULOUS") (pin "1") (pinfunction "1_1") (pintype "bidirectional"))
      (node (ref "PHABULOUS") (pin "11") (pinfunction "11_11") (pintype "bidirectional"))
      (node (ref "PHABULOUS") (pin "6") (pinfunction "6_6") (pintype "bidirectional"))
      (node (ref "PHABULOUS") (pin "8") (pinfunction "8_8") (pintype "bidirectional"))
      (node (ref "PIC32_TC") (pin "P$5") (pinfunction "PIN5_P$5") (pintype "bidirectional"))
      (node (ref "PIC32_UART") (pin "1") (pinfunction "1_1") (pintype "passive"))
      (node (ref "PICKIT3") (pin "3") (pinfunction "3_3") (pintype "passive"))
      (node (ref "PICKIT3_TC") (pin "P$3") (pinfunction "PIN3_P$3") (pintype "bidirectional"))
      (node (ref "PIC_PROGRAM") (pin "P$4") (pinfunction "P$4_P$4") (pintype "bidirectional"))
      (node (ref "PIC_RESET") (pin "P$1") (pinfunction "P$1_P$1") (pintype "bidirectional"))
      (node (ref "PROP_CONFIG") (pin "P$4") (pinfunction "P$4_P$4") (pintype "bidirectional"))
      (node (ref "PROP_RESET") (pin "P$3") (pinfunction "P$3_P$3") (pintype "bidirectional"))
      (node (ref "PROP_TC") (pin "P$5") (pinfunction "PIN5_P$5") (pintype "bidirectional"))
      (node (ref "PROP_UART") (pin "1") (pinfunction "1_1") (pintype "passive"))
      (node (ref "R11") (pin "1") (pinfunction "1_1") (pintype "passive"))
      (node (ref "R117") (pin "1") (pinfunction "1_1") (pintype "passive"))
      (node (ref "R118") (pin "2") (pinfunction "2_2") (pintype "passive"))
      (node (ref "R133") (pin "2") (pinfunction "2_2") (pintype "passive"))
      (node (ref "R135") (pin "2") (pinfunction "2_2") (pintype "passive"))
      (node (ref "R136") (pin "1") (pinfunction "1_1") (pintype "passive"))
      (node (ref "R146") (pin "2") (pinfunction "2_2") (pintype "passive"))
      (node (ref "R157") (pin "2") (pinfunction "2_2") (pintype "passive"))
      (node (ref "R159") (pin "2") (pinfunction "2_2") (pintype "passive"))
      (node (ref "R160") (pin "2") (pinfunction "2_2") (pintype "passive"))
      (node (ref "R161") (pin "2") (pinfunction "2_2") (pintype "passive"))
      (node (ref "R162") (pin "2") (pinfunction "2_2") (pintype "passive"))
      (node (ref "R2") (pin "1") (pinfunction "1_1") (pintype "passive"))
      (node (ref "R27") (pin "1") (pinfunction "1_1") (pintype "passive"))
      (node (ref "R29") (pin "1") (pinfunction "1_1") (pintype "passive"))
      (node (ref "R30") (pin "1") (pinfunction "1_1") (pintype "passive"))
      (node (ref "R33") (pin "1") (pinfunction "1_1") (pintype "passive"))
      (node (ref "R51") (pin "1") (pinfunction "1_1") (pintype "passive"))
      (node (ref "R52") (pin "1") (pinfunction "1_1") (pintype "passive"))
      (node (ref "R53") (pin "1") (pinfunction "1_1") (pintype "passive"))
      (node (ref "R54") (pin "1") (pinfunction "1_1") (pintype "passive"))
      (node (ref "R55") (pin "1") (pinfunction "1_1") (pintype "passive"))
      (node (ref "R56") (pin "1") (pinfunction "1_1") (pintype "passive"))
      (node (ref "R57") (pin "1") (pinfunction "1_1") (pintype "passive"))
      (node (ref "R58") (pin "1") (pinfunction "1_1") (pintype "passive"))
      (node (ref "R59") (pin "1") (pinfunction "1_1") (pintype "passive"))
      (node (ref "R6") (pin "1") (pinfunction "1_1") (pintype "passive"))
      (node (ref "R60") (pin "1") (pinfunction "1_1") (pintype "passive"))
      (node (ref "R61") (pin "1") (pinfunction "1_1") (pintype "passive"))
      (node (ref "R62") (pin "1") (pinfunction "1_1") (pintype "passive"))
      (node (ref "R63") (pin "1") (pinfunction "1_1") (pintype "passive"))
      (node (ref "R64") (pin "1") (pinfunction "1_1") (pintype "passive"))
      (node (ref "R65") (pin "1") (pinfunction "1_1") (pintype "passive"))
      (node (ref "R66") (pin "1") (pinfunction "1_1") (pintype "passive"))
      (node (ref "R67") (pin "1") (pinfunction "1_1") (pintype "passive"))
      (node (ref "R68") (pin "1") (pinfunction "1_1") (pintype "passive"))
      (node (ref "R69") (pin "1") (pinfunction "1_1") (pintype "passive"))
      (node (ref "R70") (pin "1") (pinfunction "1_1") (pintype "passive"))
      (node (ref "R71") (pin "1") (pinfunction "1_1") (pintype "passive"))
      (node (ref "R72") (pin "1") (pinfunction "1_1") (pintype "passive"))
      (node (ref "R73") (pin "1") (pinfunction "1_1") (pintype "passive"))
      (node (ref "R74") (pin "1") (pinfunction "1_1") (pintype "passive"))
      (node (ref "R9") (pin "1") (pinfunction "1_1") (pintype "passive"))
      (node (ref "RGB_0") (pin "S") (pinfunction "SOURCE_S") (pintype "bidirectional"))
      (node (ref "RGB_1") (pin "S") (pinfunction "SOURCE_S") (pintype "bidirectional"))
      (node (ref "RGB_2") (pin "S") (pinfunction "SOURCE_S") (pintype "bidirectional"))
      (node (ref "RGB_3") (pin "S") (pinfunction "SOURCE_S") (pintype "bidirectional"))
      (node (ref "RGB_4") (pin "S") (pinfunction "SOURCE_S") (pintype "bidirectional"))
      (node (ref "RGB_5") (pin "S") (pinfunction "SOURCE_S") (pintype "bidirectional"))
      (node (ref "RGB_COM_OUT") (pin "P$1") (pinfunction "1_P$1") (pintype "bidirectional"))
      (node (ref "SD0") (pin "3") (pinfunction "GND_3") (pintype "bidirectional"))
      (node (ref "SD0") (pin "6") (pinfunction "GND_6") (pintype "bidirectional"))
      (node (ref "SD0") (pin "GND_1") (pinfunction "GND_GND_1") (pintype "bidirectional"))
      (node (ref "SD0") (pin "GND_2") (pinfunction "GND_GND_2") (pintype "bidirectional"))
      (node (ref "SERVO_0") (pin "P$1") (pinfunction "PIN1_P$1") (pintype "bidirectional"))
      (node (ref "SERVO_1") (pin "P$1") (pinfunction "PIN1_P$1") (pintype "bidirectional"))
      (node (ref "SERVO_2") (pin "P$1") (pinfunction "PIN1_P$1") (pintype "bidirectional"))
      (node (ref "SERVO_3") (pin "P$1") (pinfunction "PIN1_P$1") (pintype "bidirectional"))
      (node (ref "SERVO_4") (pin "P$1") (pinfunction "PIN1_P$1") (pintype "bidirectional"))
      (node (ref "U1") (pin "17") (pinfunction "VSS_17") (pintype "bidirectional"))
      (node (ref "U1") (pin "27") (pinfunction "VSS_27") (pintype "bidirectional"))
      (node (ref "U1") (pin "39") (pinfunction "VSS_39") (pintype "bidirectional"))
      (node (ref "U1") (pin "5") (pinfunction "VSS_5") (pintype "bidirectional"))
      (node (ref "U1") (pin "6") (pinfunction "~{BOE}_6") (pintype "bidirectional"))
      (node (ref "U10") (pin "2") (pinfunction "GND_2") (pintype "bidirectional"))
      (node (ref "U11") (pin "15") (pinfunction "C_INH_15") (pintype "bidirectional"))
      (node (ref "U11") (pin "8") (pinfunction "GND_8") (pintype "bidirectional"))
      (node (ref "U12") (pin "15") (pinfunction "C_INH_15") (pintype "bidirectional"))
      (node (ref "U12") (pin "8") (pinfunction "GND_8") (pintype "bidirectional"))
      (node (ref "U13") (pin "2") (pinfunction "A1_2") (pintype "bidirectional"))
      (node (ref "U13") (pin "3") (pinfunction "A2_3") (pintype "bidirectional"))
      (node (ref "U13") (pin "4") (pinfunction "GND_4") (pintype "bidirectional"))
      (node (ref "U13") (pin "7") (pinfunction "WP_7") (pintype "bidirectional"))
      (node (ref "U14") (pin "7") (pinfunction "GND_7") (pintype "bidirectional"))
      (node (ref "U15") (pin "7") (pinfunction "GND_7") (pintype "bidirectional"))
      (node (ref "U16") (pin "7") (pinfunction "GND_7") (pintype "bidirectional"))
      (node (ref "U17") (pin "7") (pinfunction "GND_7") (pintype "bidirectional"))
      (node (ref "U18") (pin "7") (pinfunction "GND_7") (pintype "bidirectional"))
      (node (ref "U19") (pin "7") (pinfunction "GND_7") (pintype "bidirectional"))
      (node (ref "U2") (pin "4") (pinfunction "VSS_4") (pintype "bidirectional"))
      (node (ref "U28") (pin "S") (pinfunction "EMITTER_S") (pintype "bidirectional"))
      (node (ref "U29") (pin "S") (pinfunction "EMITTER_S") (pintype "bidirectional"))
      (node (ref "U3") (pin "13") (pinfunction "OE_13") (pintype "bidirectional"))
      (node (ref "U3") (pin "8") (pinfunction "GND_8") (pintype "bidirectional"))
      (node (ref "U30") (pin "S") (pinfunction "EMITTER_S") (pintype "bidirectional"))
      (node (ref "U31") (pin "S") (pinfunction "EMITTER_S") (pintype "bidirectional"))
      (node (ref "U32") (pin "S") (pinfunction "EMITTER_S") (pintype "bidirectional"))
      (node (ref "U33") (pin "S") (pinfunction "EMITTER_S") (pintype "bidirectional"))
      (node (ref "U34") (pin "S") (pinfunction "EMITTER_S") (pintype "bidirectional"))
      (node (ref "U35") (pin "S") (pinfunction "EMITTER_S") (pintype "bidirectional"))
      (node (ref "U36") (pin "3") (pinfunction "POL_3") (pintype "bidirectional"))
      (node (ref "U36") (pin "4") (pinfunction "RFB_4") (pintype "bidirectional"))
      (node (ref "U36") (pin "5") (pinfunction "GFB_5") (pintype "bidirectional"))
      (node (ref "U36") (pin "6") (pinfunction "BFB_6") (pintype "bidirectional"))
      (node (ref "U36") (pin "7") (pinfunction "GND_7") (pintype "bidirectional"))
      (node (ref "U38") (pin "3") (pinfunction "POL_3") (pintype "bidirectional"))
      (node (ref "U38") (pin "4") (pinfunction "RFB_4") (pintype "bidirectional"))
      (node (ref "U38") (pin "5") (pinfunction "GFB_5") (pintype "bidirectional"))
      (node (ref "U38") (pin "6") (pinfunction "BFB_6") (pintype "bidirectional"))
      (node (ref "U38") (pin "7") (pinfunction "GND_7") (pintype "bidirectional"))
      (node (ref "U39") (pin "1") (pinfunction "GND_1") (pintype "bidirectional"))
      (node (ref "U4") (pin "2") (pinfunction "A1_2") (pintype "bidirectional"))
      (node (ref "U4") (pin "3") (pinfunction "A2_3") (pintype "bidirectional"))
      (node (ref "U4") (pin "4") (pinfunction "GND_4") (pintype "bidirectional"))
      (node (ref "U4") (pin "7") (pinfunction "WP_7") (pintype "bidirectional"))
      (node (ref "U5") (pin "13") (pinfunction "OE_13") (pintype "bidirectional"))
      (node (ref "U5") (pin "8") (pinfunction "GND_8") (pintype "bidirectional"))
      (node (ref "U52") (pin "14") (pinfunction "1CX_14") (pintype "bidirectional"))
      (node (ref "U52") (pin "8") (pinfunction "GND_8") (pintype "bidirectional"))
      (node (ref "U6") (pin "P$9") (pinfunction "GND_P$9") (pintype "bidirectional"))
      (node (ref "U6") (pin "PAD") (pinfunction "GND_PAD") (pintype "bidirectional"))
      (node (ref "U6") (pin "PAD2") (pinfunction "GND_PAD2") (pintype "bidirectional"))
      (node (ref "U6") (pin "PAD3") (pinfunction "GND_PAD3") (pintype "bidirectional"))
      (node (ref "U6") (pin "PAD4") (pinfunction "GND_PAD4") (pintype "bidirectional"))
      (node (ref "U6") (pin "PAD5") (pinfunction "GND_PAD5") (pintype "bidirectional"))
      (node (ref "U6") (pin "PAD6") (pinfunction "GND_PAD6") (pintype "bidirectional"))
      (node (ref "U6") (pin "PAD7") (pinfunction "GND_PAD7") (pintype "bidirectional"))
      (node (ref "U7") (pin "P$9") (pinfunction "GND_P$9") (pintype "bidirectional"))
      (node (ref "U7") (pin "PAD") (pinfunction "GND_PAD") (pintype "bidirectional"))
      (node (ref "U7") (pin "PAD2") (pinfunction "GND_PAD2") (pintype "bidirectional"))
      (node (ref "U7") (pin "PAD3") (pinfunction "GND_PAD3") (pintype "bidirectional"))
      (node (ref "U7") (pin "PAD4") (pinfunction "GND_PAD4") (pintype "bidirectional"))
      (node (ref "U7") (pin "PAD5") (pinfunction "GND_PAD5") (pintype "bidirectional"))
      (node (ref "U7") (pin "PAD6") (pinfunction "GND_PAD6") (pintype "bidirectional"))
      (node (ref "U7") (pin "PAD7") (pinfunction "GND_PAD7") (pintype "bidirectional"))
      (node (ref "U8") (pin "P$2") (pinfunction "EMITTER_P$2") (pintype "bidirectional"))
      (node (ref "USB_PROG") (pin "4") (pinfunction "4_4") (pintype "passive"))
    )
    (net (code "83") (name "/I2C_SCL") (class "Default")
      (node (ref "IC2") (pin "66") (pinfunction "AETXCLK/SCL1/INT3/RA14_66") (pintype "bidirectional"))
      (node (ref "PHABULOUS") (pin "5") (pinfunction "5_5") (pintype "bidirectional"))
      (node (ref "R24") (pin "1") (pinfunction "1_1") (pintype "passive"))
      (node (ref "U13") (pin "6") (pinfunction "SCL_6") (pintype "bidirectional"))
      (node (ref "U2") (pin "6") (pinfunction "SCL_6") (pintype "bidirectional"))
    )
    (net (code "84") (name "/I2C_SDA") (class "Default")
      (node (ref "IC2") (pin "67") (pinfunction "AETXEN/SDA1/INT4/RA15_67") (pintype "bidirectional"))
      (node (ref "PHABULOUS") (pin "4") (pinfunction "4_4") (pintype "bidirectional"))
      (node (ref "R25") (pin "1") (pinfunction "1_1") (pintype "passive"))
      (node (ref "U13") (pin "5") (pinfunction "SDA_5") (pintype "bidirectional"))
      (node (ref "U2") (pin "5") (pinfunction "SDA_5") (pintype "bidirectional"))
    )
    (net (code "85") (name "/LIGHT_C_0") (class "Default")
      (node (ref "LIGHT_COL") (pin "P$3") (pinfunction "PIN2_P$3") (pintype "bidirectional"))
      (node (ref "LIGHT_C_0") (pin "P$1") (pinfunction "P$1_P$1") (pintype "bidirectional"))
      (node (ref "U20") (pin "D") (pinfunction "COLLECTOR_D") (pintype "bidirectional"))
    )
    (net (code "86") (name "/LIGHT_C_1") (class "Default")
      (node (ref "LIGHT_COL") (pin "P$4") (pinfunction "PIN3_P$4") (pintype "bidirectional"))
      (node (ref "LIGHT_C_1") (pin "P$1") (pinfunction "P$1_P$1") (pintype "bidirectional"))
      (node (ref "U21") (pin "D") (pinfunction "COLLECTOR_D") (pintype "bidirectional"))
    )
    (net (code "87") (name "/LIGHT_C_2") (class "Default")
      (node (ref "LIGHT_COL") (pin "P$5") (pinfunction "PIN4_P$5") (pintype "bidirectional"))
      (node (ref "LIGHT_C_2") (pin "P$1") (pinfunction "P$1_P$1") (pintype "bidirectional"))
      (node (ref "U22") (pin "D") (pinfunction "COLLECTOR_D") (pintype "bidirectional"))
    )
    (net (code "88") (name "/LIGHT_C_3") (class "Default")
      (node (ref "LIGHT_COL") (pin "P$6") (pinfunction "PIN5_P$6") (pintype "bidirectional"))
      (node (ref "LIGHT_C_3") (pin "P$1") (pinfunction "P$1_P$1") (pintype "bidirectional"))
      (node (ref "U23") (pin "D") (pinfunction "COLLECTOR_D") (pintype "bidirectional"))
    )
    (net (code "89") (name "/LIGHT_C_4") (class "Default")
      (node (ref "LIGHT_COL") (pin "P$7") (pinfunction "PIN6_P$7") (pintype "bidirectional"))
      (node (ref "LIGHT_C_4") (pin "P$1") (pinfunction "P$1_P$1") (pintype "bidirectional"))
      (node (ref "U24") (pin "D") (pinfunction "COLLECTOR_D") (pintype "bidirectional"))
    )
    (net (code "90") (name "/LIGHT_C_5") (class "Default")
      (node (ref "LIGHT_COL") (pin "P$8") (pinfunction "PIN7_P$8") (pintype "bidirectional"))
      (node (ref "LIGHT_C_5") (pin "P$1") (pinfunction "P$1_P$1") (pintype "bidirectional"))
      (node (ref "U25") (pin "D") (pinfunction "COLLECTOR_D") (pintype "bidirectional"))
    )
    (net (code "91") (name "/LIGHT_C_6") (class "Default")
      (node (ref "LIGHT_COL") (pin "P$9") (pinfunction "PIN8_P$9") (pintype "bidirectional"))
      (node (ref "LIGHT_C_6") (pin "P$1") (pinfunction "P$1_P$1") (pintype "bidirectional"))
      (node (ref "U26") (pin "D") (pinfunction "COLLECTOR_D") (pintype "bidirectional"))
    )
    (net (code "92") (name "/LIGHT_C_7") (class "Default")
      (node (ref "LIGHT_COL") (pin "P$10") (pinfunction "PIN9_P$10") (pintype "bidirectional"))
      (node (ref "LIGHT_C_7") (pin "P$1") (pinfunction "P$1_P$1") (pintype "bidirectional"))
      (node (ref "U27") (pin "D") (pinfunction "COLLECTOR_D") (pintype "bidirectional"))
    )
    (net (code "93") (name "/LIGHT_C_B_0") (class "Default")
      (node (ref "R83") (pin "2") (pinfunction "2_2") (pintype "passive"))
      (node (ref "R84") (pin "2") (pinfunction "2_2") (pintype "passive"))
      (node (ref "U20") (pin "G") (pinfunction "BASE_G") (pintype "bidirectional"))
    )
    (net (code "94") (name "/LIGHT_C_B_1") (class "Default")
      (node (ref "R85") (pin "2") (pinfunction "2_2") (pintype "passive"))
      (node (ref "R86") (pin "2") (pinfunction "2_2") (pintype "passive"))
      (node (ref "U21") (pin "G") (pinfunction "BASE_G") (pintype "bidirectional"))
    )
    (net (code "95") (name "/LIGHT_C_B_2") (class "Default")
      (node (ref "R87") (pin "2") (pinfunction "2_2") (pintype "passive"))
      (node (ref "R88") (pin "2") (pinfunction "2_2") (pintype "passive"))
      (node (ref "U22") (pin "G") (pinfunction "BASE_G") (pintype "bidirectional"))
    )
    (net (code "96") (name "/LIGHT_C_B_3") (class "Default")
      (node (ref "R89") (pin "2") (pinfunction "2_2") (pintype "passive"))
      (node (ref "R90") (pin "2") (pinfunction "2_2") (pintype "passive"))
      (node (ref "U23") (pin "G") (pinfunction "BASE_G") (pintype "bidirectional"))
    )
    (net (code "97") (name "/LIGHT_C_B_4") (class "Default")
      (node (ref "R91") (pin "2") (pinfunction "2_2") (pintype "passive"))
      (node (ref "R92") (pin "2") (pinfunction "2_2") (pintype "passive"))
      (node (ref "U24") (pin "G") (pinfunction "BASE_G") (pintype "bidirectional"))
    )
    (net (code "98") (name "/LIGHT_C_B_5") (class "Default")
      (node (ref "R93") (pin "2") (pinfunction "2_2") (pintype "passive"))
      (node (ref "R94") (pin "2") (pinfunction "2_2") (pintype "passive"))
      (node (ref "U25") (pin "G") (pinfunction "BASE_G") (pintype "bidirectional"))
    )
    (net (code "99") (name "/LIGHT_C_B_6") (class "Default")
      (node (ref "R95") (pin "2") (pinfunction "2_2") (pintype "passive"))
      (node (ref "R96") (pin "2") (pinfunction "2_2") (pintype "passive"))
      (node (ref "U26") (pin "G") (pinfunction "BASE_G") (pintype "bidirectional"))
    )
    (net (code "100") (name "/LIGHT_C_B_7") (class "Default")
      (node (ref "R97") (pin "2") (pinfunction "2_2") (pintype "passive"))
      (node (ref "R98") (pin "2") (pinfunction "2_2") (pintype "passive"))
      (node (ref "U27") (pin "G") (pinfunction "BASE_G") (pintype "bidirectional"))
    )
    (net (code "101") (name "/LIGHT_DTA_0") (class "Default")
      (node (ref "IC5") (pin "11") (pinfunction "O8_11") (pintype "open_collector"))
      (node (ref "R84") (pin "1") (pinfunction "1_1") (pintype "passive"))
    )
    (net (code "102") (name "/LIGHT_DTA_1") (class "Default")
      (node (ref "IC5") (pin "12") (pinfunction "O7_12") (pintype "open_collector"))
      (node (ref "R86") (pin "1") (pinfunction "1_1") (pintype "passive"))
    )
    (net (code "103") (name "/LIGHT_DTA_2") (class "Default")
      (node (ref "IC5") (pin "13") (pinfunction "O6_13") (pintype "open_collector"))
      (node (ref "R88") (pin "1") (pinfunction "1_1") (pintype "passive"))
    )
    (net (code "104") (name "/LIGHT_DTA_3") (class "Default")
      (node (ref "IC5") (pin "14") (pinfunction "O5_14") (pintype "open_collector"))
      (node (ref "R90") (pin "1") (pinfunction "1_1") (pintype "passive"))
    )
    (net (code "105") (name "/LIGHT_DTA_4") (class "Default")
      (node (ref "IC5") (pin "15") (pinfunction "O4_15") (pintype "open_collector"))
      (node (ref "R92") (pin "1") (pinfunction "1_1") (pintype "passive"))
    )
    (net (code "106") (name "/LIGHT_DTA_5") (class "Default")
      (node (ref "IC5") (pin "16") (pinfunction "O3_16") (pintype "open_collector"))
      (node (ref "R94") (pin "1") (pinfunction "1_1") (pintype "passive"))
    )
    (net (code "107") (name "/LIGHT_DTA_6") (class "Default")
      (node (ref "IC5") (pin "17") (pinfunction "O2_17") (pintype "open_collector"))
      (node (ref "R96") (pin "1") (pinfunction "1_1") (pintype "passive"))
    )
    (net (code "108") (name "/LIGHT_DTA_7") (class "Default")
      (node (ref "IC5") (pin "18") (pinfunction "O1_18") (pintype "open_collector"))
      (node (ref "R98") (pin "1") (pinfunction "1_1") (pintype "passive"))
    )
    (net (code "109") (name "/LIGHT_R_0") (class "Default")
      (node (ref "LIGHT_ROW") (pin "P$2") (pinfunction "PIN2_P$2") (pintype "bidirectional"))
      (node (ref "LIGHT_R_0") (pin "P$1") (pinfunction "P$1_P$1") (pintype "bidirectional"))
      (node (ref "U28") (pin "D") (pinfunction "COLLECTOR_D") (pintype "bidirectional"))
    )
    (net (code "110") (name "/LIGHT_R_1") (class "Default")
      (node (ref "LIGHT_ROW") (pin "P$4") (pinfunction "PIN3_P$4") (pintype "bidirectional"))
      (node (ref "LIGHT_R_1") (pin "P$1") (pinfunction "P$1_P$1") (pintype "bidirectional"))
      (node (ref "U29") (pin "D") (pinfunction "COLLECTOR_D") (pintype "bidirectional"))
    )
    (net (code "111") (name "/LIGHT_R_2") (class "Default")
      (node (ref "LIGHT_ROW") (pin "P$5") (pinfunction "PIN4_P$5") (pintype "bidirectional"))
      (node (ref "LIGHT_R_2") (pin "P$1") (pinfunction "P$1_P$1") (pintype "bidirectional"))
      (node (ref "U30") (pin "D") (pinfunction "COLLECTOR_D") (pintype "bidirectional"))
    )
    (net (code "112") (name "/LIGHT_R_3") (class "Default")
      (node (ref "LIGHT_ROW") (pin "P$6") (pinfunction "PIN5_P$6") (pintype "bidirectional"))
      (node (ref "LIGHT_R_3") (pin "P$1") (pinfunction "P$1_P$1") (pintype "bidirectional"))
      (node (ref "U31") (pin "D") (pinfunction "COLLECTOR_D") (pintype "bidirectional"))
    )
    (net (code "113") (name "/LIGHT_R_4") (class "Default")
      (node (ref "LIGHT_ROW") (pin "P$7") (pinfunction "PIN6_P$7") (pintype "bidirectional"))
      (node (ref "LIGHT_R_4") (pin "P$1") (pinfunction "P$1_P$1") (pintype "bidirectional"))
      (node (ref "U32") (pin "D") (pinfunction "COLLECTOR_D") (pintype "bidirectional"))
    )
    (net (code "114") (name "/LIGHT_R_5") (class "Default")
      (node (ref "LIGHT_ROW") (pin "P$8") (pinfunction "PIN7_P$8") (pintype "bidirectional"))
      (node (ref "LIGHT_R_5") (pin "P$1") (pinfunction "P$1_P$1") (pintype "bidirectional"))
      (node (ref "U33") (pin "D") (pinfunction "COLLECTOR_D") (pintype "bidirectional"))
    )
    (net (code "115") (name "/LIGHT_R_6") (class "Default")
      (node (ref "LIGHT_ROW") (pin "P$9") (pinfunction "PIN8_P$9") (pintype "bidirectional"))
      (node (ref "LIGHT_R_6") (pin "P$1") (pinfunction "P$1_P$1") (pintype "bidirectional"))
      (node (ref "U34") (pin "D") (pinfunction "COLLECTOR_D") (pintype "bidirectional"))
    )
    (net (code "116") (name "/LIGHT_R_7") (class "Default")
      (node (ref "LIGHT_ROW") (pin "P$10") (pinfunction "PIN9_P$10") (pintype "bidirectional"))
      (node (ref "LIGHT_R_7") (pin "P$1") (pinfunction "P$1_P$1") (pintype "bidirectional"))
      (node (ref "U35") (pin "D") (pinfunction "COLLECTOR_D") (pintype "bidirectional"))
    )
    (net (code "117") (name "/L_FLIP") (class "Default")
      (node (ref "R156") (pin "2") (pinfunction "2_2") (pintype "passive"))
      (node (ref "R46") (pin "1") (pinfunction "1_1") (pintype "passive"))
      (node (ref "U12") (pin "14") (pinfunction "D3_14") (pintype "bidirectional"))
    )
    (net (code "118") (name "/L_FLIP_OUT") (class "Default")
      (node (ref "CABINET_I/O") (pin "P$12") (pinfunction "12_P$12") (pintype "bidirectional"))
      (node (ref "L_FLIP_OUT") (pin "P$1") (pinfunction "P$1_P$1") (pintype "bidirectional"))
      (node (ref "R156") (pin "1") (pinfunction "1_1") (pintype "passive"))
    )
    (net (code "119") (name "/N$31") (class "Default")
      (node (ref "PICKIT3") (pin "4") (pinfunction "4_4") (pintype "passive"))
      (node (ref "PICKIT3_TC") (pin "P$4") (pinfunction "PIN4_P$4") (pintype "bidirectional"))
      (node (ref "R13") (pin "2") (pinfunction "2_2") (pintype "passive"))
    )
    (net (code "120") (name "/N$33") (class "Default")
      (node (ref "PICKIT3") (pin "5") (pinfunction "5_5") (pintype "passive"))
      (node (ref "PICKIT3_TC") (pin "P$5") (pinfunction "PIN5_P$5") (pintype "bidirectional"))
      (node (ref "R14") (pin "2") (pinfunction "2_2") (pintype "passive"))
    )
    (net (code "121") (name "/N$44") (class "Default")
      (node (ref "PHABULOUS") (pin "20") (pinfunction "20_20") (pintype "bidirectional"))
    )
    (net (code "122") (name "/OPTO_1") (class "Default")
      (node (ref "OPTO_1") (pin "1") (pinfunction "1_1") (pintype "passive"))
      (node (ref "OPTO_1_") (pin "P$1") (pinfunction "P$1_P$1") (pintype "bidirectional"))
      (node (ref "R2") (pin "2") (pinfunction "2_2") (pintype "passive"))
      (node (ref "R5") (pin "2") (pinfunction "2_2") (pintype "passive"))
    )
    (net (code "123") (name "/OPTO_2") (class "Default")
      (node (ref "OPTO_2") (pin "1") (pinfunction "1_1") (pintype "passive"))
      (node (ref "OPTO_2_") (pin "P$1") (pinfunction "P$1_P$1") (pintype "bidirectional"))
      (node (ref "R6") (pin "2") (pinfunction "2_2") (pintype "passive"))
      (node (ref "R7") (pin "2") (pinfunction "2_2") (pintype "passive"))
    )
    (net (code "124") (name "/OPTO_3") (class "Default")
      (node (ref "OPTO_3") (pin "1") (pinfunction "1_1") (pintype "passive"))
      (node (ref "OPTO_3_") (pin "P$1") (pinfunction "P$1_P$1") (pintype "bidirectional"))
      (node (ref "R10") (pin "2") (pinfunction "2_2") (pintype "passive"))
      (node (ref "R9") (pin "2") (pinfunction "2_2") (pintype "passive"))
    )
    (net (code "125") (name "/OPTO_4") (class "Default")
      (node (ref "OPTO_4") (pin "1") (pinfunction "1_1") (pintype "passive"))
      (node (ref "OPTO_4_") (pin "P$1") (pinfunction "P$1_P$1") (pintype "bidirectional"))
      (node (ref "R11") (pin "2") (pinfunction "2_2") (pintype "passive"))
      (node (ref "R15") (pin "2") (pinfunction "2_2") (pintype "passive"))
    )
    (net (code "126") (name "/OPTO_5") (class "Default")
      (node (ref "OPTO_5") (pin "1") (pinfunction "1_1") (pintype "passive"))
      (node (ref "OPTO_5_") (pin "P$1") (pinfunction "P$1_P$1") (pintype "bidirectional"))
      (node (ref "R27") (pin "2") (pinfunction "2_2") (pintype "passive"))
      (node (ref "R28") (pin "2") (pinfunction "2_2") (pintype "passive"))
    )
    (net (code "127") (name "/OPTO_6") (class "Default")
      (node (ref "OPTO_6") (pin "1") (pinfunction "1_1") (pintype "passive"))
      (node (ref "OPTO_6_") (pin "P$1") (pinfunction "P$1_P$1") (pintype "bidirectional"))
      (node (ref "R29") (pin "2") (pinfunction "2_2") (pintype "passive"))
      (node (ref "R31") (pin "2") (pinfunction "2_2") (pintype "passive"))
    )
    (net (code "128") (name "/OPTO_7") (class "Default")
      (node (ref "OPTO_7") (pin "1") (pinfunction "1_1") (pintype "passive"))
      (node (ref "OPTO_7_") (pin "P$1") (pinfunction "P$1_P$1") (pintype "bidirectional"))
      (node (ref "R138") (pin "2") (pinfunction "2_2") (pintype "passive"))
      (node (ref "R33") (pin "2") (pinfunction "2_2") (pintype "passive"))
    )
    (net (code "129") (name "/P32_MCLR") (class "Default")
      (node (ref "PICKIT3") (pin "1") (pinfunction "1_1") (pintype "passive"))
      (node (ref "PICKIT3_TC") (pin "P$1") (pinfunction "PIN1_P$1") (pintype "bidirectional"))
      (node (ref "R12") (pin "2") (pinfunction "2_2") (pintype "passive"))
      (node (ref "R26") (pin "2") (pinfunction "2_2") (pintype "passive"))
      (node (ref "R4") (pin "1") (pinfunction "1_1") (pintype "passive"))
      (node (ref "R8") (pin "2") (pinfunction "2_2") (pintype "passive"))
    )
    (net (code "130") (name "/PIC_ENABLE") (class "Default")
      (node (ref "IC2") (pin "1") (pinfunction "AERXERR/RG15_1") (pintype "bidirectional"))
      (node (ref "R133") (pin "1") (pinfunction "1_1") (pintype "passive"))
      (node (ref "U52") (pin "1") (pinfunction "~{1A}_1") (pintype "bidirectional"))
    )
    (net (code "131") (name "/PIC_LIGHT_C_0") (class "Default")
      (node (ref "IC2") (pin "25") (pinfunction "PGED1/AN0/CN2/RB0_25") (pintype "bidirectional"))
      (node (ref "IC5") (pin "8") (pinfunction "I8_8") (pintype "input"))
    )
    (net (code "132") (name "/PIC_LIGHT_C_1") (class "Default")
      (node (ref "IC2") (pin "24") (pinfunction "PGEC1/AN1/CN3/RB1_24") (pintype "bidirectional"))
      (node (ref "IC5") (pin "7") (pinfunction "I7_7") (pintype "input"))
    )
    (net (code "133") (name "/PIC_LIGHT_C_2") (class "Default")
      (node (ref "IC2") (pin "23") (pinfunction "AN2/C2IN-/CN4/RB2_23") (pintype "bidirectional"))
      (node (ref "IC5") (pin "6") (pinfunction "I6_6") (pintype "input"))
    )
    (net (code "134") (name "/PIC_LIGHT_C_3") (class "Default")
      (node (ref "IC2") (pin "22") (pinfunction "AN3/C2IN+/CN5/RB3_22") (pintype "bidirectional"))
      (node (ref "IC5") (pin "5") (pinfunction "I5_5") (pintype "input"))
    )
    (net (code "135") (name "/PIC_LIGHT_C_4") (class "Default")
      (node (ref "IC2") (pin "21") (pinfunction "AN4/C1IN-/CN6/RB4_21") (pintype "bidirectional"))
      (node (ref "IC5") (pin "4") (pinfunction "I4_4") (pintype "input"))
    )
    (net (code "136") (name "/PIC_LIGHT_C_5") (class "Default")
      (node (ref "IC2") (pin "20") (pinfunction "AN5/C1IN+/VBUSON/CN7/RB5_20") (pintype "bidirectional"))
      (node (ref "IC5") (pin "3") (pinfunction "I3_3") (pintype "input"))
    )
    (net (code "137") (name "/PIC_LIGHT_C_6") (class "Default")
      (node (ref "IC2") (pin "26") (pinfunction "PGEC2/AN6/OCFA/RB6_26") (pintype "bidirectional"))
      (node (ref "IC5") (pin "2") (pinfunction "I2_2") (pintype "input"))
      (node (ref "R14") (pin "1") (pinfunction "1_1") (pintype "passive"))
    )
    (net (code "138") (name "/PIC_LIGHT_C_7") (class "Default")
      (node (ref "IC2") (pin "27") (pinfunction "PGED2/AN7/RB7_27") (pintype "bidirectional"))
      (node (ref "IC5") (pin "1") (pinfunction "I1_1") (pintype "input"))
      (node (ref "R13") (pin "1") (pinfunction "1_1") (pintype "passive"))
    )
    (net (code "139") (name "/PIC_LIGHT_R_0") (class "Default")
      (node (ref "IC2") (pin "32") (pinfunction "AN8/C1OUT/RB8_32") (pintype "bidirectional"))
      (node (ref "R100") (pin "1") (pinfunction "1_1") (pintype "passive"))
    )
    (net (code "140") (name "/PIC_LIGHT_R_1") (class "Default")
      (node (ref "IC2") (pin "33") (pinfunction "AN9/C2OUT/RB9_33") (pintype "bidirectional"))
      (node (ref "R102") (pin "1") (pinfunction "1_1") (pintype "passive"))
    )
    (net (code "141") (name "/PIC_LIGHT_R_2") (class "Default")
      (node (ref "IC2") (pin "34") (pinfunction "AN10/CVREFOUT/PMA13/RB10_34") (pintype "bidirectional"))
      (node (ref "R104") (pin "1") (pinfunction "1_1") (pintype "passive"))
    )
    (net (code "142") (name "/PIC_LIGHT_R_3") (class "Default")
      (node (ref "IC2") (pin "35") (pinfunction "AN11/ERXERR/AETXERR/PMA12/RB11_35") (pintype "bidirectional"))
      (node (ref "R106") (pin "1") (pinfunction "1_1") (pintype "passive"))
    )
    (net (code "143") (name "/PIC_LIGHT_R_4") (class "Default")
      (node (ref "IC2") (pin "41") (pinfunction "AN12/ERXD0/AECRS/PMA11/RB12_41") (pintype "bidirectional"))
      (node (ref "R108") (pin "1") (pinfunction "1_1") (pintype "passive"))
    )
    (net (code "144") (name "/PIC_LIGHT_R_5") (class "Default")
      (node (ref "IC2") (pin "42") (pinfunction "AN13/ERXD1/AECOL/PMA10/RB13_42") (pintype "bidirectional"))
      (node (ref "R110") (pin "1") (pinfunction "1_1") (pintype "passive"))
    )
    (net (code "145") (name "/PIC_LIGHT_R_6") (class "Default")
      (node (ref "IC2") (pin "43") (pinfunction "AN14/ERXD2/AETXD3/PMALH/PMA1/RB14_43") (pintype "bidirectional"))
      (node (ref "R112") (pin "1") (pinfunction "1_1") (pintype "passive"))
    )
    (net (code "146") (name "/PIC_LIGHT_R_7") (class "Default")
      (node (ref "IC2") (pin "44") (pinfunction "OCFB/PMALL/PMA0/CN12/RB15_44") (pintype "bidirectional"))
      (node (ref "R114") (pin "1") (pinfunction "1_1") (pintype "passive"))
    )
    (net (code "147") (name "/PIC_PROGRAM_SW") (class "Default")
      (node (ref "IC2") (pin "14") (pinfunction "SS2A/U2BRX/U2ACTS/PMA2/CN11/RG9_14") (pintype "bidirectional"))
      (node (ref "PIC_PROGRAM") (pin "P$1") (pinfunction "P$1_P$1") (pintype "bidirectional"))
      (node (ref "R137") (pin "1") (pinfunction "1_1") (pintype "passive"))
    )
    (net (code "148") (name "/PIC_SOL_0") (class "Default")
      (node (ref "IC2") (pin "7") (pinfunction "T3CK/AC2TX/RC2_7") (pintype "bidirectional"))
      (node (ref "R58") (pin "2") (pinfunction "2_2") (pintype "passive"))
      (node (ref "U14") (pin "2") (pinfunction "B1_2") (pintype "bidirectional"))
    )
    (net (code "149") (name "/PIC_SOL_1") (class "Default")
      (node (ref "IC2") (pin "8") (pinfunction "T4CK/AC2RX/RC3_8") (pintype "bidirectional"))
      (node (ref "R57") (pin "2") (pinfunction "2_2") (pintype "passive"))
      (node (ref "U14") (pin "5") (pinfunction "B2_5") (pintype "bidirectional"))
    )
    (net (code "150") (name "/PIC_SOL_2") (class "Default")
      (node (ref "IC2") (pin "3") (pinfunction "PMD5/RE5_3") (pintype "bidirectional"))
      (node (ref "R56") (pin "2") (pinfunction "2_2") (pintype "passive"))
      (node (ref "U14") (pin "10") (pinfunction "B3_10") (pintype "bidirectional"))
    )
    (net (code "151") (name "/PIC_SOL_3") (class "Default")
      (node (ref "IC2") (pin "51") (pinfunction "USBID/RF3_51") (pintype "bidirectional"))
      (node (ref "R55") (pin "2") (pinfunction "2_2") (pintype "passive"))
      (node (ref "U14") (pin "13") (pinfunction "B4_13") (pintype "bidirectional"))
    )
    (net (code "152") (name "/PIC_SOL_4") (class "Default")
      (node (ref "IC2") (pin "4") (pinfunction "PMD6/RE6_4") (pintype "bidirectional"))
      (node (ref "R54") (pin "2") (pinfunction "2_2") (pintype "passive"))
      (node (ref "U17") (pin "2") (pinfunction "B1_2") (pintype "bidirectional"))
    )
    (net (code "153") (name "/PIC_SOL_5") (class "Default")
      (node (ref "IC2") (pin "5") (pinfunction "PMD7/RE7_5") (pintype "bidirectional"))
      (node (ref "R53") (pin "2") (pinfunction "2_2") (pintype "passive"))
      (node (ref "U17") (pin "5") (pinfunction "B2_5") (pintype "bidirectional"))
    )
    (net (code "154") (name "/PIC_SOL_6") (class "Default")
      (node (ref "IC2") (pin "18") (pinfunction "AERXD0/INT1/RE8_18") (pintype "bidirectional"))
      (node (ref "R52") (pin "2") (pinfunction "2_2") (pintype "passive"))
      (node (ref "U17") (pin "10") (pinfunction "B3_10") (pintype "bidirectional"))
    )
    (net (code "155") (name "/PIC_SOL_7") (class "Default")
      (node (ref "IC2") (pin "74") (pinfunction "SOSCO/T1CK/CN0/RC14_74") (pintype "bidirectional"))
      (node (ref "R51") (pin "2") (pinfunction "2_2") (pintype "passive"))
      (node (ref "U17") (pin "13") (pinfunction "B4_13") (pintype "bidirectional"))
    )
    (net (code "156") (name "/PIC_SOL_8") (class "Default")
      (node (ref "IC2") (pin "19") (pinfunction "AERXD1/INT2/RE9_19") (pintype "bidirectional"))
      (node (ref "R66") (pin "2") (pinfunction "2_2") (pintype "passive"))
      (node (ref "U15") (pin "2") (pinfunction "B1_2") (pintype "bidirectional"))
    )
    (net (code "157") (name "/PIC_SOL_9") (class "Default")
      (node (ref "IC2") (pin "9") (pinfunction "T5CK/SDI1/RC4_9") (pintype "bidirectional"))
      (node (ref "R65") (pin "2") (pinfunction "2_2") (pintype "passive"))
      (node (ref "U15") (pin "5") (pinfunction "B2_5") (pintype "bidirectional"))
    )
    (net (code "158") (name "/PIC_SOL_10") (class "Default")
      (node (ref "IC2") (pin "58") (pinfunction "SCL2/RA2_58") (pintype "bidirectional"))
      (node (ref "R64") (pin "2") (pinfunction "2_2") (pintype "passive"))
      (node (ref "U15") (pin "10") (pinfunction "B3_10") (pintype "bidirectional"))
    )
    (net (code "159") (name "/PIC_SOL_11") (class "Default")
      (node (ref "IC2") (pin "17") (pinfunction "TMS/RA0_17") (pintype "bidirectional"))
      (node (ref "R63") (pin "2") (pinfunction "2_2") (pintype "passive"))
      (node (ref "U15") (pin "13") (pinfunction "B4_13") (pintype "bidirectional"))
    )
    (net (code "160") (name "/PIC_SOL_12") (class "Default")
      (node (ref "IC2") (pin "38") (pinfunction "TCK/RA1_38") (pintype "bidirectional"))
      (node (ref "R62") (pin "2") (pinfunction "2_2") (pintype "passive"))
      (node (ref "U18") (pin "2") (pinfunction "B1_2") (pintype "bidirectional"))
    )
    (net (code "161") (name "/PIC_SOL_13") (class "Default")
      (node (ref "IC2") (pin "60") (pinfunction "TDI/RA4_60") (pintype "bidirectional"))
      (node (ref "R61") (pin "2") (pinfunction "2_2") (pintype "passive"))
      (node (ref "U18") (pin "5") (pinfunction "B2_5") (pintype "bidirectional"))
    )
    (net (code "162") (name "/PIC_SOL_14") (class "Default")
      (node (ref "IC2") (pin "61") (pinfunction "TDO/RA5_61") (pintype "bidirectional"))
      (node (ref "R60") (pin "2") (pinfunction "2_2") (pintype "passive"))
      (node (ref "U18") (pin "10") (pinfunction "B3_10") (pintype "bidirectional"))
    )
    (net (code "163") (name "/PIC_SOL_15") (class "Default")
      (node (ref "IC2") (pin "73") (pinfunction "SOSCI/CN1/RC13_73") (pintype "bidirectional"))
      (node (ref "R59") (pin "2") (pinfunction "2_2") (pintype "passive"))
      (node (ref "U18") (pin "13") (pinfunction "B4_13") (pintype "bidirectional"))
    )
    (net (code "164") (name "/PIC_SOL_16") (class "Default")
      (node (ref "IC2") (pin "89") (pinfunction "C2TX/ETXERR/PMD9/RG1_89") (pintype "bidirectional"))
      (node (ref "R74") (pin "2") (pinfunction "2_2") (pintype "passive"))
      (node (ref "U16") (pin "2") (pinfunction "B1_2") (pintype "bidirectional"))
    )
    (net (code "165") (name "/PIC_SOL_17") (class "Default")
      (node (ref "IC2") (pin "90") (pinfunction "C2RX/PMD8/RG0_90") (pintype "bidirectional"))
      (node (ref "R73") (pin "2") (pinfunction "2_2") (pintype "passive"))
      (node (ref "U16") (pin "5") (pinfunction "B2_5") (pintype "bidirectional"))
    )
    (net (code "166") (name "/PIC_SOL_18") (class "Default")
      (node (ref "IC2") (pin "91") (pinfunction "TRCLK/RA6_91") (pintype "bidirectional"))
      (node (ref "R72") (pin "2") (pinfunction "2_2") (pintype "passive"))
      (node (ref "U16") (pin "10") (pinfunction "B3_10") (pintype "bidirectional"))
    )
    (net (code "167") (name "/PIC_SOL_19") (class "Default")
      (node (ref "IC2") (pin "92") (pinfunction "TRD3/RA7_92") (pintype "bidirectional"))
      (node (ref "R71") (pin "2") (pinfunction "2_2") (pintype "passive"))
      (node (ref "U16") (pin "13") (pinfunction "B4_13") (pintype "bidirectional"))
    )
    (net (code "168") (name "/PIC_SOL_20") (class "Default")
      (node (ref "IC2") (pin "95") (pinfunction "TRD2/RG14_95") (pintype "bidirectional"))
      (node (ref "R70") (pin "2") (pinfunction "2_2") (pintype "passive"))
      (node (ref "U19") (pin "2") (pinfunction "B1_2") (pintype "bidirectional"))
    )
    (net (code "169") (name "/PIC_SOL_21") (class "Default")
      (node (ref "IC2") (pin "96") (pinfunction "TRD1/RG12_96") (pintype "bidirectional"))
      (node (ref "R69") (pin "2") (pinfunction "2_2") (pintype "passive"))
      (node (ref "U19") (pin "5") (pinfunction "B2_5") (pintype "bidirectional"))
    )
    (net (code "170") (name "/PIC_SOL_22") (class "Default")
      (node (ref "IC2") (pin "97") (pinfunction "TRD0/RG13_97") (pintype "bidirectional"))
      (node (ref "R68") (pin "2") (pinfunction "2_2") (pintype "passive"))
      (node (ref "U19") (pin "10") (pinfunction "B3_10") (pintype "bidirectional"))
    )
    (net (code "171") (name "/PIC_SOL_23") (class "Default")
      (node (ref "IC2") (pin "28") (pinfunction "VREF-/CVREF-/AERXD2/PMA7/RA9_28") (pintype "bidirectional"))
      (node (ref "R67") (pin "2") (pinfunction "2_2") (pintype "passive"))
      (node (ref "U19") (pin "13") (pinfunction "B4_13") (pintype "bidirectional"))
    )
    (net (code "172") (name "/PIC_SW_C_0") (class "Default")
      (node (ref "IC2") (pin "68") (pinfunction "RTCC/EMDIO/AEMDIO/IC1/RD8_68") (pintype "bidirectional"))
      (node (ref "IC4") (pin "2") (pinfunction "A1_2") (pintype "input"))
    )
    (net (code "173") (name "/PIC_SW_C_1") (class "Default")
      (node (ref "IC2") (pin "69") (pinfunction "SS1/IC2/RD9_69") (pintype "bidirectional"))
      (node (ref "IC4") (pin "17") (pinfunction "A4_17") (pintype "input"))
    )
    (net (code "174") (name "/PIC_SW_C_2") (class "Default")
      (node (ref "IC2") (pin "70") (pinfunction "SCK1/IC3/PMCS2/PMA15/RD10_70") (pintype "bidirectional"))
      (node (ref "IC4") (pin "4") (pinfunction "A2_4") (pintype "input"))
    )
    (net (code "175") (name "/PIC_SW_C_3") (class "Default")
      (node (ref "IC2") (pin "71") (pinfunction "EMDC/AEMDC/IC4/PMCS1/PMA14/RD11_71") (pintype "bidirectional"))
      (node (ref "IC4") (pin "15") (pinfunction "A3_15") (pintype "input"))
    )
    (net (code "176") (name "/PIC_SW_C_4") (class "Default")
      (node (ref "IC2") (pin "79") (pinfunction "ETXD2/IC5/PMD12/RD12_79") (pintype "bidirectional"))
      (node (ref "IC4") (pin "6") (pinfunction "A3_6") (pintype "input"))
    )
    (net (code "177") (name "/PIC_SW_C_5") (class "Default")
      (node (ref "IC2") (pin "80") (pinfunction "ETXD3/PMD13/CN19/RD13_80") (pintype "bidirectional"))
      (node (ref "IC4") (pin "13") (pinfunction "A2_13") (pintype "input"))
    )
    (net (code "178") (name "/PIC_SW_C_6") (class "Default")
      (node (ref "IC2") (pin "47") (pinfunction "AETXD0/SS1A/U1BRX/U1ACTS/CN20/RD14_47") (pintype "bidirectional"))
      (node (ref "IC4") (pin "8") (pinfunction "A4_8") (pintype "input"))
    )
    (net (code "179") (name "/PIC_SW_C_7") (class "Default")
      (node (ref "IC2") (pin "48") (pinfunction "AETXD1/SCK1A/U1BTX/U1ARTS/CN21/RD15_48") (pintype "bidirectional"))
      (node (ref "IC4") (pin "11") (pinfunction "A1_11") (pintype "input"))
    )
    (net (code "180") (name "/PIC_SW_R_0") (class "Default")
      (node (ref "IC2") (pin "72") (pinfunction "SDO1/OC1/INT0/RD0_72") (pintype "bidirectional"))
      (node (ref "IC3") (pin "18") (pinfunction "Y1_18") (pintype "tri_state"))
    )
    (net (code "181") (name "/PIC_SW_R_1") (class "Default")
      (node (ref "IC2") (pin "76") (pinfunction "OC2/RD1_76") (pintype "bidirectional"))
      (node (ref "IC3") (pin "3") (pinfunction "Y4_3") (pintype "tri_state"))
    )
    (net (code "182") (name "/PIC_SW_R_2") (class "Default")
      (node (ref "IC2") (pin "77") (pinfunction "OC3/RD2_77") (pintype "bidirectional"))
      (node (ref "IC3") (pin "16") (pinfunction "Y2_16") (pintype "tri_state"))
    )
    (net (code "183") (name "/PIC_SW_R_3") (class "Default")
      (node (ref "IC2") (pin "78") (pinfunction "OC4/RD3_78") (pintype "bidirectional"))
      (node (ref "IC3") (pin "5") (pinfunction "Y3_5") (pintype "tri_state"))
    )
    (net (code "184") (name "/PIC_SW_R_4") (class "Default")
      (node (ref "IC2") (pin "81") (pinfunction "OC5/PMWR/CN13/RD4_81") (pintype "bidirectional"))
      (node (ref "IC3") (pin "14") (pinfunction "Y3_14") (pintype "tri_state"))
    )
    (net (code "185") (name "/PIC_SW_R_5") (class "Default")
      (node (ref "IC2") (pin "82") (pinfunction "PMRD/CN14/RD5_82") (pintype "bidirectional"))
      (node (ref "IC3") (pin "7") (pinfunction "Y2_7") (pintype "tri_state"))
    )
    (net (code "186") (name "/PIC_SW_R_6") (class "Default")
      (node (ref "IC2") (pin "83") (pinfunction "ETXEN/PMD14/CN15/RD6_83") (pintype "bidirectional"))
      (node (ref "IC3") (pin "12") (pinfunction "Y4_12") (pintype "tri_state"))
    )
    (net (code "187") (name "/PIC_SW_R_7") (class "Default")
      (node (ref "IC2") (pin "84") (pinfunction "ETXCLK/PMD15/CN16/RD7_84") (pintype "bidirectional"))
      (node (ref "IC3") (pin "9") (pinfunction "Y1_9") (pintype "tri_state"))
    )
    (net (code "188") (name "/PROP_ACT") (class "Default")
      (node (ref "PROP_ACT") (pin "ANODE") (pinfunction "ANODE_ANODE") (pintype "bidirectional"))
      (node (ref "U1") (pin "34") (pinfunction "P27_34") (pintype "bidirectional"))
    )
    (net (code "189") (name "/PROP_AUX0") (class "Default")
      (node (ref "PROP_AUX0") (pin "P$1") (pinfunction "P$1_P$1") (pintype "bidirectional"))
      (node (ref "RGB_COM_OUT") (pin "P$3") (pinfunction "3_P$3") (pintype "bidirectional"))
      (node (ref "U1") (pin "1") (pinfunction "P4_1") (pintype "bidirectional"))
    )
    (net (code "190") (name "/PROP_AUX1") (class "Default")
      (node (ref "PROP_AUX1") (pin "P$1") (pinfunction "P$1_P$1") (pintype "bidirectional"))
      (node (ref "RGB_COM_OUT") (pin "P$2") (pinfunction "2_P$2") (pintype "bidirectional"))
      (node (ref "U1") (pin "2") (pinfunction "P5_2") (pintype "bidirectional"))
    )
    (net (code "191") (name "/PROP_AUX2") (class "Default")
      (node (ref "PHABULOUS") (pin "12") (pinfunction "12_12") (pintype "bidirectional"))
      (node (ref "U1") (pin "3") (pinfunction "P6_3") (pintype "bidirectional"))
    )
    (net (code "192") (name "/PROP_AUX3") (class "Default")
      (node (ref "PHABULOUS") (pin "13") (pinfunction "13_13") (pintype "bidirectional"))
      (node (ref "U1") (pin "4") (pinfunction "P7_4") (pintype "bidirectional"))
    )
    (net (code "193") (name "/PROP_AUX4") (class "Default")
      (node (ref "PHABULOUS") (pin "14") (pinfunction "14_14") (pintype "bidirectional"))
      (node (ref "U1") (pin "9") (pinfunction "P8_9") (pintype "bidirectional"))
    )
    (net (code "194") (name "/PROP_AUX5") (class "Default")
      (node (ref "PHABULOUS") (pin "15") (pinfunction "15_15") (pintype "bidirectional"))
      (node (ref "U1") (pin "10") (pinfunction "P9_10") (pintype "bidirectional"))
    )
    (net (code "195") (name "/PROP_AUX6") (class "Default")
      (node (ref "PHABULOUS") (pin "16") (pinfunction "16_16") (pintype "bidirectional"))
      (node (ref "U1") (pin "11") (pinfunction "P10_11") (pintype "bidirectional"))
    )
    (net (code "196") (name "/PROP_AUX7") (class "Default")
      (node (ref "PHABULOUS") (pin "17") (pinfunction "17_17") (pintype "bidirectional"))
      (node (ref "U1") (pin "12") (pinfunction "P11_12") (pintype "bidirectional"))
    )
    (net (code "197") (name "/PROP_AUX8") (class "Default")
      (node (ref "PHABULOUS") (pin "18") (pinfunction "18_18") (pintype "bidirectional"))
      (node (ref "U1") (pin "13") (pinfunction "P12_13") (pintype "bidirectional"))
    )
    (net (code "198") (name "/PROP_AUX9") (class "Default")
      (node (ref "PHABULOUS") (pin "19") (pinfunction "19_19") (pintype "bidirectional"))
      (node (ref "U1") (pin "26") (pinfunction "P23_26") (pintype "bidirectional"))
    )
    (net (code "199") (name "/PROP_PROGRAM") (class "Default")
      (node (ref "PROP_CONFIG") (pin "P$1") (pinfunction "P$1_P$1") (pintype "bidirectional"))
      (node (ref "R1") (pin "1") (pinfunction "1_1") (pintype "passive"))
      (node (ref "U1") (pin "14") (pinfunction "P13_14") (pintype "bidirectional"))
    )
    (net (code "200") (name "/RES") (class "Default")
      (node (ref "C1") (pin "2") (pinfunction "2_2") (pintype "passive"))
      (node (ref "PROP_RESET") (pin "P$2") (pinfunction "P$2_P$2") (pintype "bidirectional"))
      (node (ref "R176") (pin "1") (pinfunction "1_1") (pintype "passive"))
      (node (ref "U1") (pin "7") (pinfunction "~{RES}_7") (pintype "bidirectional"))
    )
    (net (code "201") (name "/RGB_BOUT_L") (class "Default")
      (node (ref "CAB_RGB") (pin "P$4") (pinfunction "4_P$4") (pintype "bidirectional"))
      (node (ref "RGB_0") (pin "D") (pinfunction "DRAIN_D") (pintype "bidirectional"))
      (node (ref "RGB_BOUT_L") (pin "P$1") (pinfunction "P$1_P$1") (pintype "bidirectional"))
    )
    (net (code "202") (name "/RGB_BOUT_R") (class "Default")
      (node (ref "CAB_RGB") (pin "P$8") (pinfunction "8_P$8") (pintype "bidirectional"))
      (node (ref "RGB_3") (pin "D") (pinfunction "DRAIN_D") (pintype "bidirectional"))
      (node (ref "RGB_BOUT_R") (pin "P$1") (pinfunction "P$1_P$1") (pintype "bidirectional"))
    )
    (net (code "203") (name "/RGB_CLK") (class "Default")
      (node (ref "IC2") (pin "98") (pinfunction "PMD2/RE2_98") (pintype "bidirectional"))
      (node (ref "U38") (pin "1") (pinfunction "CLI_1") (pintype "bidirectional"))
    )
    (net (code "204") (name "/RGB_CLK_1") (class "Default")
      (node (ref "U36") (pin "1") (pinfunction "CLI_1") (pintype "bidirectional"))
      (node (ref "U38") (pin "13") (pinfunction "CKO_13") (pintype "bidirectional"))
    )
    (net (code "205") (name "/RGB_CLK_OUT") (class "Default")
      (node (ref "U36") (pin "13") (pinfunction "CKO_13") (pintype "bidirectional"))
    )
    (net (code "206") (name "/RGB_DATA") (class "Default")
      (node (ref "IC2") (pin "94") (pinfunction "PMD1/RE1_94") (pintype "bidirectional"))
      (node (ref "U38") (pin "2") (pinfunction "SDI_2") (pintype "bidirectional"))
    )
    (net (code "207") (name "/RGB_DATA_1") (class "Default")
      (node (ref "U36") (pin "2") (pinfunction "SDI_2") (pintype "bidirectional"))
      (node (ref "U38") (pin "12") (pinfunction "SDO_12") (pintype "bidirectional"))
    )
    (net (code "208") (name "/RGB_DATA_OUT") (class "Default")
      (node (ref "U36") (pin "12") (pinfunction "SDO_12") (pintype "bidirectional"))
    )
    (net (code "209") (name "/RGB_GOUT_L") (class "Default")
      (node (ref "CAB_RGB") (pin "P$5") (pinfunction "5_P$5") (pintype "bidirectional"))
      (node (ref "RGB_1") (pin "D") (pinfunction "DRAIN_D") (pintype "bidirectional"))
      (node (ref "RGB_GOUT_L") (pin "P$1") (pinfunction "P$1_P$1") (pintype "bidirectional"))
    )
    (net (code "210") (name "/RGB_GOUT_R") (class "Default")
      (node (ref "CAB_RGB") (pin "P$9") (pinfunction "9_P$9") (pintype "bidirectional"))
      (node (ref "RGB_4") (pin "D") (pinfunction "DRAIN_D") (pintype "bidirectional"))
      (node (ref "RGB_GOUT_R") (pin "P$1") (pinfunction "P$1_P$1") (pintype "bidirectional"))
    )
    (net (code "211") (name "/RGB_ROUT_L") (class "Default")
      (node (ref "CAB_RGB") (pin "P$6") (pinfunction "6_P$6") (pintype "bidirectional"))
      (node (ref "RGB_2") (pin "D") (pinfunction "DRAIN_D") (pintype "bidirectional"))
      (node (ref "RGB_ROUT_L") (pin "P$1") (pinfunction "P$1_P$1") (pintype "bidirectional"))
    )
    (net (code "212") (name "/RGB_ROUT_R") (class "Default")
      (node (ref "CAB_RGB") (pin "P$10") (pinfunction "10_P$10") (pintype "bidirectional"))
      (node (ref "RGB_5") (pin "D") (pinfunction "DRAIN_D") (pintype "bidirectional"))
      (node (ref "RGB_ROUT_R") (pin "P$1") (pinfunction "P$1_P$1") (pintype "bidirectional"))
    )
    (net (code "213") (name "/RX_PIC32") (class "Default")
      (node (ref "IC2") (pin "52") (pinfunction "SDA1A/SDI1A/U1ARX/RF2_52") (pintype "bidirectional"))
      (node (ref "PIC32_TC") (pin "P$4") (pinfunction "PIN4_P$4") (pintype "bidirectional"))
      (node (ref "PIC32_UART") (pin "4") (pinfunction "4_4") (pintype "passive"))
    )
    (net (code "214") (name "/RX_PROP") (class "Default")
      (node (ref "PROP_TC") (pin "P$4") (pinfunction "PIN4_P$4") (pintype "bidirectional"))
      (node (ref "PROP_UART") (pin "4") (pinfunction "4_4") (pintype "passive"))
      (node (ref "U1") (pin "38") (pinfunction "P31_38") (pintype "bidirectional"))
    )
    (net (code "215") (name "/R_FLIP") (class "Default")
      (node (ref "R155") (pin "2") (pinfunction "2_2") (pintype "passive"))
      (node (ref "R45") (pin "1") (pinfunction "1_1") (pintype "passive"))
      (node (ref "U12") (pin "13") (pinfunction "D2_13") (pintype "bidirectional"))
    )
    (net (code "216") (name "/R_FLIP_OUT") (class "Default")
      (node (ref "CABINET_I/O") (pin "P$11") (pinfunction "11_P$11") (pintype "bidirectional"))
      (node (ref "R155") (pin "1") (pinfunction "1_1") (pintype "passive"))
      (node (ref "R_FLIP_OUT") (pin "P$1") (pinfunction "P$1_P$1") (pintype "bidirectional"))
    )
    (net (code "217") (name "/SCL_PROP") (class "Default")
      (node (ref "R16") (pin "1") (pinfunction "1_1") (pintype "passive"))
      (node (ref "U1") (pin "35") (pinfunction "P28_35") (pintype "bidirectional"))
      (node (ref "U4") (pin "6") (pinfunction "SCL_6") (pintype "bidirectional"))
    )
    (net (code "218") (name "/SDA_PROP") (class "Default")
      (node (ref "R17") (pin "1") (pinfunction "1_1") (pintype "passive"))
      (node (ref "U1") (pin "36") (pinfunction "P29_36") (pintype "bidirectional"))
      (node (ref "U4") (pin "5") (pinfunction "SDA_5") (pintype "bidirectional"))
    )
    (net (code "219") (name "/SD_CS") (class "Default")
      (node (ref "R22") (pin "2") (pinfunction "2_2") (pintype "passive"))
      (node (ref "SD0") (pin "1") (pinfunction "CS_1") (pintype "bidirectional"))
      (node (ref "SD_CS") (pin "P$1") (pinfunction "P$1_P$1") (pintype "bidirectional"))
      (node (ref "U1") (pin "44") (pinfunction "P3_44") (pintype "bidirectional"))
    )
    (net (code "220") (name "/SD_DI") (class "Default")
      (node (ref "R18") (pin "2") (pinfunction "2_2") (pintype "passive"))
      (node (ref "SD0") (pin "2") (pinfunction "DI_2") (pintype "bidirectional"))
      (node (ref "SD_DI") (pin "P$1") (pinfunction "P$1_P$1") (pintype "bidirectional"))
      (node (ref "U1") (pin "43") (pinfunction "P2_43") (pintype "bidirectional"))
    )
    (net (code "221") (name "/SD_DO") (class "Default")
      (node (ref "R20") (pin "2") (pinfunction "2_2") (pintype "passive"))
      (node (ref "SD0") (pin "7") (pinfunction "D0_7") (pintype "bidirectional"))
      (node (ref "SD_DO") (pin "P$1") (pinfunction "P$1_P$1") (pintype "bidirectional"))
      (node (ref "U1") (pin "41") (pinfunction "P0_41") (pintype "bidirectional"))
    )
    (net (code "222") (name "/SD_SCLK") (class "Default")
      (node (ref "R19") (pin "2") (pinfunction "2_2") (pintype "passive"))
      (node (ref "SD0") (pin "5") (pinfunction "SCLK_5") (pintype "bidirectional"))
      (node (ref "SD_SCLK") (pin "P$1") (pinfunction "P$1_P$1") (pintype "bidirectional"))
      (node (ref "U1") (pin "42") (pinfunction "P1_42") (pintype "bidirectional"))
    )
    (net (code "223") (name "/SERVO_0") (class "Default")
      (node (ref "IC2") (pin "88") (pinfunction "C1TX/ETXD0/PMD10/RF1_88") (pintype "bidirectional"))
      (node (ref "SERVO_0") (pin "P$3") (pinfunction "PIN3_P$3") (pintype "bidirectional"))
      (node (ref "SERVO_0_") (pin "P$1") (pinfunction "P$1_P$1") (pintype "bidirectional"))
    )
    (net (code "224") (name "/SERVO_1") (class "Default")
      (node (ref "IC2") (pin "29") (pinfunction "VREF+/CVREF+/AERXD3/PMA6/RA10_29") (pintype "bidirectional"))
      (node (ref "SERVO_1") (pin "P$3") (pinfunction "PIN3_P$3") (pintype "bidirectional"))
      (node (ref "SERVO_1_") (pin "P$1") (pinfunction "P$1_P$1") (pintype "bidirectional"))
    )
    (net (code "225") (name "/SERVO_2") (class "Default")
      (node (ref "IC2") (pin "49") (pinfunction "SDA3A/SDI3A/U3ARX/PMA9/CN17/RF4_49") (pintype "bidirectional"))
      (node (ref "SERVO_2") (pin "P$3") (pinfunction "PIN3_P$3") (pintype "bidirectional"))
      (node (ref "SERVO_2_") (pin "P$1") (pinfunction "P$1_P$1") (pintype "bidirectional"))
    )
    (net (code "226") (name "/SERVO_3") (class "Default")
      (node (ref "IC2") (pin "99") (pinfunction "PMD3/RE3_99") (pintype "bidirectional"))
      (node (ref "PHABULOUS") (pin "9") (pinfunction "9_9") (pintype "bidirectional"))
      (node (ref "SERVO_3") (pin "P$3") (pinfunction "PIN3_P$3") (pintype "bidirectional"))
      (node (ref "SERVO_3_") (pin "P$1") (pinfunction "P$1_P$1") (pintype "bidirectional"))
    )
    (net (code "227") (name "/SERVO_4") (class "Default")
      (node (ref "IC2") (pin "100") (pinfunction "PMD4/RE4_100") (pintype "bidirectional"))
      (node (ref "PHABULOUS") (pin "10") (pinfunction "10_10") (pintype "bidirectional"))
      (node (ref "SERVO_4") (pin "P$3") (pinfunction "PIN3_P$3") (pintype "bidirectional"))
      (node (ref "SERVO_4_") (pin "P$1") (pinfunction "P$1_P$1") (pintype "bidirectional"))
    )
    (net (code "228") (name "/SERVO_5V") (class "Default")
      (node (ref "D5") (pin "ANODE") (pinfunction "ANODE_ANODE") (pintype "power_in"))
      (node (ref "F6") (pin "P$2") (pinfunction "P$2_P$2") (pintype "bidirectional"))
      (node (ref "SERVO_0") (pin "P$2") (pinfunction "PIN2_P$2") (pintype "bidirectional"))
      (node (ref "SERVO_1") (pin "P$2") (pinfunction "PIN2_P$2") (pintype "bidirectional"))
      (node (ref "SERVO_2") (pin "P$2") (pinfunction "PIN2_P$2") (pintype "bidirectional"))
      (node (ref "SERVO_3") (pin "P$2") (pinfunction "PIN2_P$2") (pintype "bidirectional"))
      (node (ref "SERVO_4") (pin "P$2") (pinfunction "PIN2_P$2") (pintype "bidirectional"))
    )
    (net (code "229") (name "/SOL_0") (class "Default")
      (node (ref "SOL_0") (pin "G") (pinfunction "GATE_G") (pintype "bidirectional"))
      (node (ref "U14") (pin "3") (pinfunction "Y1_3") (pintype "bidirectional"))
    )
    (net (code "230") (name "/SOL_1") (class "Default")
      (node (ref "SOL_1") (pin "G") (pinfunction "GATE_G") (pintype "bidirectional"))
      (node (ref "U14") (pin "6") (pinfunction "Y2_6") (pintype "bidirectional"))
    )
    (net (code "231") (name "/SOL_2") (class "Default")
      (node (ref "SOL_2") (pin "G") (pinfunction "GATE_G") (pintype "bidirectional"))
      (node (ref "U14") (pin "8") (pinfunction "Y3_8") (pintype "bidirectional"))
    )
    (net (code "232") (name "/SOL_3") (class "Default")
      (node (ref "SOL_3") (pin "G") (pinfunction "GATE_G") (pintype "bidirectional"))
      (node (ref "U14") (pin "11") (pinfunction "Y4_11") (pintype "bidirectional"))
    )
    (net (code "233") (name "/SOL_4") (class "Default")
      (node (ref "SOL_4") (pin "G") (pinfunction "GATE_G") (pintype "bidirectional"))
      (node (ref "U17") (pin "3") (pinfunction "Y1_3") (pintype "bidirectional"))
    )
    (net (code "234") (name "/SOL_5") (class "Default")
      (node (ref "SOL_5") (pin "G") (pinfunction "GATE_G") (pintype "bidirectional"))
      (node (ref "U17") (pin "6") (pinfunction "Y2_6") (pintype "bidirectional"))
    )
    (net (code "235") (name "/SOL_6") (class "Default")
      (node (ref "SOL_6") (pin "G") (pinfunction "GATE_G") (pintype "bidirectional"))
      (node (ref "U17") (pin "8") (pinfunction "Y3_8") (pintype "bidirectional"))
    )
    (net (code "236") (name "/SOL_7") (class "Default")
      (node (ref "SOL_7") (pin "G") (pinfunction "GATE_G") (pintype "bidirectional"))
      (node (ref "U17") (pin "11") (pinfunction "Y4_11") (pintype "bidirectional"))
    )
    (net (code "237") (name "/SOL_8") (class "Default")
      (node (ref "SOL_8") (pin "G") (pinfunction "GATE_G") (pintype "bidirectional"))
      (node (ref "U15") (pin "3") (pinfunction "Y1_3") (pintype "bidirectional"))
    )
    (net (code "238") (name "/SOL_9") (class "Default")
      (node (ref "SOL_9") (pin "G") (pinfunction "GATE_G") (pintype "bidirectional"))
      (node (ref "U15") (pin "6") (pinfunction "Y2_6") (pintype "bidirectional"))
    )
    (net (code "239") (name "/SOL_10") (class "Default")
      (node (ref "SOL_10") (pin "G") (pinfunction "GATE_G") (pintype "bidirectional"))
      (node (ref "U15") (pin "8") (pinfunction "Y3_8") (pintype "bidirectional"))
    )
    (net (code "240") (name "/SOL_11") (class "Default")
      (node (ref "SOL_11") (pin "G") (pinfunction "GATE_G") (pintype "bidirectional"))
      (node (ref "U15") (pin "11") (pinfunction "Y4_11") (pintype "bidirectional"))
    )
    (net (code "241") (name "/SOL_12") (class "Default")
      (node (ref "SOL_12") (pin "G") (pinfunction "GATE_G") (pintype "bidirectional"))
      (node (ref "U18") (pin "3") (pinfunction "Y1_3") (pintype "bidirectional"))
    )
    (net (code "242") (name "/SOL_13") (class "Default")
      (node (ref "SOL_13") (pin "G") (pinfunction "GATE_G") (pintype "bidirectional"))
      (node (ref "U18") (pin "6") (pinfunction "Y2_6") (pintype "bidirectional"))
    )
    (net (code "243") (name "/SOL_14") (class "Default")
      (node (ref "SOL_14") (pin "G") (pinfunction "GATE_G") (pintype "bidirectional"))
      (node (ref "U18") (pin "8") (pinfunction "Y3_8") (pintype "bidirectional"))
    )
    (net (code "244") (name "/SOL_15") (class "Default")
      (node (ref "SOL_15") (pin "G") (pinfunction "GATE_G") (pintype "bidirectional"))
      (node (ref "U18") (pin "11") (pinfunction "Y4_11") (pintype "bidirectional"))
    )
    (net (code "245") (name "/SOL_16") (class "Default")
      (node (ref "SOL_16") (pin "G") (pinfunction "GATE_G") (pintype "bidirectional"))
      (node (ref "U16") (pin "3") (pinfunction "Y1_3") (pintype "bidirectional"))
    )
    (net (code "246") (name "/SOL_17") (class "Default")
      (node (ref "SOL_17") (pin "G") (pinfunction "GATE_G") (pintype "bidirectional"))
      (node (ref "U16") (pin "6") (pinfunction "Y2_6") (pintype "bidirectional"))
    )
    (net (code "247") (name "/SOL_18") (class "Default")
      (node (ref "SOL_18") (pin "G") (pinfunction "GATE_G") (pintype "bidirectional"))
      (node (ref "U16") (pin "8") (pinfunction "Y3_8") (pintype "bidirectional"))
    )
    (net (code "248") (name "/SOL_19") (class "Default")
      (node (ref "SOL_19") (pin "G") (pinfunction "GATE_G") (pintype "bidirectional"))
      (node (ref "U16") (pin "11") (pinfunction "Y4_11") (pintype "bidirectional"))
    )
    (net (code "249") (name "/SOL_20") (class "Default")
      (node (ref "SOL_20") (pin "G") (pinfunction "GATE_G") (pintype "bidirectional"))
      (node (ref "U19") (pin "3") (pinfunction "Y1_3") (pintype "bidirectional"))
    )
    (net (code "250") (name "/SOL_21") (class "Default")
      (node (ref "SOL_21") (pin "G") (pinfunction "GATE_G") (pintype "bidirectional"))
      (node (ref "U19") (pin "6") (pinfunction "Y2_6") (pintype "bidirectional"))
    )
    (net (code "251") (name "/SOL_22") (class "Default")
      (node (ref "SOL_22") (pin "G") (pinfunction "GATE_G") (pintype "bidirectional"))
      (node (ref "U19") (pin "8") (pinfunction "Y3_8") (pintype "bidirectional"))
    )
    (net (code "252") (name "/SOL_23") (class "Default")
      (node (ref "SOL_23") (pin "G") (pinfunction "GATE_G") (pintype "bidirectional"))
      (node (ref "U19") (pin "11") (pinfunction "Y4_11") (pintype "bidirectional"))
    )
    (net (code "253") (name "/SOL_GND") (class "Default")
      (node (ref "R136") (pin "2") (pinfunction "2_2") (pintype "passive"))
      (node (ref "R163") (pin "2") (pinfunction "2_2") (pintype "passive"))
      (node (ref "R164") (pin "2") (pinfunction "2_2") (pintype "passive"))
      (node (ref "R165") (pin "2") (pinfunction "2_2") (pintype "passive"))
      (node (ref "SOLENOID_POWER_IN") (pin "1") (pinfunction "PIN1_1") (pintype "bidirectional"))
      (node (ref "SOLENOID_POWER_IN") (pin "2") (pinfunction "PIN2_2") (pintype "bidirectional"))
      (node (ref "SOL_0") (pin "S") (pinfunction "SOURCE_S") (pintype "bidirectional"))
      (node (ref "SOL_1") (pin "S") (pinfunction "SOURCE_S") (pintype "bidirectional"))
      (node (ref "SOL_10") (pin "S") (pinfunction "SOURCE_S") (pintype "bidirectional"))
      (node (ref "SOL_11") (pin "S") (pinfunction "SOURCE_S") (pintype "bidirectional"))
      (node (ref "SOL_12") (pin "S") (pinfunction "SOURCE_S") (pintype "bidirectional"))
      (node (ref "SOL_13") (pin "S") (pinfunction "SOURCE_S") (pintype "bidirectional"))
      (node (ref "SOL_14") (pin "S") (pinfunction "SOURCE_S") (pintype "bidirectional"))
      (node (ref "SOL_15") (pin "S") (pinfunction "SOURCE_S") (pintype "bidirectional"))
      (node (ref "SOL_16") (pin "S") (pinfunction "SOURCE_S") (pintype "bidirectional"))
      (node (ref "SOL_17") (pin "S") (pinfunction "SOURCE_S") (pintype "bidirectional"))
      (node (ref "SOL_18") (pin "S") (pinfunction "SOURCE_S") (pintype "bidirectional"))
      (node (ref "SOL_19") (pin "S") (pinfunction "SOURCE_S") (pintype "bidirectional"))
      (node (ref "SOL_2") (pin "S") (pinfunction "SOURCE_S") (pintype "bidirectional"))
      (node (ref "SOL_20") (pin "S") (pinfunction "SOURCE_S") (pintype "bidirectional"))
      (node (ref "SOL_21") (pin "S") (pinfunction "SOURCE_S") (pintype "bidirectional"))
      (node (ref "SOL_22") (pin "S") (pinfunction "SOURCE_S") (pintype "bidirectional"))
      (node (ref "SOL_23") (pin "S") (pinfunction "SOURCE_S") (pintype "bidirectional"))
      (node (ref "SOL_3") (pin "S") (pinfunction "SOURCE_S") (pintype "bidirectional"))
      (node (ref "SOL_4") (pin "S") (pinfunction "SOURCE_S") (pintype "bidirectional"))
      (node (ref "SOL_5") (pin "S") (pinfunction "SOURCE_S") (pintype "bidirectional"))
      (node (ref "SOL_6") (pin "S") (pinfunction "SOURCE_S") (pintype "bidirectional"))
      (node (ref "SOL_7") (pin "S") (pinfunction "SOURCE_S") (pintype "bidirectional"))
      (node (ref "SOL_8") (pin "S") (pinfunction "SOURCE_S") (pintype "bidirectional"))
      (node (ref "SOL_9") (pin "S") (pinfunction "SOURCE_S") (pintype "bidirectional"))
      (node (ref "SOL_GND") (pin "P$1") (pinfunction "P$1_P$1") (pintype "bidirectional"))
    )
    (net (code "254") (name "/SOL_PWR_0") (class "Default")
      (node (ref "KNOCKER") (pin "P$2") (pinfunction "PIN2_P$2") (pintype "bidirectional"))
      (node (ref "SOL_0") (pin "D") (pinfunction "DRAIN_D") (pintype "bidirectional"))
      (node (ref "SOL_BANK_0") (pin "P$2") (pinfunction "PIN2_P$2") (pintype "bidirectional"))
      (node (ref "SOL_PWR_0") (pin "P$1") (pinfunction "P$1_P$1") (pintype "bidirectional"))
    )
    (net (code "255") (name "/SOL_PWR_1") (class "Default")
      (node (ref "SHAKER") (pin "P$2") (pinfunction "PIN2_P$2") (pintype "bidirectional"))
      (node (ref "SOL_1") (pin "D") (pinfunction "DRAIN_D") (pintype "bidirectional"))
      (node (ref "SOL_BANK_0") (pin "P$3") (pinfunction "PIN3_P$3") (pintype "bidirectional"))
      (node (ref "SOL_PWR_1") (pin "P$1") (pinfunction "P$1_P$1") (pintype "bidirectional"))
    )
    (net (code "256") (name "/SOL_PWR_2") (class "Default")
      (node (ref "SOL_2") (pin "D") (pinfunction "DRAIN_D") (pintype "bidirectional"))
      (node (ref "SOL_BANK_0") (pin "P$4") (pinfunction "PIN4_P$4") (pintype "bidirectional"))
      (node (ref "SOL_PWR_2") (pin "P$1") (pinfunction "P$1_P$1") (pintype "bidirectional"))
    )
    (net (code "257") (name "/SOL_PWR_3") (class "Default")
      (node (ref "SOL_3") (pin "D") (pinfunction "DRAIN_D") (pintype "bidirectional"))
      (node (ref "SOL_BANK_0") (pin "P$5") (pinfunction "PIN5_P$5") (pintype "bidirectional"))
      (node (ref "SOL_PWR_3") (pin "P$1") (pinfunction "P$1_P$1") (pintype "bidirectional"))
    )
    (net (code "258") (name "/SOL_PWR_4") (class "Default")
      (node (ref "SOL_4") (pin "D") (pinfunction "DRAIN_D") (pintype "bidirectional"))
      (node (ref "SOL_BANK_0") (pin "P$7") (pinfunction "PIN6_P$7") (pintype "bidirectional"))
      (node (ref "SOL_PWR_4") (pin "P$1") (pinfunction "P$1_P$1") (pintype "bidirectional"))
    )
    (net (code "259") (name "/SOL_PWR_5") (class "Default")
      (node (ref "SOL_5") (pin "D") (pinfunction "DRAIN_D") (pintype "bidirectional"))
      (node (ref "SOL_BANK_0") (pin "P$8") (pinfunction "PIN7_P$8") (pintype "bidirectional"))
      (node (ref "SOL_PWR_5") (pin "P$1") (pinfunction "P$1_P$1") (pintype "bidirectional"))
    )
    (net (code "260") (name "/SOL_PWR_6") (class "Default")
      (node (ref "SOL_6") (pin "D") (pinfunction "DRAIN_D") (pintype "bidirectional"))
      (node (ref "SOL_BANK_0") (pin "P$9") (pinfunction "PIN8_P$9") (pintype "bidirectional"))
      (node (ref "SOL_PWR_6") (pin "P$1") (pinfunction "P$1_P$1") (pintype "bidirectional"))
    )
    (net (code "261") (name "/SOL_PWR_7") (class "Default")
      (node (ref "SOL_7") (pin "D") (pinfunction "DRAIN_D") (pintype "bidirectional"))
      (node (ref "SOL_BANK_0") (pin "P$10") (pinfunction "PIN9_P$10") (pintype "bidirectional"))
      (node (ref "SOL_PWR_7") (pin "P$1") (pinfunction "P$1_P$1") (pintype "bidirectional"))
    )
    (net (code "262") (name "/SOL_PWR_8") (class "Default")
      (node (ref "SOL_8") (pin "D") (pinfunction "DRAIN_D") (pintype "bidirectional"))
      (node (ref "SOL_BANK_1") (pin "P$2") (pinfunction "PIN2_P$2") (pintype "bidirectional"))
      (node (ref "SOL_PWR_8") (pin "P$1") (pinfunction "P$1_P$1") (pintype "bidirectional"))
    )
    (net (code "263") (name "/SOL_PWR_9") (class "Default")
      (node (ref "SOL_9") (pin "D") (pinfunction "DRAIN_D") (pintype "bidirectional"))
      (node (ref "SOL_BANK_1") (pin "P$3") (pinfunction "PIN3_P$3") (pintype "bidirectional"))
      (node (ref "SOL_PWR_9") (pin "P$1") (pinfunction "P$1_P$1") (pintype "bidirectional"))
    )
    (net (code "264") (name "/SOL_PWR_10") (class "Default")
      (node (ref "SOL_10") (pin "D") (pinfunction "DRAIN_D") (pintype "bidirectional"))
      (node (ref "SOL_BANK_1") (pin "P$4") (pinfunction "PIN4_P$4") (pintype "bidirectional"))
      (node (ref "SOL_PWR_10") (pin "P$1") (pinfunction "P$1_P$1") (pintype "bidirectional"))
    )
    (net (code "265") (name "/SOL_PWR_11") (class "Default")
      (node (ref "SOL_11") (pin "D") (pinfunction "DRAIN_D") (pintype "bidirectional"))
      (node (ref "SOL_BANK_1") (pin "P$5") (pinfunction "PIN5_P$5") (pintype "bidirectional"))
      (node (ref "SOL_PWR_11") (pin "P$1") (pinfunction "P$1_P$1") (pintype "bidirectional"))
    )
    (net (code "266") (name "/SOL_PWR_12") (class "Default")
      (node (ref "SOL_12") (pin "D") (pinfunction "DRAIN_D") (pintype "bidirectional"))
      (node (ref "SOL_BANK_1") (pin "P$6") (pinfunction "PIN6_P$6") (pintype "bidirectional"))
      (node (ref "SOL_PWR_12") (pin "P$1") (pinfunction "P$1_P$1") (pintype "bidirectional"))
    )
    (net (code "267") (name "/SOL_PWR_13") (class "Default")
      (node (ref "SOL_13") (pin "D") (pinfunction "DRAIN_D") (pintype "bidirectional"))
      (node (ref "SOL_BANK_1") (pin "P$8") (pinfunction "PIN7_P$8") (pintype "bidirectional"))
      (node (ref "SOL_PWR_13") (pin "P$1") (pinfunction "P$1_P$1") (pintype "bidirectional"))
    )
    (net (code "268") (name "/SOL_PWR_14") (class "Default")
      (node (ref "SOL_14") (pin "D") (pinfunction "DRAIN_D") (pintype "bidirectional"))
      (node (ref "SOL_BANK_1") (pin "P$9") (pinfunction "PIN8_P$9") (pintype "bidirectional"))
      (node (ref "SOL_PWR_14") (pin "P$1") (pinfunction "P$1_P$1") (pintype "bidirectional"))
    )
    (net (code "269") (name "/SOL_PWR_15") (class "Default")
      (node (ref "SOL_15") (pin "D") (pinfunction "DRAIN_D") (pintype "bidirectional"))
      (node (ref "SOL_BANK_1") (pin "P$10") (pinfunction "PIN9_P$10") (pintype "bidirectional"))
      (node (ref "SOL_PWR_15") (pin "P$1") (pinfunction "P$1_P$1") (pintype "bidirectional"))
    )
    (net (code "270") (name "/SOL_PWR_16") (class "Default")
      (node (ref "SOL_16") (pin "D") (pinfunction "DRAIN_D") (pintype "bidirectional"))
      (node (ref "SOL_BANK_2") (pin "P$2") (pinfunction "PIN2_P$2") (pintype "bidirectional"))
      (node (ref "SOL_PWR_16") (pin "P$1") (pinfunction "P$1_P$1") (pintype "bidirectional"))
    )
    (net (code "271") (name "/SOL_PWR_17") (class "Default")
      (node (ref "SOL_17") (pin "D") (pinfunction "DRAIN_D") (pintype "bidirectional"))
      (node (ref "SOL_BANK_2") (pin "P$3") (pinfunction "PIN3_P$3") (pintype "bidirectional"))
      (node (ref "SOL_PWR_17") (pin "P$1") (pinfunction "P$1_P$1") (pintype "bidirectional"))
    )
    (net (code "272") (name "/SOL_PWR_18") (class "Default")
      (node (ref "SOL_18") (pin "D") (pinfunction "DRAIN_D") (pintype "bidirectional"))
      (node (ref "SOL_BANK_2") (pin "P$4") (pinfunction "PIN4_P$4") (pintype "bidirectional"))
      (node (ref "SOL_PWR_18") (pin "P$1") (pinfunction "P$1_P$1") (pintype "bidirectional"))
    )
    (net (code "273") (name "/SOL_PWR_19") (class "Default")
      (node (ref "SOL_19") (pin "D") (pinfunction "DRAIN_D") (pintype "bidirectional"))
      (node (ref "SOL_BANK_2") (pin "P$5") (pinfunction "PIN5_P$5") (pintype "bidirectional"))
      (node (ref "SOL_PWR_19") (pin "P$1") (pinfunction "P$1_P$1") (pintype "bidirectional"))
    )
    (net (code "274") (name "/SOL_PWR_20") (class "Default")
      (node (ref "SOL_20") (pin "D") (pinfunction "DRAIN_D") (pintype "bidirectional"))
      (node (ref "SOL_BANK_2") (pin "P$6") (pinfunction "PIN6_P$6") (pintype "bidirectional"))
      (node (ref "SOL_PWR_20") (pin "P$1") (pinfunction "P$1_P$1") (pintype "bidirectional"))
    )
    (net (code "275") (name "/SOL_PWR_21") (class "Default")
      (node (ref "SOL_21") (pin "D") (pinfunction "DRAIN_D") (pintype "bidirectional"))
      (node (ref "SOL_BANK_2") (pin "P$7") (pinfunction "PIN7_P$7") (pintype "bidirectional"))
      (node (ref "SOL_PWR_21") (pin "P$1") (pinfunction "P$1_P$1") (pintype "bidirectional"))
    )
    (net (code "276") (name "/SOL_PWR_22") (class "Default")
      (node (ref "SOL_22") (pin "D") (pinfunction "DRAIN_D") (pintype "bidirectional"))
      (node (ref "SOL_BANK_2") (pin "P$9") (pinfunction "PIN8_P$9") (pintype "bidirectional"))
      (node (ref "SOL_PWR_22") (pin "P$1") (pinfunction "P$1_P$1") (pintype "bidirectional"))
    )
    (net (code "277") (name "/SOL_PWR_23") (class "Default")
      (node (ref "SOL_23") (pin "D") (pinfunction "DRAIN_D") (pintype "bidirectional"))
      (node (ref "SOL_BANK_2") (pin "P$10") (pinfunction "PIN9_P$10") (pintype "bidirectional"))
      (node (ref "SOL_PWR_23") (pin "P$1") (pinfunction "P$1_P$1") (pintype "bidirectional"))
    )
    (net (code "278") (name "/ST_BU") (class "Default")
      (node (ref "R148") (pin "2") (pinfunction "2_2") (pintype "passive"))
      (node (ref "R38") (pin "1") (pinfunction "1_1") (pintype "passive"))
      (node (ref "U11") (pin "14") (pinfunction "D3_14") (pintype "bidirectional"))
    )
    (net (code "279") (name "/ST_BU_OUT") (class "Default")
      (node (ref "CABINET_I/O") (pin "P$4") (pinfunction "4_P$4") (pintype "bidirectional"))
      (node (ref "R148") (pin "1") (pinfunction "1_1") (pintype "passive"))
      (node (ref "ST_BU_OUT") (pin "P$1") (pinfunction "P$1_P$1") (pintype "bidirectional"))
    )
    (net (code "280") (name "/ST_LI") (class "Default")
      (node (ref "CABINET_I/O") (pin "P$3") (pinfunction "3_P$3") (pintype "bidirectional"))
      (node (ref "ST_LI") (pin "D") (pinfunction "COLLECTOR_D") (pintype "bidirectional"))
      (node (ref "ST_LI_") (pin "P$1") (pinfunction "P$1_P$1") (pintype "bidirectional"))
    )
    (net (code "281") (name "/ST_LI_GATE") (class "Default")
      (node (ref "IC2") (pin "59") (pinfunction "SDA2/RA3_59") (pintype "bidirectional"))
      (node (ref "R116") (pin "2") (pinfunction "2_2") (pintype "passive"))
    )
    (net (code "282") (name "/SW_C_0") (class "Default")
      (node (ref "IC4") (pin "18") (pinfunction "Y1_18") (pintype "tri_state"))
      (node (ref "SW_COL") (pin "P$10") (pinfunction "PIN9_P$10") (pintype "bidirectional"))
      (node (ref "SW_C_0") (pin "P$1") (pinfunction "P$1_P$1") (pintype "bidirectional"))
    )
    (net (code "283") (name "/SW_C_1") (class "Default")
      (node (ref "IC4") (pin "3") (pinfunction "Y4_3") (pintype "tri_state"))
      (node (ref "SW_COL") (pin "P$9") (pinfunction "PIN8_P$9") (pintype "bidirectional"))
      (node (ref "SW_C_1") (pin "P$1") (pinfunction "P$1_P$1") (pintype "bidirectional"))
    )
    (net (code "284") (name "/SW_C_2") (class "Default")
      (node (ref "IC4") (pin "16") (pinfunction "Y2_16") (pintype "tri_state"))
      (node (ref "SW_COL") (pin "P$8") (pinfunction "PIN7_P$8") (pintype "bidirectional"))
      (node (ref "SW_C_2") (pin "P$1") (pinfunction "P$1_P$1") (pintype "bidirectional"))
    )
    (net (code "285") (name "/SW_C_3") (class "Default")
      (node (ref "IC4") (pin "5") (pinfunction "Y3_5") (pintype "tri_state"))
      (node (ref "SW_COL") (pin "P$7") (pinfunction "PIN6_P$7") (pintype "bidirectional"))
      (node (ref "SW_C_3") (pin "P$1") (pinfunction "P$1_P$1") (pintype "bidirectional"))
    )
    (net (code "286") (name "/SW_C_4") (class "Default")
      (node (ref "IC4") (pin "14") (pinfunction "Y3_14") (pintype "tri_state"))
      (node (ref "SW_COL") (pin "P$6") (pinfunction "PIN5_P$6") (pintype "bidirectional"))
      (node (ref "SW_C_4") (pin "P$1") (pinfunction "P$1_P$1") (pintype "bidirectional"))
    )
    (net (code "287") (name "/SW_C_5") (class "Default")
      (node (ref "IC4") (pin "7") (pinfunction "Y2_7") (pintype "tri_state"))
      (node (ref "SW_COL") (pin "P$4") (pinfunction "PIN4_P$4") (pintype "bidirectional"))
      (node (ref "SW_C_5") (pin "P$1") (pinfunction "P$1_P$1") (pintype "bidirectional"))
    )
    (net (code "288") (name "/SW_C_6") (class "Default")
      (node (ref "IC4") (pin "12") (pinfunction "Y4_12") (pintype "tri_state"))
      (node (ref "SW_COL") (pin "P$3") (pinfunction "PIN3_P$3") (pintype "bidirectional"))
      (node (ref "SW_C_6") (pin "P$1") (pinfunction "P$1_P$1") (pintype "bidirectional"))
    )
    (net (code "289") (name "/SW_C_7") (class "Default")
      (node (ref "IC4") (pin "9") (pinfunction "Y1_9") (pintype "tri_state"))
      (node (ref "SW_COL") (pin "P$2") (pinfunction "PIN2_P$2") (pintype "bidirectional"))
      (node (ref "SW_C_7") (pin "P$1") (pinfunction "P$1_P$1") (pintype "bidirectional"))
    )
    (net (code "290") (name "/SW_R_0") (class "Default")
      (node (ref "IC3") (pin "2") (pinfunction "A1_2") (pintype "input"))
      (node (ref "R82") (pin "1") (pinfunction "1_1") (pintype "passive"))
      (node (ref "SW_ROW") (pin "P$10") (pinfunction "PIN9_P$10") (pintype "bidirectional"))
      (node (ref "SW_R_0") (pin "P$1") (pinfunction "P$1_P$1") (pintype "bidirectional"))
    )
    (net (code "291") (name "/SW_R_1") (class "Default")
      (node (ref "IC3") (pin "17") (pinfunction "A4_17") (pintype "input"))
      (node (ref "R81") (pin "1") (pinfunction "1_1") (pintype "passive"))
      (node (ref "SW_ROW") (pin "P$9") (pinfunction "PIN8_P$9") (pintype "bidirectional"))
      (node (ref "SW_R_1") (pin "P$1") (pinfunction "P$1_P$1") (pintype "bidirectional"))
    )
    (net (code "292") (name "/SW_R_2") (class "Default")
      (node (ref "IC3") (pin "4") (pinfunction "A2_4") (pintype "input"))
      (node (ref "R80") (pin "1") (pinfunction "1_1") (pintype "passive"))
      (node (ref "SW_ROW") (pin "P$8") (pinfunction "PIN7_P$8") (pintype "bidirectional"))
      (node (ref "SW_R_2") (pin "P$1") (pinfunction "P$1_P$1") (pintype "bidirectional"))
    )
    (net (code "293") (name "/SW_R_3") (class "Default")
      (node (ref "IC3") (pin "15") (pinfunction "A3_15") (pintype "input"))
      (node (ref "R79") (pin "1") (pinfunction "1_1") (pintype "passive"))
      (node (ref "SW_ROW") (pin "P$7") (pinfunction "PIN6_P$7") (pintype "bidirectional"))
      (node (ref "SW_R_3") (pin "P$1") (pinfunction "P$1_P$1") (pintype "bidirectional"))
    )
    (net (code "294") (name "/SW_R_4") (class "Default")
      (node (ref "IC3") (pin "6") (pinfunction "A3_6") (pintype "input"))
      (node (ref "R78") (pin "2") (pinfunction "2_2") (pintype "passive"))
      (node (ref "SW_ROW") (pin "P$6") (pinfunction "PIN5_P$6") (pintype "bidirectional"))
      (node (ref "SW_R_4") (pin "P$1") (pinfunction "P$1_P$1") (pintype "bidirectional"))
    )
    (net (code "295") (name "/SW_R_5") (class "Default")
      (node (ref "IC3") (pin "13") (pinfunction "A2_13") (pintype "input"))
      (node (ref "R77") (pin "2") (pinfunction "2_2") (pintype "passive"))
      (node (ref "SW_ROW") (pin "P$5") (pinfunction "PIN4_P$5") (pintype "bidirectional"))
      (node (ref "SW_R_5") (pin "P$1") (pinfunction "P$1_P$1") (pintype "bidirectional"))
    )
    (net (code "296") (name "/SW_R_6") (class "Default")
      (node (ref "IC3") (pin "8") (pinfunction "A4_8") (pintype "input"))
      (node (ref "R76") (pin "2") (pinfunction "2_2") (pintype "passive"))
      (node (ref "SW_ROW") (pin "P$3") (pinfunction "PIN3_P$3") (pintype "bidirectional"))
      (node (ref "SW_R_6") (pin "P$1") (pinfunction "P$1_P$1") (pintype "bidirectional"))
    )
    (net (code "297") (name "/SW_R_7") (class "Default")
      (node (ref "IC3") (pin "11") (pinfunction "A1_11") (pintype "input"))
      (node (ref "R75") (pin "2") (pinfunction "2_2") (pintype "passive"))
      (node (ref "SW_ROW") (pin "P$2") (pinfunction "PIN2_P$2") (pintype "bidirectional"))
      (node (ref "SW_R_7") (pin "P$1") (pinfunction "P$1_P$1") (pintype "bidirectional"))
    )
    (net (code "298") (name "/S_L") (class "Default")
      (node (ref "AUDIO") (pin "2_A") (pinfunction "T_2_A") (pintype "bidirectional"))
      (node (ref "AUDIO") (pin "2_B") (pinfunction "T_2_B") (pintype "bidirectional"))
      (node (ref "R32") (pin "2") (pinfunction "2_2") (pintype "passive"))
      (node (ref "S_L") (pin "P$1") (pinfunction "P$1_P$1") (pintype "bidirectional"))
    )
    (net (code "299") (name "/S_R") (class "Default")
      (node (ref "AUDIO") (pin "3_A") (pinfunction "R_3_A") (pintype "bidirectional"))
      (node (ref "AUDIO") (pin "3_B") (pinfunction "R_3_B") (pintype "bidirectional"))
      (node (ref "R34") (pin "2") (pinfunction "2_2") (pintype "passive"))
      (node (ref "S_R") (pin "P$1") (pinfunction "P$1_P$1") (pintype "bidirectional"))
    )
    (net (code "300") (name "/TILT") (class "Default")
      (node (ref "R149") (pin "2") (pinfunction "2_2") (pintype "passive"))
      (node (ref "R50") (pin "1") (pinfunction "1_1") (pintype "passive"))
      (node (ref "U12") (pin "6") (pinfunction "D7_6") (pintype "bidirectional"))
    )
    (net (code "301") (name "/TILT_OUT") (class "Default")
      (node (ref "CABINET_I/O") (pin "P$5") (pinfunction "5_P$5") (pintype "bidirectional"))
      (node (ref "R149") (pin "1") (pinfunction "1_1") (pintype "passive"))
      (node (ref "TILT_OUT") (pin "P$1") (pinfunction "P$1_P$1") (pintype "bidirectional"))
    )
    (net (code "302") (name "/TX_PIC32") (class "Default")
      (node (ref "IC2") (pin "53") (pinfunction "SCL1A/SDO1A/U1ATX/RF8_53") (pintype "bidirectional"))
      (node (ref "PIC32_TC") (pin "P$3") (pinfunction "PIN3_P$3") (pintype "bidirectional"))
      (node (ref "PIC32_UART") (pin "5") (pinfunction "5_5") (pintype "passive"))
    )
    (net (code "303") (name "/TX_PROP") (class "Default")
      (node (ref "PROP_TC") (pin "P$3") (pinfunction "PIN3_P$3") (pintype "bidirectional"))
      (node (ref "PROP_UART") (pin "5") (pinfunction "5_5") (pintype "passive"))
      (node (ref "U1") (pin "37") (pinfunction "P30_37") (pintype "bidirectional"))
    )
    (net (code "304") (name "/USBD+") (class "Default")
      (node (ref "IC2") (pin "57") (pinfunction "D+/RG2_57") (pintype "bidirectional"))
      (node (ref "USB_PROG") (pin "3") (pinfunction "3_3") (pintype "passive"))
    )
    (net (code "305") (name "/USBD-") (class "Default")
      (node (ref "IC2") (pin "56") (pinfunction "D-/RG3_56") (pintype "bidirectional"))
      (node (ref "USB_PROG") (pin "2") (pinfunction "2_2") (pintype "passive"))
    )
    (net (code "306") (name "/USER_0") (class "Default")
      (node (ref "R154") (pin "2") (pinfunction "2_2") (pintype "passive"))
      (node (ref "R44") (pin "1") (pinfunction "1_1") (pintype "passive"))
      (node (ref "U12") (pin "12") (pinfunction "D1_12") (pintype "bidirectional"))
    )
    (net (code "307") (name "/USER_0_OUT") (class "Default")
      (node (ref "CABINET_I/O") (pin "P$10") (pinfunction "10_P$10") (pintype "bidirectional"))
      (node (ref "R154") (pin "1") (pinfunction "1_1") (pintype "passive"))
      (node (ref "USER_0_OUT") (pin "P$1") (pinfunction "P$1_P$1") (pintype "bidirectional"))
    )
    (net (code "308") (name "/VUSB") (class "Default")
      (node (ref "IC2") (pin "54") (pinfunction "VBUS_54") (pintype "bidirectional"))
      (node (ref "USB_PROG") (pin "1") (pinfunction "1_1") (pintype "passive"))
    )
    (net (code "309") (name "/WATCHDOG") (class "Default")
      (node (ref "R135") (pin "1") (pinfunction "1_1") (pintype "passive"))
      (node (ref "U14") (pin "1") (pinfunction "A1_1") (pintype "bidirectional"))
      (node (ref "U14") (pin "12") (pinfunction "A4_12") (pintype "bidirectional"))
      (node (ref "U14") (pin "4") (pinfunction "A2_4") (pintype "bidirectional"))
      (node (ref "U14") (pin "9") (pinfunction "A3_9") (pintype "bidirectional"))
      (node (ref "U15") (pin "1") (pinfunction "A1_1") (pintype "bidirectional"))
      (node (ref "U15") (pin "12") (pinfunction "A4_12") (pintype "bidirectional"))
      (node (ref "U15") (pin "4") (pinfunction "A2_4") (pintype "bidirectional"))
      (node (ref "U15") (pin "9") (pinfunction "A3_9") (pintype "bidirectional"))
      (node (ref "U16") (pin "1") (pinfunction "A1_1") (pintype "bidirectional"))
      (node (ref "U16") (pin "12") (pinfunction "A4_12") (pintype "bidirectional"))
      (node (ref "U16") (pin "4") (pinfunction "A2_4") (pintype "bidirectional"))
      (node (ref "U16") (pin "9") (pinfunction "A3_9") (pintype "bidirectional"))
      (node (ref "U17") (pin "1") (pinfunction "A1_1") (pintype "bidirectional"))
      (node (ref "U17") (pin "12") (pinfunction "A4_12") (pintype "bidirectional"))
      (node (ref "U17") (pin "4") (pinfunction "A2_4") (pintype "bidirectional"))
      (node (ref "U17") (pin "9") (pinfunction "A3_9") (pintype "bidirectional"))
      (node (ref "U18") (pin "1") (pinfunction "A1_1") (pintype "bidirectional"))
      (node (ref "U18") (pin "12") (pinfunction "A4_12") (pintype "bidirectional"))
      (node (ref "U18") (pin "4") (pinfunction "A2_4") (pintype "bidirectional"))
      (node (ref "U18") (pin "9") (pinfunction "A3_9") (pintype "bidirectional"))
      (node (ref "U19") (pin "1") (pinfunction "A1_1") (pintype "bidirectional"))
      (node (ref "U19") (pin "12") (pinfunction "A4_12") (pintype "bidirectional"))
      (node (ref "U19") (pin "4") (pinfunction "A2_4") (pintype "bidirectional"))
      (node (ref "U19") (pin "9") (pinfunction "A3_9") (pintype "bidirectional"))
      (node (ref "U52") (pin "13") (pinfunction "1Q_13") (pintype "bidirectional"))
      (node (ref "WD") (pin "ANODE") (pinfunction "ANODE_ANODE") (pintype "bidirectional"))
    )
    (net (code "310") (name "/WATCHDOG_ADJUST") (class "Default")
      (node (ref "C27") (pin "POS") (pinfunction "POS_POS") (pintype "bidirectional"))
      (node (ref "D2") (pin "2") (pinfunction "ANODE_2") (pintype "bidirectional"))
      (node (ref "R134") (pin "1") (pinfunction "1_1") (pintype "passive"))
      (node (ref "U52") (pin "15") (pinfunction "1RXCX_15") (pintype "bidirectional"))
    )
    (net (code "311") (name "/X0") (class "Default")
      (node (ref "U1") (pin "29") (pinfunction "X0_29") (pintype "bidirectional"))
      (node (ref "X2") (pin "P$1") (pinfunction "P$1_P$1") (pintype "bidirectional"))
    )
    (net (code "312") (name "/X1") (class "Default")
      (node (ref "U1") (pin "28") (pinfunction "X1_28") (pintype "bidirectional"))
      (node (ref "X2") (pin "P$2") (pinfunction "P$2_P$2") (pintype "bidirectional"))
    )
    (net (code "313") (name "/~{DATA_LAT}") (class "Default")
      (node (ref "U10") (pin "6") (pinfunction "1Y_6") (pintype "bidirectional"))
      (node (ref "U3") (pin "12") (pinfunction "STCP_12") (pintype "bidirectional"))
      (node (ref "U5") (pin "12") (pinfunction "STCP_12") (pintype "bidirectional"))
    )
    (net (code "314") (name "Net-(D1-COM)") (class "Default")
      (node (ref "D1") (pin "3") (pinfunction "COM_3") (pintype "bidirectional"))
      (node (ref "IC2") (pin "13") (pinfunction "MCLR_13") (pintype "bidirectional"))
      (node (ref "R12") (pin "1") (pinfunction "1_1") (pintype "passive"))
    )
    (net (code "315") (name "Net-(D5-PadCATHODE)") (class "Default")
      (node (ref "D5") (pin "CATHODE") (pinfunction "CATHODE_CATHODE") (pintype "power_in"))
      (node (ref "R159") (pin "1") (pinfunction "1_1") (pintype "passive"))
    )
    (net (code "316") (name "Net-(D6-PadCATHODE)") (class "Default")
      (node (ref "D6") (pin "CATHODE") (pinfunction "CATHODE_CATHODE") (pintype "power_in"))
      (node (ref "R160") (pin "1") (pinfunction "1_1") (pintype "passive"))
    )
    (net (code "317") (name "Net-(D7-PadCATHODE)") (class "Default")
      (node (ref "D7") (pin "CATHODE") (pinfunction "CATHODE_CATHODE") (pintype "power_in"))
      (node (ref "R161") (pin "1") (pinfunction "1_1") (pintype "passive"))
    )
    (net (code "318") (name "Net-(D8-PadCATHODE)") (class "Default")
      (node (ref "D8") (pin "CATHODE") (pinfunction "CATHODE_CATHODE") (pintype "power_in"))
      (node (ref "R162") (pin "1") (pinfunction "1_1") (pintype "passive"))
    )
    (net (code "319") (name "Net-(D9-PadCATHODE)") (class "Default")
      (node (ref "D9") (pin "CATHODE") (pinfunction "CATHODE_CATHODE") (pintype "power_in"))
      (node (ref "R163") (pin "1") (pinfunction "1_1") (pintype "passive"))
    )
    (net (code "320") (name "Net-(D10-PadCATHODE)") (class "Default")
      (node (ref "D10") (pin "CATHODE") (pinfunction "CATHODE_CATHODE") (pintype "power_in"))
      (node (ref "R164") (pin "1") (pinfunction "1_1") (pintype "passive"))
    )
    (net (code "321") (name "Net-(D11-PadCATHODE)") (class "Default")
      (node (ref "D11") (pin "CATHODE") (pinfunction "CATHODE_CATHODE") (pintype "power_in"))
      (node (ref "R165") (pin "1") (pinfunction "1_1") (pintype "passive"))
    )
    (net (code "322") (name "Net-(GI0-BASE)") (class "Default")
      (node (ref "GI0") (pin "G") (pinfunction "BASE_G") (pintype "bidirectional"))
      (node (ref "R99") (pin "2") (pinfunction "2_2") (pintype "passive"))
    )
    (net (code "323") (name "Net-(GI1-BASE)") (class "Default")
      (node (ref "GI1") (pin "G") (pinfunction "BASE_G") (pintype "bidirectional"))
      (node (ref "R101") (pin "2") (pinfunction "2_2") (pintype "passive"))
    )
    (net (code "324") (name "Net-(GI2-BASE)") (class "Default")
      (node (ref "GI2") (pin "G") (pinfunction "BASE_G") (pintype "bidirectional"))
      (node (ref "R103") (pin "2") (pinfunction "2_2") (pintype "passive"))
    )
    (net (code "325") (name "Net-(GI3-BASE)") (class "Default")
      (node (ref "GI3") (pin "G") (pinfunction "BASE_G") (pintype "bidirectional"))
      (node (ref "R105") (pin "2") (pinfunction "2_2") (pintype "passive"))
    )
    (net (code "326") (name "Net-(GI4-BASE)") (class "Default")
      (node (ref "GI4") (pin "G") (pinfunction "BASE_G") (pintype "bidirectional"))
      (node (ref "R107") (pin "2") (pinfunction "2_2") (pintype "passive"))
    )
    (net (code "327") (name "Net-(GI5-BASE)") (class "Default")
      (node (ref "GI5") (pin "G") (pinfunction "BASE_G") (pintype "bidirectional"))
      (node (ref "R109") (pin "2") (pinfunction "2_2") (pintype "passive"))
    )
    (net (code "328") (name "Net-(GI6-BASE)") (class "Default")
      (node (ref "GI6") (pin "G") (pinfunction "BASE_G") (pintype "bidirectional"))
      (node (ref "R111") (pin "2") (pinfunction "2_2") (pintype "passive"))
    )
    (net (code "329") (name "Net-(GI7-BASE)") (class "Default")
      (node (ref "GI7") (pin "G") (pinfunction "BASE_G") (pintype "bidirectional"))
      (node (ref "R113") (pin "2") (pinfunction "2_2") (pintype "passive"))
    )
    (net (code "330") (name "Net-(GI8-BASE)") (class "Default")
      (node (ref "GI8") (pin "G") (pinfunction "BASE_G") (pintype "bidirectional"))
      (node (ref "R125") (pin "2") (pinfunction "2_2") (pintype "passive"))
    )
    (net (code "331") (name "Net-(GI9-BASE)") (class "Default")
      (node (ref "GI9") (pin "G") (pinfunction "BASE_G") (pintype "bidirectional"))
      (node (ref "R126") (pin "2") (pinfunction "2_2") (pintype "passive"))
    )
    (net (code "332") (name "Net-(GI10-BASE)") (class "Default")
      (node (ref "GI10") (pin "G") (pinfunction "BASE_G") (pintype "bidirectional"))
      (node (ref "R127") (pin "2") (pinfunction "2_2") (pintype "passive"))
    )
    (net (code "333") (name "Net-(GI11-BASE)") (class "Default")
      (node (ref "GI11") (pin "G") (pinfunction "BASE_G") (pintype "bidirectional"))
      (node (ref "R128") (pin "2") (pinfunction "2_2") (pintype "passive"))
    )
    (net (code "334") (name "Net-(GI12-BASE)") (class "Default")
      (node (ref "GI12") (pin "G") (pinfunction "BASE_G") (pintype "bidirectional"))
      (node (ref "R129") (pin "2") (pinfunction "2_2") (pintype "passive"))
    )
    (net (code "335") (name "Net-(GI13-BASE)") (class "Default")
      (node (ref "GI13") (pin "G") (pinfunction "BASE_G") (pintype "bidirectional"))
      (node (ref "R130") (pin "2") (pinfunction "2_2") (pintype "passive"))
    )
    (net (code "336") (name "Net-(GI14-BASE)") (class "Default")
      (node (ref "GI14") (pin "G") (pinfunction "BASE_G") (pintype "bidirectional"))
      (node (ref "R131") (pin "2") (pinfunction "2_2") (pintype "passive"))
    )
    (net (code "337") (name "Net-(GI15-BASE)") (class "Default")
      (node (ref "GI15") (pin "G") (pinfunction "BASE_G") (pintype "bidirectional"))
      (node (ref "R132") (pin "2") (pinfunction "2_2") (pintype "passive"))
    )
    (net (code "338") (name "Net-(IC2A-VCAP{slash}VDDCORE)") (class "Default")
      (node (ref "C10") (pin "1") (pinfunction "1_1") (pintype "passive"))
      (node (ref "IC2") (pin "85") (pinfunction "VCAP/VDDCORE_85") (pintype "bidirectional"))
    )
    (net (code "339") (name "Net-(IC2D-OSC1{slash}CLKI{slash}RC12)") (class "Default")
      (node (ref "C14") (pin "1") (pinfunction "1_1") (pintype "passive"))
      (node (ref "IC2") (pin "63") (pinfunction "OSC1/CLKI/RC12_63") (pintype "bidirectional"))
      (node (ref "X1") (pin "3") (pinfunction "2_3") (pintype "passive"))
    )
    (net (code "340") (name "Net-(IC2D-OSC2{slash}CLKO{slash}RC15)") (class "Default")
      (node (ref "C13") (pin "1") (pinfunction "1_1") (pintype "passive"))
      (node (ref "IC2") (pin "64") (pinfunction "OSC2/CLKO/RC15_64") (pintype "bidirectional"))
      (node (ref "X1") (pin "1") (pinfunction "1_1") (pintype "passive"))
    )
    (net (code "341") (name "Net-(OPTO_1-Pad4)") (class "Default")
      (node (ref "OPTO_1") (pin "4") (pinfunction "4_4") (pintype "passive"))
      (node (ref "R139") (pin "2") (pinfunction "2_2") (pintype "passive"))
    )
    (net (code "342") (name "Net-(OPTO_2-Pad4)") (class "Default")
      (node (ref "OPTO_2") (pin "4") (pinfunction "4_4") (pintype "passive"))
      (node (ref "R140") (pin "2") (pinfunction "2_2") (pintype "passive"))
    )
    (net (code "343") (name "Net-(OPTO_3-Pad4)") (class "Default")
      (node (ref "OPTO_3") (pin "4") (pinfunction "4_4") (pintype "passive"))
      (node (ref "R141") (pin "2") (pinfunction "2_2") (pintype "passive"))
    )
    (net (code "344") (name "Net-(OPTO_4-Pad4)") (class "Default")
      (node (ref "OPTO_4") (pin "4") (pinfunction "4_4") (pintype "passive"))
      (node (ref "R142") (pin "2") (pinfunction "2_2") (pintype "passive"))
    )
    (net (code "345") (name "Net-(OPTO_5-Pad4)") (class "Default")
      (node (ref "OPTO_5") (pin "4") (pinfunction "4_4") (pintype "passive"))
      (node (ref "R143") (pin "2") (pinfunction "2_2") (pintype "passive"))
    )
    (net (code "346") (name "Net-(OPTO_6-Pad4)") (class "Default")
      (node (ref "OPTO_6") (pin "4") (pinfunction "4_4") (pintype "passive"))
      (node (ref "R144") (pin "2") (pinfunction "2_2") (pintype "passive"))
    )
    (net (code "347") (name "Net-(OPTO_7-Pad4)") (class "Default")
      (node (ref "OPTO_7") (pin "4") (pinfunction "4_4") (pintype "passive"))
      (node (ref "R145") (pin "2") (pinfunction "2_2") (pintype "passive"))
    )
    (net (code "348") (name "Net-(PIC32_TC-PIN6)") (class "Default")
      (node (ref "PIC32_TC") (pin "P$6") (pinfunction "PIN6_P$6") (pintype "bidirectional"))
      (node (ref "PIC32_UART") (pin "6") (pinfunction "6_6") (pintype "passive"))
      (node (ref "R26") (pin "1") (pinfunction "1_1") (pintype "passive"))
    )
    (net (code "349") (name "Net-(PIC_RESET-PadP$4)") (class "Default")
      (node (ref "PIC_RESET") (pin "P$4") (pinfunction "P$4_P$4") (pintype "bidirectional"))
      (node (ref "R8") (pin "1") (pinfunction "1_1") (pintype "passive"))
    )
    (net (code "350") (name "Net-(PROP_ACT-PadCATHODE)") (class "Default")
      (node (ref "PROP_ACT") (pin "CATHODE") (pinfunction "CATHODE_CATHODE") (pintype "bidirectional"))
      (node (ref "R30") (pin "2") (pinfunction "2_2") (pintype "passive"))
    )
    (net (code "351") (name "Net-(PROP_TC-PIN6)") (class "Default")
      (node (ref "C1") (pin "1") (pinfunction "1_1") (pintype "passive"))
      (node (ref "PROP_TC") (pin "P$6") (pinfunction "PIN6_P$6") (pintype "bidirectional"))
      (node (ref "PROP_UART") (pin "6") (pinfunction "6_6") (pintype "passive"))
    )
    (net (code "352") (name "Net-(PSU_PWR-PadCATHODE)") (class "Default")
      (node (ref "PSU_PWR") (pin "CATHODE") (pinfunction "CATHODE_CATHODE") (pintype "bidirectional"))
      (node (ref "R117") (pin "2") (pinfunction "2_2") (pintype "passive"))
    )
    (net (code "353") (name "Net-(R118-Pad1)") (class "Default")
      (node (ref "R118") (pin "1") (pinfunction "1_1") (pintype "passive"))
      (node (ref "WD") (pin "CATHODE") (pinfunction "CATHODE_CATHODE") (pintype "bidirectional"))
    )
    (net (code "354") (name "Net-(RGB_0-GATE)") (class "Default")
      (node (ref "R119") (pin "1") (pinfunction "1_1") (pintype "passive"))
      (node (ref "RGB_0") (pin "G") (pinfunction "GATE_G") (pintype "bidirectional"))
      (node (ref "U38") (pin "8") (pinfunction "BOUT_8") (pintype "bidirectional"))
    )
    (net (code "355") (name "Net-(RGB_1-GATE)") (class "Default")
      (node (ref "R120") (pin "1") (pinfunction "1_1") (pintype "passive"))
      (node (ref "RGB_1") (pin "G") (pinfunction "GATE_G") (pintype "bidirectional"))
      (node (ref "U38") (pin "9") (pinfunction "GOUT_9") (pintype "bidirectional"))
    )
    (net (code "356") (name "Net-(RGB_2-GATE)") (class "Default")
      (node (ref "R121") (pin "1") (pinfunction "1_1") (pintype "passive"))
      (node (ref "RGB_2") (pin "G") (pinfunction "GATE_G") (pintype "bidirectional"))
      (node (ref "U38") (pin "10") (pinfunction "ROUT_10") (pintype "bidirectional"))
    )
    (net (code "357") (name "Net-(RGB_3-GATE)") (class "Default")
      (node (ref "R122") (pin "1") (pinfunction "1_1") (pintype "passive"))
      (node (ref "RGB_3") (pin "G") (pinfunction "GATE_G") (pintype "bidirectional"))
      (node (ref "U36") (pin "8") (pinfunction "BOUT_8") (pintype "bidirectional"))
    )
    (net (code "358") (name "Net-(RGB_4-GATE)") (class "Default")
      (node (ref "R123") (pin "1") (pinfunction "1_1") (pintype "passive"))
      (node (ref "RGB_4") (pin "G") (pinfunction "GATE_G") (pintype "bidirectional"))
      (node (ref "U36") (pin "9") (pinfunction "GOUT_9") (pintype "bidirectional"))
    )
    (net (code "359") (name "Net-(RGB_5-GATE)") (class "Default")
      (node (ref "R124") (pin "1") (pinfunction "1_1") (pintype "passive"))
      (node (ref "RGB_5") (pin "G") (pinfunction "GATE_G") (pintype "bidirectional"))
      (node (ref "U36") (pin "10") (pinfunction "ROUT_10") (pintype "bidirectional"))
    )
    (net (code "360") (name "Net-(SD0-IRQ)") (class "Default")
      (node (ref "R21") (pin "2") (pinfunction "2_2") (pintype "passive"))
      (node (ref "SD0") (pin "8") (pinfunction "IRQ_8") (pintype "bidirectional"))
    )
    (net (code "361") (name "Net-(SD0-RW)") (class "Default")
      (node (ref "R23") (pin "2") (pinfunction "2_2") (pintype "passive"))
      (node (ref "SD0") (pin "9") (pinfunction "RW_9") (pintype "bidirectional"))
    )
    (net (code "362") (name "Net-(ST_LI-BASE)") (class "Default")
      (node (ref "R115") (pin "2") (pinfunction "2_2") (pintype "passive"))
      (node (ref "ST_LI") (pin "G") (pinfunction "BASE_G") (pintype "bidirectional"))
      (node (ref "U8") (pin "P$3") (pinfunction "COLLECTOR_P$3") (pintype "bidirectional"))
    )
    (net (code "363") (name "Net-(U2-X1)") (class "Default")
      (node (ref "U2") (pin "1") (pinfunction "X1_1") (pintype "bidirectional"))
      (node (ref "X3") (pin "1") (pinfunction "P$1_1") (pintype "bidirectional"))
    )
    (net (code "364") (name "Net-(U2-X2)") (class "Default")
      (node (ref "U2") (pin "2") (pinfunction "X2_2") (pintype "bidirectional"))
      (node (ref "X3") (pin "4") (pinfunction "P$2_4") (pintype "bidirectional"))
    )
    (net (code "365") (name "Net-(U6-DV{slash}DT)") (class "Default")
      (node (ref "C59") (pin "1") (pinfunction "1_1") (pintype "passive"))
      (node (ref "U6") (pin "P$1") (pinfunction "DV/DT_P$1") (pintype "bidirectional"))
    )
    (net (code "366") (name "Net-(U6-EN{slash}UVLO)") (class "Default")
      (node (ref "R147") (pin "2") (pinfunction "2_2") (pintype "passive"))
      (node (ref "U6") (pin "P$2") (pinfunction "EN/UVLO_P$2") (pintype "bidirectional"))
    )
    (net (code "367") (name "Net-(U6-ILIM)") (class "Default")
      (node (ref "R146") (pin "1") (pinfunction "1_1") (pintype "passive"))
      (node (ref "U6") (pin "P$10") (pinfunction "ILIM_P$10") (pintype "bidirectional"))
    )
    (net (code "368") (name "Net-(U7-DV{slash}DT)") (class "Default")
      (node (ref "C61") (pin "1") (pinfunction "1_1") (pintype "passive"))
      (node (ref "U7") (pin "P$1") (pinfunction "DV/DT_P$1") (pintype "bidirectional"))
    )
    (net (code "369") (name "Net-(U7-EN{slash}UVLO)") (class "Default")
      (node (ref "R158") (pin "2") (pinfunction "2_2") (pintype "passive"))
      (node (ref "U7") (pin "P$2") (pinfunction "EN/UVLO_P$2") (pintype "bidirectional"))
    )
    (net (code "370") (name "Net-(U7-ILIM)") (class "Default")
      (node (ref "R157") (pin "1") (pinfunction "1_1") (pintype "passive"))
      (node (ref "U7") (pin "P$10") (pinfunction "ILIM_P$10") (pintype "bidirectional"))
    )
    (net (code "371") (name "Net-(U8-BASE)") (class "Default")
      (node (ref "R116") (pin "1") (pinfunction "1_1") (pintype "passive"))
      (node (ref "U8") (pin "P$1") (pinfunction "BASE_P$1") (pintype "bidirectional"))
    )
    (net (code "372") (name "Net-(U28-BASE)") (class "Default")
      (node (ref "R100") (pin "2") (pinfunction "2_2") (pintype "passive"))
      (node (ref "U28") (pin "G") (pinfunction "BASE_G") (pintype "bidirectional"))
    )
    (net (code "373") (name "Net-(U29-BASE)") (class "Default")
      (node (ref "R102") (pin "2") (pinfunction "2_2") (pintype "passive"))
      (node (ref "U29") (pin "G") (pinfunction "BASE_G") (pintype "bidirectional"))
    )
    (net (code "374") (name "Net-(U30-BASE)") (class "Default")
      (node (ref "R104") (pin "2") (pinfunction "2_2") (pintype "passive"))
      (node (ref "U30") (pin "G") (pinfunction "BASE_G") (pintype "bidirectional"))
    )
    (net (code "375") (name "Net-(U31-BASE)") (class "Default")
      (node (ref "R106") (pin "2") (pinfunction "2_2") (pintype "passive"))
      (node (ref "U31") (pin "G") (pinfunction "BASE_G") (pintype "bidirectional"))
    )
    (net (code "376") (name "Net-(U32-BASE)") (class "Default")
      (node (ref "R108") (pin "2") (pinfunction "2_2") (pintype "passive"))
      (node (ref "U32") (pin "G") (pinfunction "BASE_G") (pintype "bidirectional"))
    )
    (net (code "377") (name "Net-(U33-BASE)") (class "Default")
      (node (ref "R110") (pin "2") (pinfunction "2_2") (pintype "passive"))
      (node (ref "U33") (pin "G") (pinfunction "BASE_G") (pintype "bidirectional"))
    )
    (net (code "378") (name "Net-(U34-BASE)") (class "Default")
      (node (ref "R112") (pin "2") (pinfunction "2_2") (pintype "passive"))
      (node (ref "U34") (pin "G") (pinfunction "BASE_G") (pintype "bidirectional"))
    )
    (net (code "379") (name "Net-(U35-BASE)") (class "Default")
      (node (ref "R114") (pin "2") (pinfunction "2_2") (pintype "passive"))
      (node (ref "U35") (pin "G") (pinfunction "BASE_G") (pintype "bidirectional"))
    )
    (net (code "380") (name "unconnected-(CAB_RGB-1-PadP$1)") (class "Default")
      (node (ref "CAB_RGB") (pin "P$1") (pinfunction "1_P$1") (pintype "bidirectional"))
    )
    (net (code "381") (name "unconnected-(CAB_RGB-2-PadP$2)") (class "Default")
      (node (ref "CAB_RGB") (pin "P$2") (pinfunction "2_P$2") (pintype "bidirectional"))
    )
    (net (code "382") (name "unconnected-(IC5-CD+-Pad10)") (class "Default")
      (node (ref "IC5") (pin "10") (pinfunction "CD+_10") (pintype "passive"))
    )
    (net (code "383") (name "unconnected-(LIGHT_COL-PIN1-PadP$1)") (class "Default")
      (node (ref "LIGHT_COL") (pin "P$1") (pinfunction "PIN1_P$1") (pintype "bidirectional"))
    )
    (net (code "384") (name "unconnected-(LIGHT_ROW-PIN1-PadP$1)") (class "Default")
      (node (ref "LIGHT_ROW") (pin "P$1") (pinfunction "PIN1_P$1") (pintype "bidirectional"))
    )
    (net (code "385") (name "unconnected-(PIC32_TC-PIN1-PadP$1)") (class "Default")
      (node (ref "PIC32_TC") (pin "P$1") (pinfunction "PIN1_P$1") (pintype "bidirectional"))
    )
    (net (code "386") (name "unconnected-(PIC32_TC-PIN2-PadP$2)") (class "Default")
      (node (ref "PIC32_TC") (pin "P$2") (pinfunction "PIN2_P$2") (pintype "bidirectional"))
    )
    (net (code "387") (name "unconnected-(PIC32_UART-Pad2)") (class "Default")
      (node (ref "PIC32_UART") (pin "2") (pinfunction "2_2") (pintype "passive"))
    )
    (net (code "388") (name "unconnected-(PIC32_UART-Pad3)") (class "Default")
      (node (ref "PIC32_UART") (pin "3") (pinfunction "3_3") (pintype "passive"))
    )
    (net (code "389") (name "unconnected-(PICKIT3-Pad6)") (class "Default")
      (node (ref "PICKIT3") (pin "6") (pinfunction "6_6") (pintype "passive"))
    )
    (net (code "390") (name "unconnected-(PICKIT3_TC-PIN6-PadP$6)") (class "Default")
      (node (ref "PICKIT3_TC") (pin "P$6") (pinfunction "PIN6_P$6") (pintype "bidirectional"))
    )
    (net (code "391") (name "unconnected-(PIC_PROGRAM-PadP$2)") (class "Default")
      (node (ref "PIC_PROGRAM") (pin "P$2") (pinfunction "P$2_P$2") (pintype "bidirectional"))
    )
    (net (code "392") (name "unconnected-(PIC_PROGRAM-PadP$3)") (class "Default")
      (node (ref "PIC_PROGRAM") (pin "P$3") (pinfunction "P$3_P$3") (pintype "bidirectional"))
    )
    (net (code "393") (name "unconnected-(PIC_RESET-PadP$2)") (class "Default")
      (node (ref "PIC_RESET") (pin "P$2") (pinfunction "P$2_P$2") (pintype "bidirectional"))
    )
    (net (code "394") (name "unconnected-(PIC_RESET-PadP$3)") (class "Default")
      (node (ref "PIC_RESET") (pin "P$3") (pinfunction "P$3_P$3") (pintype "bidirectional"))
    )
    (net (code "395") (name "unconnected-(PROP_CONFIG-PadP$2)") (class "Default")
      (node (ref "PROP_CONFIG") (pin "P$2") (pinfunction "P$2_P$2") (pintype "bidirectional"))
    )
    (net (code "396") (name "unconnected-(PROP_CONFIG-PadP$3)") (class "Default")
      (node (ref "PROP_CONFIG") (pin "P$3") (pinfunction "P$3_P$3") (pintype "bidirectional"))
    )
    (net (code "397") (name "unconnected-(PROP_RESET-PadP$1)") (class "Default")
      (node (ref "PROP_RESET") (pin "P$1") (pinfunction "P$1_P$1") (pintype "bidirectional"))
    )
    (net (code "398") (name "unconnected-(PROP_RESET-PadP$4)") (class "Default")
      (node (ref "PROP_RESET") (pin "P$4") (pinfunction "P$4_P$4") (pintype "bidirectional"))
    )
    (net (code "399") (name "unconnected-(PROP_TC-PIN1-PadP$1)") (class "Default")
      (node (ref "PROP_TC") (pin "P$1") (pinfunction "PIN1_P$1") (pintype "bidirectional"))
    )
    (net (code "400") (name "unconnected-(PROP_TC-PIN2-PadP$2)") (class "Default")
      (node (ref "PROP_TC") (pin "P$2") (pinfunction "PIN2_P$2") (pintype "bidirectional"))
    )
    (net (code "401") (name "unconnected-(PROP_UART-Pad2)") (class "Default")
      (node (ref "PROP_UART") (pin "2") (pinfunction "2_2") (pintype "passive"))
    )
    (net (code "402") (name "unconnected-(PROP_UART-Pad3)") (class "Default")
      (node (ref "PROP_UART") (pin "3") (pinfunction "3_3") (pintype "passive"))
    )
    (net (code "403") (name "unconnected-(SD0-CD-PadCARD_DETECT)") (class "Default")
      (node (ref "SD0") (pin "CARD_DETECT") (pinfunction "CD_CARD_DETECT") (pintype "bidirectional"))
    )
    (net (code "404") (name "unconnected-(SW_COL-PIN1-PadP$1)") (class "Default")
      (node (ref "SW_COL") (pin "P$1") (pinfunction "PIN1_P$1") (pintype "bidirectional"))
    )
    (net (code "405") (name "unconnected-(SW_ROW-PIN1-PadP$1)") (class "Default")
      (node (ref "SW_ROW") (pin "P$1") (pinfunction "PIN1_P$1") (pintype "bidirectional"))
    )
    (net (code "406") (name "unconnected-(U2-FT{slash}OUT-Pad7)") (class "Default")
      (node (ref "U2") (pin "7") (pinfunction "FT/OUT_7") (pintype "bidirectional"))
    )
    (net (code "407") (name "unconnected-(U4-A0-Pad1)") (class "Default")
      (node (ref "U4") (pin "1") (pinfunction "A0_1") (pintype "bidirectional"))
    )
    (net (code "408") (name "unconnected-(U5-Q7S-Pad9)") (class "Default")
      (node (ref "U5") (pin "9") (pinfunction "Q7S_9") (pintype "bidirectional"))
    )
    (net (code "409") (name "unconnected-(U10-2A-Pad3)") (class "Default")
      (node (ref "U10") (pin "3") (pinfunction "2A_3") (pintype "bidirectional"))
    )
    (net (code "410") (name "unconnected-(U10-2Y-Pad4)") (class "Default")
      (node (ref "U10") (pin "4") (pinfunction "2Y_4") (pintype "bidirectional"))
    )
    (net (code "411") (name "unconnected-(U11-QH'-Pad7)") (class "Default")
      (node (ref "U11") (pin "7") (pinfunction "QH'_7") (pintype "bidirectional"))
    )
    (net (code "412") (name "unconnected-(U12-QH'-Pad7)") (class "Default")
      (node (ref "U12") (pin "7") (pinfunction "QH'_7") (pintype "bidirectional"))
    )
    (net (code "413") (name "unconnected-(U12-SER-Pad10)") (class "Default")
      (node (ref "U12") (pin "10") (pinfunction "SER_10") (pintype "bidirectional"))
    )
    (net (code "414") (name "unconnected-(U13-A0-Pad1)") (class "Default")
      (node (ref "U13") (pin "1") (pinfunction "A0_1") (pintype "bidirectional"))
    )
    (net (code "415") (name "unconnected-(U52-2B-Pad10)") (class "Default")
      (node (ref "U52") (pin "10") (pinfunction "2B_10") (pintype "bidirectional"))
    )
    (net (code "416") (name "unconnected-(U52-2CX-Pad6)") (class "Default")
      (node (ref "U52") (pin "6") (pinfunction "2CX_6") (pintype "bidirectional"))
    )
    (net (code "417") (name "unconnected-(U52-2Q-Pad5)") (class "Default")
      (node (ref "U52") (pin "5") (pinfunction "2Q_5") (pintype "bidirectional"))
    )
    (net (code "418") (name "unconnected-(U52-2RXCX-Pad7)") (class "Default")
      (node (ref "U52") (pin "7") (pinfunction "2RXCX_7") (pintype "bidirectional"))
    )
    (net (code "419") (name "unconnected-(U52-~{1Q}-Pad4)") (class "Default")
      (node (ref "U52") (pin "4") (pinfunction "~{1Q}_4") (pintype "bidirectional"))
    )
    (net (code "420") (name "unconnected-(U52-~{2A}-Pad9)") (class "Default")
      (node (ref "U52") (pin "9") (pinfunction "~{2A}_9") (pintype "bidirectional"))
    )
    (net (code "421") (name "unconnected-(U52-~{2Q}-Pad12)") (class "Default")
      (node (ref "U52") (pin "12") (pinfunction "~{2Q}_12") (pintype "bidirectional"))
    )
    (net (code "422") (name "unconnected-(U52-~{2R}-Pad11)") (class "Default")
      (node (ref "U52") (pin "11") (pinfunction "~{2R}_11") (pintype "bidirectional"))
    )
  )
)
